# VCFA_v3.net
KiCad netlist of a schematic drawn in EAGLE
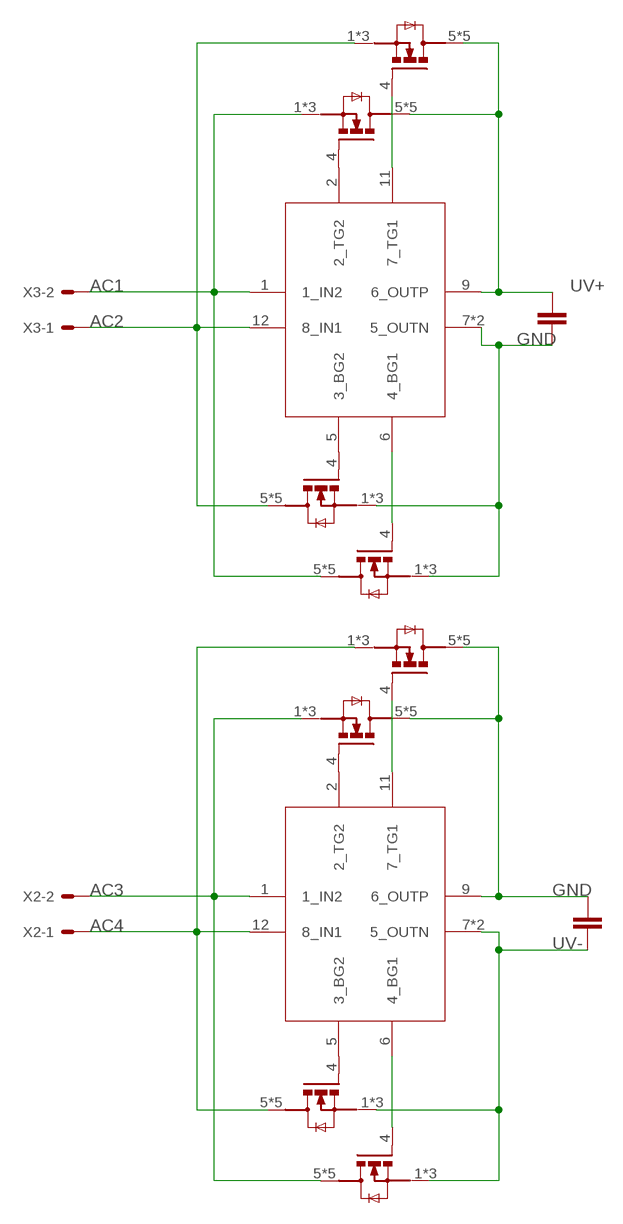
[diagram p0: schematic, sheet 1]
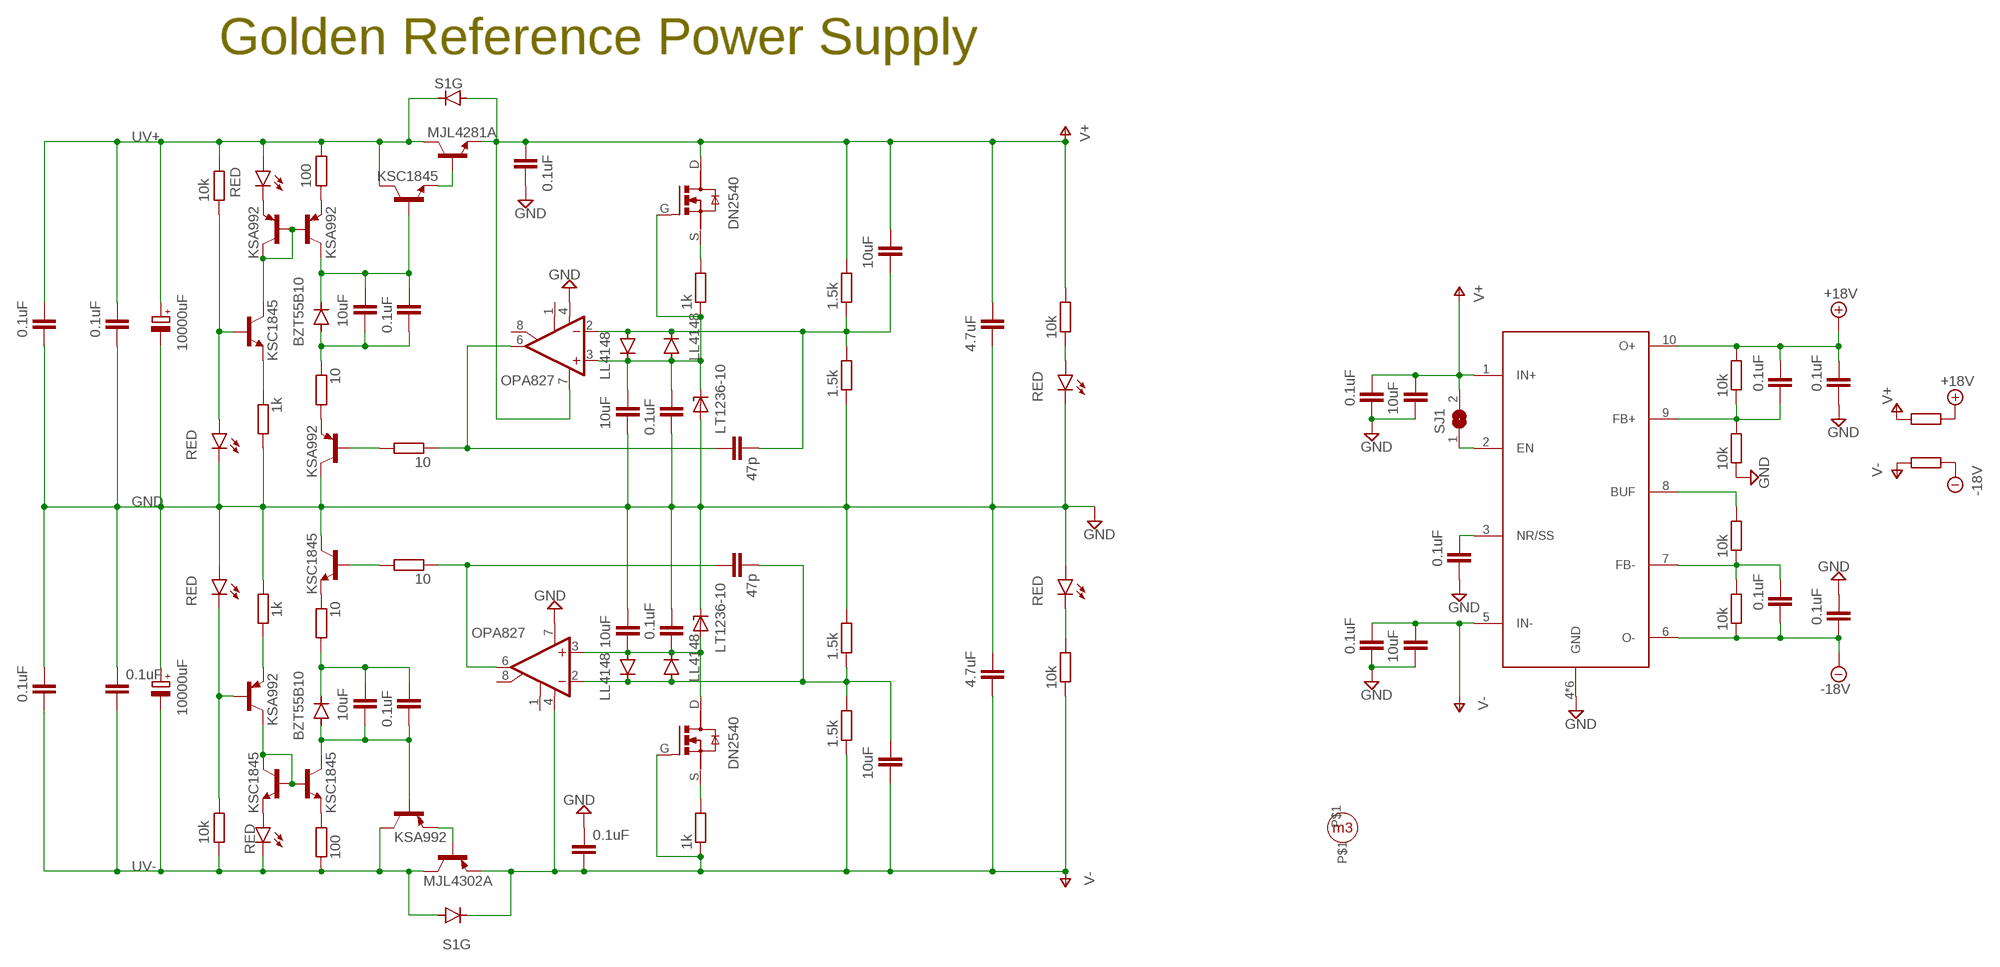
[diagram p1: schematic, sheet 2]
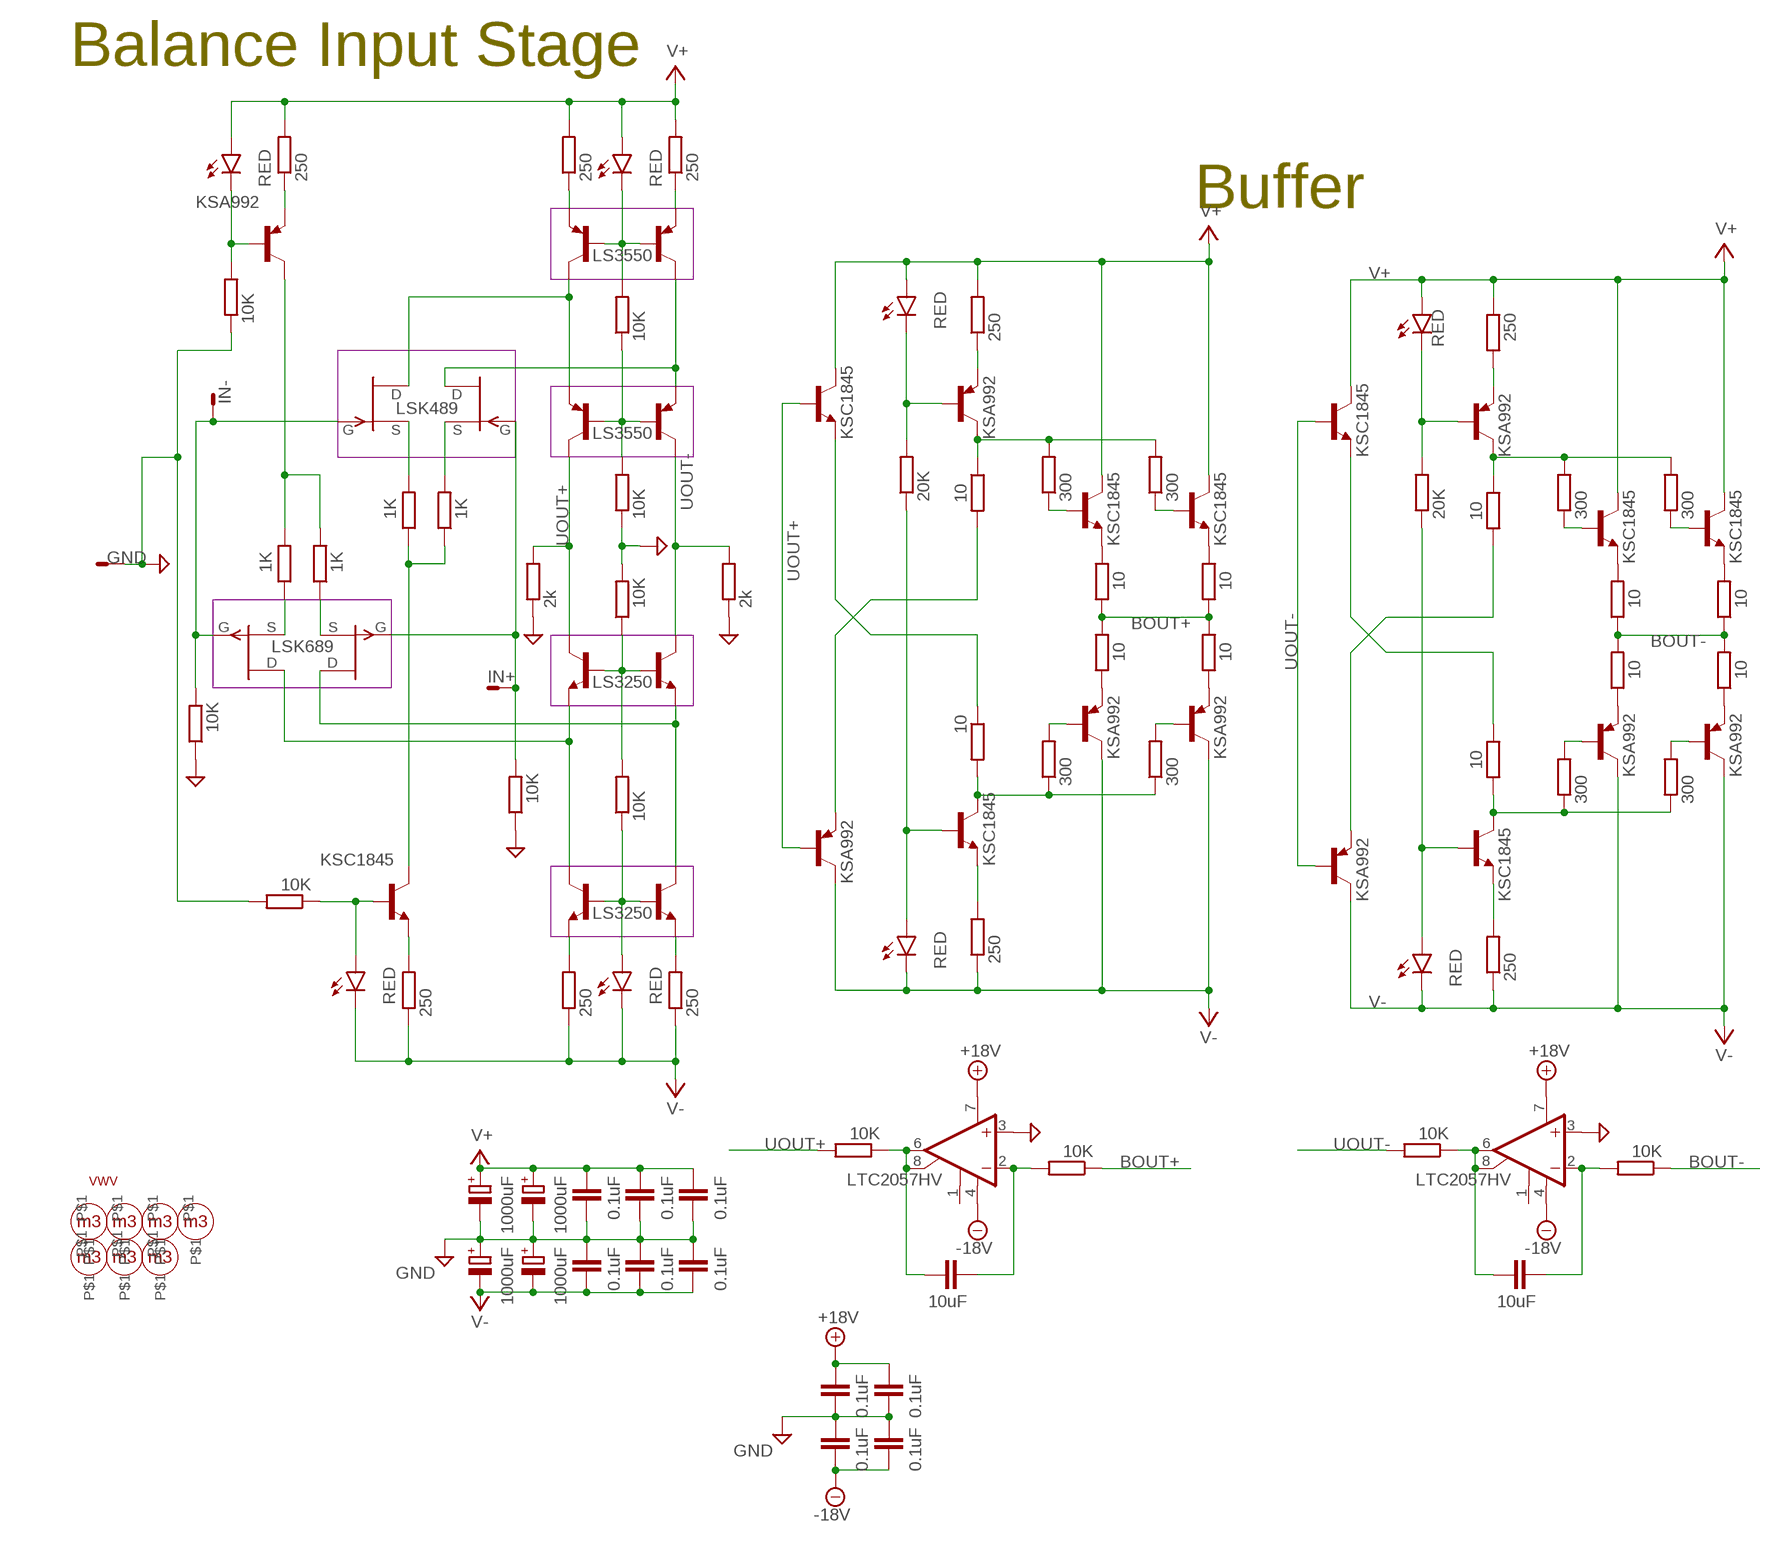
[diagram p2: schematic, sheet 3]
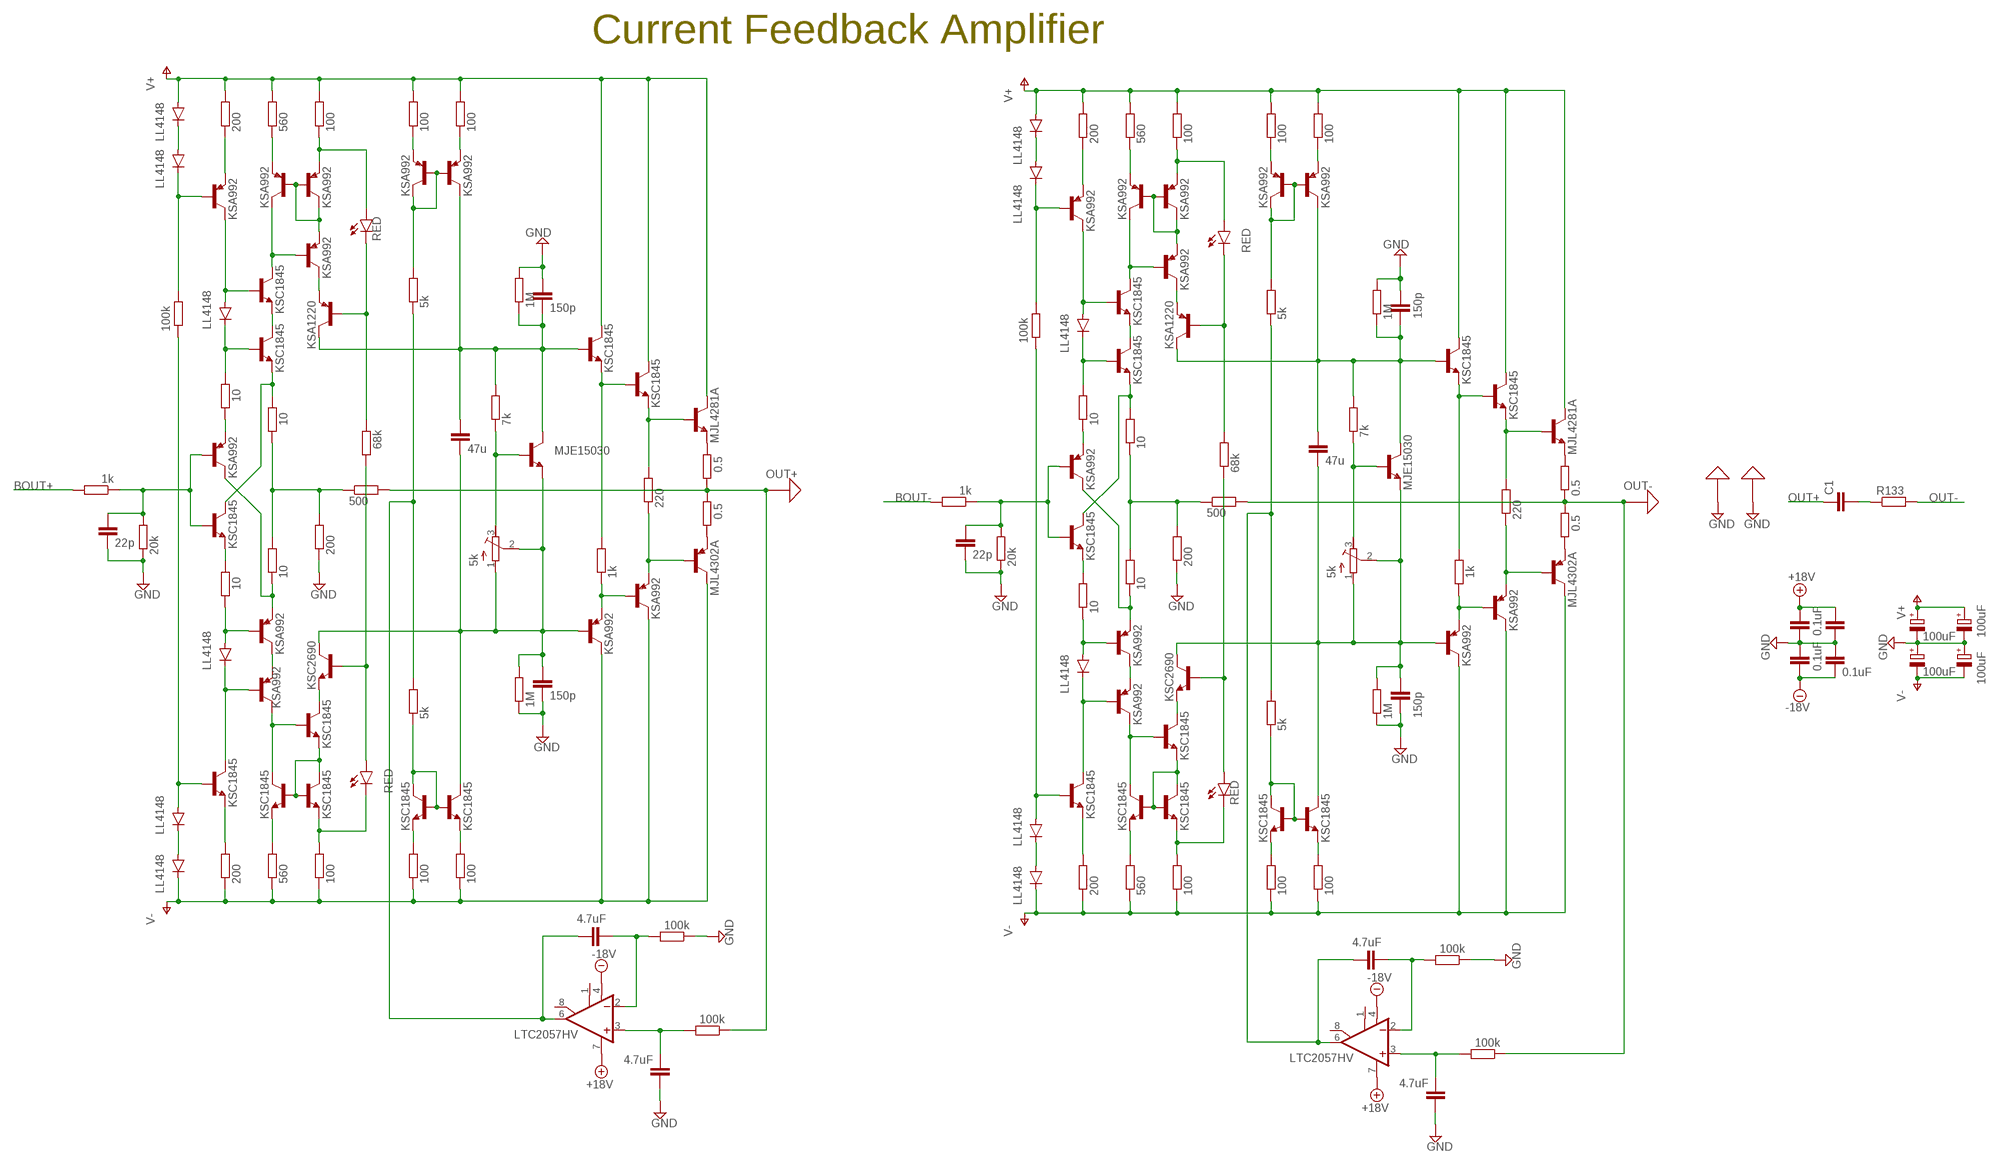
[diagram p3: schematic, sheet 4]

(export (version "E")
  (design (tool "Eeschema 10.0.6"))
  (components
    (comp (ref "C57")
      (value "47uF")
      (footprint "eagle-import:C1206")
      (libsource (lib "eagle-import") (part "C-EUC1206"))
    )
    (comp (ref "C59")
      (value "47uF")
      (footprint "eagle-import:C1206")
      (libsource (lib "eagle-import") (part "C-EUC1206"))
    )
    (comp (ref "Q97")
      (value "MOS_SMDTDSON-8")
      (footprint "eagle-import:PG-TDSON-8")
      (libsource (lib "eagle-import") (part "MOS_SMDTDSON-8"))
    )
    (comp (ref "Q98")
      (value "MOS_SMDTDSON-8")
      (footprint "eagle-import:PG-TDSON-8")
      (libsource (lib "eagle-import") (part "MOS_SMDTDSON-8"))
    )
    (comp (ref "Q99")
      (value "MOS_SMDTDSON-8")
      (footprint "eagle-import:PG-TDSON-8")
      (libsource (lib "eagle-import") (part "MOS_SMDTDSON-8"))
    )
    (comp (ref "Q100")
      (value "MOS_SMDTDSON-8")
      (footprint "eagle-import:PG-TDSON-8")
      (libsource (lib "eagle-import") (part "MOS_SMDTDSON-8"))
    )
    (comp (ref "Q105")
      (value "MOS_SMDTDSON-8")
      (footprint "eagle-import:PG-TDSON-8")
      (libsource (lib "eagle-import") (part "MOS_SMDTDSON-8"))
    )
    (comp (ref "Q106")
      (value "MOS_SMDTDSON-8")
      (footprint "eagle-import:PG-TDSON-8")
      (libsource (lib "eagle-import") (part "MOS_SMDTDSON-8"))
    )
    (comp (ref "Q107")
      (value "MOS_SMDTDSON-8")
      (footprint "eagle-import:PG-TDSON-8")
      (libsource (lib "eagle-import") (part "MOS_SMDTDSON-8"))
    )
    (comp (ref "Q108")
      (value "MOS_SMDTDSON-8")
      (footprint "eagle-import:PG-TDSON-8")
      (libsource (lib "eagle-import") (part "MOS_SMDTDSON-8"))
    )
    (comp (ref "U$2")
      (value "LT4320MSOP")
      (footprint "eagle-import:LT4320_MSOP")
      (libsource (lib "eagle-import") (part "LT4320MSOP"))
    )
    (comp (ref "U$4")
      (value "LT4320MSOP")
      (footprint "eagle-import:LT4320_MSOP")
      (libsource (lib "eagle-import") (part "LT4320MSOP"))
    )
    (comp (ref "X2")
      (value "KK-156-2")
      (footprint "eagle-import:KK-156-2")
      (fields (field (name "MF") "MOLEX"))
      (libsource (lib "eagle-import") (part "KK-156-2"))
    )
    (comp (ref "X3")
      (value "KK-156-2")
      (footprint "eagle-import:KK-156-2")
      (fields (field (name "MF") "MOLEX"))
      (libsource (lib "eagle-import") (part "KK-156-2"))
    )
    (comp (ref "C3")
      (value "0.1uF")
      (footprint "eagle-import:C0805")
      (libsource (lib "eagle-import") (part "C-EUC0805"))
    )
    (comp (ref "C4")
      (value "0.1uF")
      (footprint "eagle-import:C0805")
      (libsource (lib "eagle-import") (part "C-EUC0805"))
    )
    (comp (ref "C5")
      (value "1000uF")
      (footprint "eagle-import:E7,5-18")
      (libsource (lib "eagle-import") (part "CPOL-EUE7.5-18"))
    )
    (comp (ref "C6")
      (value "1000uF")
      (footprint "eagle-import:E7,5-18")
      (libsource (lib "eagle-import") (part "CPOL-EUE7.5-18"))
    )
    (comp (ref "C7")
      (value "1000uF")
      (footprint "eagle-import:E7,5-18")
      (libsource (lib "eagle-import") (part "CPOL-EUE7.5-18"))
    )
    (comp (ref "C8")
      (value "1000uF")
      (footprint "eagle-import:E7,5-18")
      (libsource (lib "eagle-import") (part "CPOL-EUE7.5-18"))
    )
    (comp (ref "C9")
      (value "0.1uF")
      (footprint "eagle-import:C050-045X075")
      (libsource (lib "eagle-import") (part "C-EU050-045X075"))
    )
    (comp (ref "C10")
      (value "0.1uF")
      (footprint "eagle-import:C050-045X075")
      (libsource (lib "eagle-import") (part "C-EU050-045X075"))
    )
    (comp (ref "C11")
      (value "0.1uF")
      (footprint "eagle-import:C050-045X075")
      (libsource (lib "eagle-import") (part "C-EU050-045X075"))
    )
    (comp (ref "C12")
      (value "0.1uF")
      (footprint "eagle-import:C050-045X075")
      (libsource (lib "eagle-import") (part "C-EU050-045X075"))
    )
    (comp (ref "C13")
      (value "10uF")
      (footprint "eagle-import:C1206")
      (libsource (lib "eagle-import") (part "C-EUC1206"))
    )
    (comp (ref "C14")
      (value "0.1uF")
      (footprint "eagle-import:C0805")
      (libsource (lib "eagle-import") (part "C-EUC0805"))
    )
    (comp (ref "C15")
      (value "0.1uF")
      (footprint "eagle-import:C0805")
      (libsource (lib "eagle-import") (part "C-EUC0805"))
    )
    (comp (ref "C16")
      (value "10uF")
      (footprint "eagle-import:C1206")
      (libsource (lib "eagle-import") (part "C-EUC1206"))
    )
    (comp (ref "C74")
      (value "0.1uF")
      (footprint "eagle-import:C050-045X075")
      (libsource (lib "eagle-import") (part "C-EU050-045X075"))
    )
    (comp (ref "C75")
      (value "0.1uF")
      (footprint "eagle-import:C050-045X075")
      (libsource (lib "eagle-import") (part "C-EU050-045X075"))
    )
    (comp (ref "H1")
      (value "HOLE")
      (footprint "eagle-import:M3_HOLE")
      (libsource (lib "eagle-import") (part "HOLE"))
    )
    (comp (ref "H2")
      (value "HOLE")
      (footprint "eagle-import:M3_HOLE")
      (libsource (lib "eagle-import") (part "HOLE"))
    )
    (comp (ref "H3")
      (value "HOLE")
      (footprint "eagle-import:M3_HOLE")
      (libsource (lib "eagle-import") (part "HOLE"))
    )
    (comp (ref "H4")
      (value "HOLE")
      (footprint "eagle-import:M3_HOLE")
      (libsource (lib "eagle-import") (part "HOLE"))
    )
    (comp (ref "H5")
      (value "HOLE")
      (footprint "eagle-import:M3_HOLE")
      (libsource (lib "eagle-import") (part "HOLE"))
    )
    (comp (ref "H6")
      (value "HOLE")
      (footprint "eagle-import:M3_HOLE")
      (libsource (lib "eagle-import") (part "HOLE"))
    )
    (comp (ref "H7")
      (value "HOLE")
      (footprint "eagle-import:M3_HOLE")
      (libsource (lib "eagle-import") (part "HOLE"))
    )
    (comp (ref "IC1")
      (value "LTC2057HV")
      (footprint "eagle-import:SOIC8")
      (libsource (lib "eagle-import") (part "LT10S807C"))
    )
    (comp (ref "IC2")
      (value "LTC2057HV")
      (footprint "eagle-import:SOIC8")
      (libsource (lib "eagle-import") (part "LT10S807C"))
    )
    (comp (ref "LED1")
      (value "RED")
      (footprint "eagle-import:LED_SML1206")
      (libsource (lib "eagle-import") (part "LEDVWV1206"))
    )
    (comp (ref "LED2")
      (value "RED")
      (footprint "eagle-import:LED_SML1206")
      (fields (field (name "SPICEPREFIX") "D"))
      (libsource (lib "eagle-import") (part "LEDVWV1206"))
    )
    (comp (ref "LED3")
      (value "RED")
      (footprint "eagle-import:LED_SML1206")
      (libsource (lib "eagle-import") (part "LEDVWV1206"))
    )
    (comp (ref "LED4")
      (value "RED")
      (footprint "eagle-import:LED_SML1206")
      (libsource (lib "eagle-import") (part "LEDVWV1206"))
    )
    (comp (ref "LED5")
      (value "RED")
      (footprint "eagle-import:LED_SML1206")
      (libsource (lib "eagle-import") (part "LEDVWV1206"))
    )
    (comp (ref "LED6")
      (value "RED")
      (footprint "eagle-import:LED_SML1206")
      (libsource (lib "eagle-import") (part "LEDVWV1206"))
    )
    (comp (ref "LED7")
      (value "RED")
      (footprint "eagle-import:LED_SML1206")
      (libsource (lib "eagle-import") (part "LEDVWV1206"))
    )
    (comp (ref "LED8")
      (value "RED")
      (footprint "eagle-import:LED_SML1206")
      (libsource (lib "eagle-import") (part "LEDVWV1206"))
    )
    (comp (ref "Q1")
      (value "LSK689")
      (footprint "eagle-import:SOT-23-6")
      (libsource (lib "eagle-import") (part "LSK689"))
    )
    (comp (ref "Q2")
      (value "KSA992")
      (footprint "eagle-import:TRANSISTOR_TO92-ECB_P")
      (libsource (lib "eagle-import") (part "BJT_PNPKSA992"))
    )
    (comp (ref "Q3")
      (value "KSC1845")
      (footprint "eagle-import:TRANSISTOR_TO92-ECB_N")
      (libsource (lib "eagle-import") (part "BJT_NPNKSC1845"))
    )
    (comp (ref "Q4")
      (value "LSK489")
      (footprint "eagle-import:SOT-23-6")
      (libsource (lib "eagle-import") (part "LSK489SOP-6"))
    )
    (comp (ref "Q5")
      (value "LS3550")
      (footprint "eagle-import:SOT-23-6")
      (libsource (lib "eagle-import") (part "LS3550"))
    )
    (comp (ref "Q6")
      (value "LS3250")
      (footprint "eagle-import:SOT-23-6")
      (libsource (lib "eagle-import") (part "LS3250"))
    )
    (comp (ref "Q7")
      (value "LS3250")
      (footprint "eagle-import:SOT-23-6")
      (libsource (lib "eagle-import") (part "LS3250"))
    )
    (comp (ref "Q8")
      (value "LS3550")
      (footprint "eagle-import:SOT-23-6")
      (libsource (lib "eagle-import") (part "LS3550"))
    )
    (comp (ref "Q9")
      (value "KSC1845")
      (footprint "eagle-import:TRANSISTOR_TO92-ECB_N")
      (libsource (lib "eagle-import") (part "BJT_NPNKSC1845"))
    )
    (comp (ref "Q10")
      (value "KSA992")
      (footprint "eagle-import:TRANSISTOR_TO92-ECB_P")
      (libsource (lib "eagle-import") (part "BJT_PNPKSA992"))
    )
    (comp (ref "Q11")
      (value "KSA992")
      (footprint "eagle-import:TRANSISTOR_TO92-ECB_P")
      (libsource (lib "eagle-import") (part "BJT_PNPKSA992"))
    )
    (comp (ref "Q12")
      (value "KSC1845")
      (footprint "eagle-import:TRANSISTOR_TO92-ECB_N")
      (libsource (lib "eagle-import") (part "BJT_NPNKSC1845"))
    )
    (comp (ref "Q13")
      (value "KSC1845")
      (footprint "eagle-import:TRANSISTOR_TO92-ECB_N")
      (libsource (lib "eagle-import") (part "BJT_NPNKSC1845"))
    )
    (comp (ref "Q14")
      (value "KSA992")
      (footprint "eagle-import:TRANSISTOR_TO92-ECB_P")
      (libsource (lib "eagle-import") (part "BJT_PNPKSA992"))
    )
    (comp (ref "Q15")
      (value "KSC1845")
      (footprint "eagle-import:TRANSISTOR_TO92-ECB_N")
      (libsource (lib "eagle-import") (part "BJT_NPNKSC1845"))
    )
    (comp (ref "Q16")
      (value "KSA992")
      (footprint "eagle-import:TRANSISTOR_TO92-ECB_P")
      (libsource (lib "eagle-import") (part "BJT_PNPKSA992"))
    )
    (comp (ref "Q17")
      (value "KSC1845")
      (footprint "eagle-import:TRANSISTOR_TO92-ECB_N")
      (libsource (lib "eagle-import") (part "BJT_NPNKSC1845"))
    )
    (comp (ref "Q18")
      (value "KSA992")
      (footprint "eagle-import:TRANSISTOR_TO92-ECB_P")
      (libsource (lib "eagle-import") (part "BJT_PNPKSA992"))
    )
    (comp (ref "Q19")
      (value "KSA992")
      (footprint "eagle-import:TRANSISTOR_TO92-ECB_P")
      (libsource (lib "eagle-import") (part "BJT_PNPKSA992"))
    )
    (comp (ref "Q20")
      (value "KSC1845")
      (footprint "eagle-import:TRANSISTOR_TO92-ECB_N")
      (libsource (lib "eagle-import") (part "BJT_NPNKSC1845"))
    )
    (comp (ref "Q21")
      (value "KSC1845")
      (footprint "eagle-import:TRANSISTOR_TO92-ECB_N")
      (libsource (lib "eagle-import") (part "BJT_NPNKSC1845"))
    )
    (comp (ref "Q22")
      (value "KSA992")
      (footprint "eagle-import:TRANSISTOR_TO92-ECB_P")
      (libsource (lib "eagle-import") (part "BJT_PNPKSA992"))
    )
    (comp (ref "Q23")
      (value "KSC1845")
      (footprint "eagle-import:TRANSISTOR_TO92-ECB_N")
      (libsource (lib "eagle-import") (part "BJT_NPNKSC1845"))
    )
    (comp (ref "Q24")
      (value "KSA992")
      (footprint "eagle-import:TRANSISTOR_TO92-ECB_P")
      (libsource (lib "eagle-import") (part "BJT_PNPKSA992"))
    )
    (comp (ref "R3")
      (value "10K")
      (footprint "eagle-import:MINI_MELF-0204W")
      (libsource (lib "eagle-import") (part "R-EU_MELF0204W"))
    )
    (comp (ref "R4")
      (value "10K")
      (footprint "eagle-import:MINI_MELF-0204W")
      (libsource (lib "eagle-import") (part "R-EU_MELF0204W"))
    )
    (comp (ref "R5")
      (value "250")
      (footprint "eagle-import:MINI_MELF-0204W")
      (libsource (lib "eagle-import") (part "R-EU_MELF0204W"))
    )
    (comp (ref "R6")
      (value "1K")
      (footprint "eagle-import:MINI_MELF-0204W")
      (libsource (lib "eagle-import") (part "R-EU_MELF0204W"))
    )
    (comp (ref "R7")
      (value "250")
      (footprint "eagle-import:MINI_MELF-0204W")
      (fields (field (name "SPICEPREFIX") "R"))
      (libsource (lib "eagle-import") (part "R-EU_MELF0204W"))
    )
    (comp (ref "R8")
      (value "1K")
      (footprint "eagle-import:MINI_MELF-0204W")
      (libsource (lib "eagle-import") (part "R-EU_MELF0204W"))
    )
    (comp (ref "R9")
      (value "1K")
      (footprint "eagle-import:MINI_MELF-0204W")
      (libsource (lib "eagle-import") (part "R-EU_MELF0204W"))
    )
    (comp (ref "R10")
      (value "1K")
      (footprint "eagle-import:MINI_MELF-0204W")
      (libsource (lib "eagle-import") (part "R-EU_MELF0204W"))
    )
    (comp (ref "R11")
      (value "2k")
      (footprint "eagle-import:MINI_MELF-0204W")
      (libsource (lib "eagle-import") (part "R-EU_MELF0204W"))
    )
    (comp (ref "R12")
      (value "250")
      (footprint "eagle-import:MINI_MELF-0204W")
      (libsource (lib "eagle-import") (part "R-EU_MELF0204W"))
    )
    (comp (ref "R13")
      (value "250")
      (footprint "eagle-import:MINI_MELF-0204W")
      (libsource (lib "eagle-import") (part "R-EU_MELF0204W"))
    )
    (comp (ref "R14")
      (value "10K")
      (footprint "eagle-import:MINI_MELF-0204W")
      (libsource (lib "eagle-import") (part "R-EU_MELF0204W"))
    )
    (comp (ref "R15")
      (value "10K")
      (footprint "eagle-import:MINI_MELF-0204W")
      (libsource (lib "eagle-import") (part "R-EU_MELF0204W"))
    )
    (comp (ref "R16")
      (value "10K")
      (footprint "eagle-import:MINI_MELF-0204W")
      (libsource (lib "eagle-import") (part "R-EU_MELF0204W"))
    )
    (comp (ref "R17")
      (value "10K")
      (footprint "eagle-import:MINI_MELF-0204W")
      (libsource (lib "eagle-import") (part "R-EU_MELF0204W"))
    )
    (comp (ref "R18")
      (value "250")
      (footprint "eagle-import:MINI_MELF-0204W")
      (libsource (lib "eagle-import") (part "R-EU_MELF0204W"))
    )
    (comp (ref "R19")
      (value "250")
      (footprint "eagle-import:MINI_MELF-0204W")
      (libsource (lib "eagle-import") (part "R-EU_MELF0204W"))
    )
    (comp (ref "R20")
      (value "2k")
      (footprint "eagle-import:MINI_MELF-0204W")
      (libsource (lib "eagle-import") (part "R-EU_MELF0204W"))
    )
    (comp (ref "R21")
      (value "10K")
      (footprint "eagle-import:MINI_MELF-0204W")
      (libsource (lib "eagle-import") (part "R-EU_MELF0204W"))
    )
    (comp (ref "R22")
      (value "20K")
      (footprint "eagle-import:MINI_MELF-0204W")
      (libsource (lib "eagle-import") (part "R-EU_MELF0204W"))
    )
    (comp (ref "R23")
      (value "250")
      (footprint "eagle-import:MINI_MELF-0204W")
      (libsource (lib "eagle-import") (part "R-EU_MELF0204W"))
    )
    (comp (ref "R24")
      (value "10")
      (footprint "eagle-import:MINI_MELF-0204W")
      (libsource (lib "eagle-import") (part "R-EU_MELF0204W"))
    )
    (comp (ref "R25")
      (value "10")
      (footprint "eagle-import:MINI_MELF-0204W")
      (libsource (lib "eagle-import") (part "R-EU_MELF0204W"))
    )
    (comp (ref "R26")
      (value "250")
      (footprint "eagle-import:MINI_MELF-0204W")
      (libsource (lib "eagle-import") (part "R-EU_MELF0204W"))
    )
    (comp (ref "R27")
      (value "300")
      (footprint "eagle-import:MINI_MELF-0204W")
      (libsource (lib "eagle-import") (part "R-EU_MELF0204W"))
    )
    (comp (ref "R28")
      (value "300")
      (footprint "eagle-import:MINI_MELF-0204W")
      (libsource (lib "eagle-import") (part "R-EU_MELF0204W"))
    )
    (comp (ref "R29")
      (value "10K")
      (footprint "eagle-import:MINI_MELF-0204W")
      (libsource (lib "eagle-import") (part "R-EU_MELF0204W"))
    )
    (comp (ref "R30")
      (value "10")
      (footprint "eagle-import:MINI_MELF-0204W")
      (libsource (lib "eagle-import") (part "R-EU_MELF0204W"))
    )
    (comp (ref "R31")
      (value "10")
      (footprint "eagle-import:MINI_MELF-0204W")
      (libsource (lib "eagle-import") (part "R-EU_MELF0204W"))
    )
    (comp (ref "R32")
      (value "300")
      (footprint "eagle-import:MINI_MELF-0204W")
      (libsource (lib "eagle-import") (part "R-EU_MELF0204W"))
    )
    (comp (ref "R33")
      (value "300")
      (footprint "eagle-import:MINI_MELF-0204W")
      (libsource (lib "eagle-import") (part "R-EU_MELF0204W"))
    )
    (comp (ref "R34")
      (value "10")
      (footprint "eagle-import:MINI_MELF-0204W")
      (libsource (lib "eagle-import") (part "R-EU_MELF0204W"))
    )
    (comp (ref "R35")
      (value "10")
      (footprint "eagle-import:MINI_MELF-0204W")
      (libsource (lib "eagle-import") (part "R-EU_MELF0204W"))
    )
    (comp (ref "R36")
      (value "10K")
      (footprint "eagle-import:MINI_MELF-0204W")
      (libsource (lib "eagle-import") (part "R-EU_MELF0204W"))
    )
    (comp (ref "R37")
      (value "20K")
      (footprint "eagle-import:MINI_MELF-0204W")
      (libsource (lib "eagle-import") (part "R-EU_MELF0204W"))
    )
    (comp (ref "R38")
      (value "250")
      (footprint "eagle-import:MINI_MELF-0204W")
      (libsource (lib "eagle-import") (part "R-EU_MELF0204W"))
    )
    (comp (ref "R39")
      (value "10")
      (footprint "eagle-import:MINI_MELF-0204W")
      (libsource (lib "eagle-import") (part "R-EU_MELF0204W"))
    )
    (comp (ref "R40")
      (value "10")
      (footprint "eagle-import:MINI_MELF-0204W")
      (libsource (lib "eagle-import") (part "R-EU_MELF0204W"))
    )
    (comp (ref "R41")
      (value "250")
      (footprint "eagle-import:MINI_MELF-0204W")
      (libsource (lib "eagle-import") (part "R-EU_MELF0204W"))
    )
    (comp (ref "R42")
      (value "300")
      (footprint "eagle-import:MINI_MELF-0204W")
      (libsource (lib "eagle-import") (part "R-EU_MELF0204W"))
    )
    (comp (ref "R43")
      (value "300")
      (footprint "eagle-import:MINI_MELF-0204W")
      (libsource (lib "eagle-import") (part "R-EU_MELF0204W"))
    )
    (comp (ref "R44")
      (value "10K")
      (footprint "eagle-import:MINI_MELF-0204W")
      (libsource (lib "eagle-import") (part "R-EU_MELF0204W"))
    )
    (comp (ref "R45")
      (value "10")
      (footprint "eagle-import:MINI_MELF-0204W")
      (libsource (lib "eagle-import") (part "R-EU_MELF0204W"))
    )
    (comp (ref "R46")
      (value "10")
      (footprint "eagle-import:MINI_MELF-0204W")
      (libsource (lib "eagle-import") (part "R-EU_MELF0204W"))
    )
    (comp (ref "R47")
      (value "300")
      (footprint "eagle-import:MINI_MELF-0204W")
      (libsource (lib "eagle-import") (part "R-EU_MELF0204W"))
    )
    (comp (ref "R48")
      (value "300")
      (footprint "eagle-import:MINI_MELF-0204W")
      (libsource (lib "eagle-import") (part "R-EU_MELF0204W"))
    )
    (comp (ref "R49")
      (value "10")
      (footprint "eagle-import:MINI_MELF-0204W")
      (libsource (lib "eagle-import") (part "R-EU_MELF0204W"))
    )
    (comp (ref "R50")
      (value "10")
      (footprint "eagle-import:MINI_MELF-0204W")
      (libsource (lib "eagle-import") (part "R-EU_MELF0204W"))
    )
    (comp (ref "R134")
      (value "10K")
      (footprint "eagle-import:MINI_MELF-0204W")
      (libsource (lib "eagle-import") (part "R-EU_MELF0204W"))
    )
    (comp (ref "R135")
      (value "10K")
      (footprint "eagle-import:MINI_MELF-0204W")
      (libsource (lib "eagle-import") (part "R-EU_MELF0204W"))
    )
    (comp (ref "S1")
      (value "VWV")
      (footprint "eagle-import:VWV")
      (libsource (lib "eagle-import") (part "VWV"))
    )
    (comp (ref "X1")
      (value "KK-156-3")
      (footprint "eagle-import:KK-156-3")
      (fields (field (name "MF") "MOLEX"))
      (libsource (lib "eagle-import") (part "KK-156-3"))
    )
    (comp (ref "C1")
      (value "C-EUECWU-V")
      (footprint "eagle-import:ECHU-Y")
      (libsource (lib "eagle-import") (part "C-EUECWU-V"))
    )
    (comp (ref "C17")
      (value "22p")
      (footprint "eagle-import:C0805")
      (fields (field (name "SPICEPREFIX") "C"))
      (libsource (lib "eagle-import") (part "C-EUC0805"))
    )
    (comp (ref "C18")
      (value "47u")
      (footprint "eagle-import:C1210")
      (fields (field (name "SPICEPREFIX") "C"))
      (libsource (lib "eagle-import") (part "C-EUC1210"))
    )
    (comp (ref "C19")
      (value "150p")
      (footprint "eagle-import:C0805")
      (fields (field (name "SPICEPREFIX") "C"))
      (libsource (lib "eagle-import") (part "C-EUC0805"))
    )
    (comp (ref "C20")
      (value "150p")
      (footprint "eagle-import:C0805")
      (fields (field (name "SPICEPREFIX") "C"))
      (libsource (lib "eagle-import") (part "C-EUC0805"))
    )
    (comp (ref "C21")
      (value "4.7uF")
      (footprint "eagle-import:C1210")
      (fields (field (name "SPICEPREFIX") "C"))
      (libsource (lib "eagle-import") (part "C-EUC1210"))
    )
    (comp (ref "C22")
      (value "4.7uF")
      (footprint "eagle-import:C1210")
      (fields (field (name "SPICEPREFIX") "C"))
      (libsource (lib "eagle-import") (part "C-EUC1210"))
    )
    (comp (ref "C23")
      (value "0.1uF")
      (footprint "eagle-import:C0603K")
      (libsource (lib "eagle-import") (part "C-EUC0603K"))
    )
    (comp (ref "C24")
      (value "0.1uF")
      (footprint "eagle-import:C0603K")
      (libsource (lib "eagle-import") (part "C-EUC0603K"))
    )
    (comp (ref "C25")
      (value "100uF")
      (footprint "eagle-import:E5-8,5")
      (libsource (lib "eagle-import") (part "CPOL-EUE5-8.5"))
    )
    (comp (ref "C26")
      (value "100uF")
      (footprint "eagle-import:E5-8,5")
      (libsource (lib "eagle-import") (part "CPOL-EUE5-8.5"))
    )
    (comp (ref "C27")
      (value "22p")
      (footprint "eagle-import:C0805")
      (fields (field (name "SPICEPREFIX") "C"))
      (libsource (lib "eagle-import") (part "C-EUC0805"))
    )
    (comp (ref "C28")
      (value "47u")
      (footprint "eagle-import:C1210")
      (fields (field (name "SPICEPREFIX") "C"))
      (libsource (lib "eagle-import") (part "C-EUC1210"))
    )
    (comp (ref "C29")
      (value "150p")
      (footprint "eagle-import:C0805")
      (fields (field (name "SPICEPREFIX") "C"))
      (libsource (lib "eagle-import") (part "C-EUC0805"))
    )
    (comp (ref "C30")
      (value "150p")
      (footprint "eagle-import:C0805")
      (fields (field (name "SPICEPREFIX") "C"))
      (libsource (lib "eagle-import") (part "C-EUC0805"))
    )
    (comp (ref "C31")
      (value "4.7uF")
      (footprint "eagle-import:C1210")
      (fields (field (name "SPICEPREFIX") "C"))
      (libsource (lib "eagle-import") (part "C-EUC1210"))
    )
    (comp (ref "C32")
      (value "4.7uF")
      (footprint "eagle-import:C1210")
      (fields (field (name "SPICEPREFIX") "C"))
      (libsource (lib "eagle-import") (part "C-EUC1210"))
    )
    (comp (ref "C33")
      (value "0.1uF")
      (footprint "eagle-import:C0603K")
      (libsource (lib "eagle-import") (part "C-EUC0603K"))
    )
    (comp (ref "C34")
      (value "0.1uF")
      (footprint "eagle-import:C0603K")
      (libsource (lib "eagle-import") (part "C-EUC0603K"))
    )
    (comp (ref "C35")
      (value "100uF")
      (footprint "eagle-import:E5-8,5")
      (libsource (lib "eagle-import") (part "CPOL-EUE5-8.5"))
    )
    (comp (ref "C36")
      (value "100uF")
      (footprint "eagle-import:E5-8,5")
      (libsource (lib "eagle-import") (part "CPOL-EUE5-8.5"))
    )
    (comp (ref "D1")
      (value "LL4148")
      (footprint "eagle-import:SOD80C")
      (fields (field (name "SPICEPREFIX") "D"))
      (libsource (lib "eagle-import") (part "DIODE-SOD80C"))
    )
    (comp (ref "D2")
      (value "LL4148")
      (footprint "eagle-import:SOD80C")
      (fields (field (name "SPICEPREFIX") "D"))
      (libsource (lib "eagle-import") (part "DIODE-SOD80C"))
    )
    (comp (ref "D3")
      (value "LL4148")
      (footprint "eagle-import:SOD80C")
      (fields (field (name "SPICEPREFIX") "D"))
      (libsource (lib "eagle-import") (part "DIODE-SOD80C"))
    )
    (comp (ref "D4")
      (value "LL4148")
      (footprint "eagle-import:SOD80C")
      (fields (field (name "SPICEPREFIX") "D"))
      (libsource (lib "eagle-import") (part "DIODE-SOD80C"))
    )
    (comp (ref "D5")
      (value "LL4148")
      (footprint "eagle-import:SOD80C")
      (fields (field (name "SPICEPREFIX") "D"))
      (libsource (lib "eagle-import") (part "DIODE-SOD80C"))
    )
    (comp (ref "D6")
      (value "LL4148")
      (footprint "eagle-import:SOD80C")
      (fields (field (name "SPICEPREFIX") "D"))
      (libsource (lib "eagle-import") (part "DIODE-SOD80C"))
    )
    (comp (ref "D7")
      (value "LL4148")
      (footprint "eagle-import:SOD80C")
      (fields (field (name "SPICEPREFIX") "D"))
      (libsource (lib "eagle-import") (part "DIODE-SOD80C"))
    )
    (comp (ref "D8")
      (value "LL4148")
      (footprint "eagle-import:SOD80C")
      (fields (field (name "SPICEPREFIX") "D"))
      (libsource (lib "eagle-import") (part "DIODE-SOD80C"))
    )
    (comp (ref "D9")
      (value "LL4148")
      (footprint "eagle-import:SOD80C")
      (fields (field (name "SPICEPREFIX") "D"))
      (libsource (lib "eagle-import") (part "DIODE-SOD80C"))
    )
    (comp (ref "D10")
      (value "LL4148")
      (footprint "eagle-import:SOD80C")
      (fields (field (name "SPICEPREFIX") "D"))
      (libsource (lib "eagle-import") (part "DIODE-SOD80C"))
    )
    (comp (ref "D11")
      (value "LL4148")
      (footprint "eagle-import:SOD80C")
      (fields (field (name "SPICEPREFIX") "D"))
      (libsource (lib "eagle-import") (part "DIODE-SOD80C"))
    )
    (comp (ref "D12")
      (value "LL4148")
      (footprint "eagle-import:SOD80C")
      (fields (field (name "SPICEPREFIX") "D"))
      (libsource (lib "eagle-import") (part "DIODE-SOD80C"))
    )
    (comp (ref "IC3")
      (value "LTC2057HV")
      (footprint "eagle-import:SOIC8")
      (libsource (lib "eagle-import") (part "LT10S837I"))
    )
    (comp (ref "IC4")
      (value "LTC2057HV")
      (footprint "eagle-import:SOIC8")
      (libsource (lib "eagle-import") (part "LT10S837I"))
    )
    (comp (ref "LED9")
      (value "RED")
      (footprint "eagle-import:LED_SML1206")
      (fields (field (name "SPICEPREFIX") "D"))
      (libsource (lib "eagle-import") (part "LEDVWV1206"))
    )
    (comp (ref "LED10")
      (value "RED")
      (footprint "eagle-import:LED_SML1206")
      (fields (field (name "SPICEPREFIX") "D"))
      (libsource (lib "eagle-import") (part "LEDVWV1206"))
    )
    (comp (ref "LED11")
      (value "RED")
      (footprint "eagle-import:LED_SML1206")
      (fields (field (name "SPICEPREFIX") "D"))
      (libsource (lib "eagle-import") (part "LEDVWV1206"))
    )
    (comp (ref "LED12")
      (value "RED")
      (footprint "eagle-import:LED_SML1206")
      (fields (field (name "SPICEPREFIX") "D"))
      (libsource (lib "eagle-import") (part "LEDVWV1206"))
    )
    (comp (ref "PAD1")
      (value "PAD")
      (footprint "eagle-import:PAD-16")
      (libsource (lib "eagle-import") (part "PAD"))
    )
    (comp (ref "PAD2")
      (value "PAD")
      (footprint "eagle-import:PAD-16")
      (libsource (lib "eagle-import") (part "PAD"))
    )
    (comp (ref "PAD3")
      (value "PAD")
      (footprint "eagle-import:PAD-16")
      (libsource (lib "eagle-import") (part "PAD"))
    )
    (comp (ref "PAD4")
      (value "PAD")
      (footprint "eagle-import:PAD-16")
      (libsource (lib "eagle-import") (part "PAD"))
    )
    (comp (ref "Q25")
      (value "KSA992")
      (footprint "eagle-import:TRANSISTOR_TO92-ECB_P")
      (fields (field (name "SPICEPREFIX") "Q"))
      (libsource (lib "eagle-import") (part "BJT_PNPKSA992"))
    )
    (comp (ref "Q26")
      (value "KSA992")
      (footprint "eagle-import:TRANSISTOR_TO92-ECB_P")
      (fields (field (name "SPICEPREFIX") "Q"))
      (libsource (lib "eagle-import") (part "BJT_PNPKSA992"))
    )
    (comp (ref "Q27")
      (value "KSC1845")
      (footprint "eagle-import:TRANSISTOR_TO92-ECB_N")
      (fields (field (name "SPICEPREFIX") "Q"))
      (libsource (lib "eagle-import") (part "BJT_NPNKSC1845"))
    )
    (comp (ref "Q28")
      (value "KSC1845")
      (footprint "eagle-import:TRANSISTOR_TO92-ECB_N")
      (fields (field (name "SPICEPREFIX") "Q"))
      (libsource (lib "eagle-import") (part "BJT_NPNKSC1845"))
    )
    (comp (ref "Q29")
      (value "KSC1845")
      (footprint "eagle-import:TRANSISTOR_TO92-ECB_N")
      (fields (field (name "SPICEPREFIX") "Q"))
      (libsource (lib "eagle-import") (part "BJT_NPNKSC1845"))
    )
    (comp (ref "Q30")
      (value "KSC1845")
      (footprint "eagle-import:TRANSISTOR_TO92-ECB_N")
      (fields (field (name "SPICEPREFIX") "Q"))
      (libsource (lib "eagle-import") (part "BJT_NPNKSC1845"))
    )
    (comp (ref "Q31")
      (value "KSA992")
      (footprint "eagle-import:TRANSISTOR_TO92-ECB_P")
      (fields (field (name "SPICEPREFIX") "Q"))
      (libsource (lib "eagle-import") (part "BJT_PNPKSA992"))
    )
    (comp (ref "Q32")
      (value "KSA992")
      (footprint "eagle-import:TRANSISTOR_TO92-ECB_P")
      (fields (field (name "SPICEPREFIX") "Q"))
      (libsource (lib "eagle-import") (part "BJT_PNPKSA992"))
    )
    (comp (ref "Q33")
      (value "KSA992")
      (footprint "eagle-import:TRANSISTOR_TO92-ECB_P")
      (fields (field (name "SPICEPREFIX") "Q"))
      (libsource (lib "eagle-import") (part "BJT_PNPKSA992"))
    )
    (comp (ref "Q34")
      (value "KSC1845")
      (footprint "eagle-import:TRANSISTOR_TO92-ECB_N")
      (fields (field (name "SPICEPREFIX") "Q"))
      (libsource (lib "eagle-import") (part "BJT_NPNKSC1845"))
    )
    (comp (ref "Q35")
      (value "KSA992")
      (footprint "eagle-import:TRANSISTOR_TO92-ECB_P")
      (fields (field (name "SPICEPREFIX") "Q"))
      (libsource (lib "eagle-import") (part "BJT_PNPKSA992"))
    )
    (comp (ref "Q36")
      (value "KSA992")
      (footprint "eagle-import:TRANSISTOR_TO92-ECB_P")
      (fields (field (name "SPICEPREFIX") "Q"))
      (libsource (lib "eagle-import") (part "BJT_PNPKSA992"))
    )
    (comp (ref "Q37")
      (value "KSC1845")
      (footprint "eagle-import:TRANSISTOR_TO92-ECB_N")
      (fields (field (name "SPICEPREFIX") "Q"))
      (libsource (lib "eagle-import") (part "BJT_NPNKSC1845"))
    )
    (comp (ref "Q38")
      (value "KSC1845")
      (footprint "eagle-import:TRANSISTOR_TO92-ECB_N")
      (fields (field (name "SPICEPREFIX") "Q"))
      (libsource (lib "eagle-import") (part "BJT_NPNKSC1845"))
    )
    (comp (ref "Q39")
      (value "KSA1220")
      (footprint "eagle-import:TRANSISTOR_TO126_P")
      (fields (field (name "SPICEPREFIX") "Q"))
      (libsource (lib "eagle-import") (part "BJT_PNPKSA1220"))
    )
    (comp (ref "Q40")
      (value "KSC2690")
      (footprint "eagle-import:TRANSISTOR_TO126_N")
      (fields (field (name "SPICEPREFIX") "Q"))
      (libsource (lib "eagle-import") (part "BJT_NPNKSC2690"))
    )
    (comp (ref "Q41")
      (value "KSA992")
      (footprint "eagle-import:TRANSISTOR_TO92-ECB_P")
      (fields (field (name "SPICEPREFIX") "Q"))
      (libsource (lib "eagle-import") (part "BJT_PNPKSA992"))
    )
    (comp (ref "Q42")
      (value "KSC1845")
      (footprint "eagle-import:TRANSISTOR_TO92-ECB_N")
      (fields (field (name "SPICEPREFIX") "Q"))
      (libsource (lib "eagle-import") (part "BJT_NPNKSC1845"))
    )
    (comp (ref "Q43")
      (value "KSA992")
      (footprint "eagle-import:TRANSISTOR_TO92-ECB_P")
      (fields (field (name "SPICEPREFIX") "Q"))
      (libsource (lib "eagle-import") (part "BJT_PNPKSA992"))
    )
    (comp (ref "Q44")
      (value "KSC1845")
      (footprint "eagle-import:TRANSISTOR_TO92-ECB_N")
      (fields (field (name "SPICEPREFIX") "Q"))
      (libsource (lib "eagle-import") (part "BJT_NPNKSC1845"))
    )
    (comp (ref "Q45")
      (value "MJE15030")
      (footprint "eagle-import:TRANSISTOR_TO220_BCE_N")
      (fields (field (name "SPICEPREFIX") "Q"))
      (libsource (lib "eagle-import") (part "BJT_NPNMJE15030"))
    )
    (comp (ref "Q46")
      (value "KSC1845")
      (footprint "eagle-import:TRANSISTOR_TO92-ECB_N")
      (fields (field (name "SPICEPREFIX") "Q"))
      (libsource (lib "eagle-import") (part "BJT_NPNKSC1845"))
    )
    (comp (ref "Q47")
      (value "KSA992")
      (footprint "eagle-import:TRANSISTOR_TO92-ECB_P")
      (fields (field (name "SPICEPREFIX") "Q"))
      (libsource (lib "eagle-import") (part "BJT_PNPKSA992"))
    )
    (comp (ref "Q48")
      (value "KSC1845")
      (footprint "eagle-import:TRANSISTOR_TO92-ECB_N")
      (fields (field (name "SPICEPREFIX") "Q"))
      (libsource (lib "eagle-import") (part "BJT_NPNKSC1845"))
    )
    (comp (ref "Q49")
      (value "KSA992")
      (footprint "eagle-import:TRANSISTOR_TO92-ECB_P")
      (fields (field (name "SPICEPREFIX") "Q"))
      (libsource (lib "eagle-import") (part "BJT_PNPKSA992"))
    )
    (comp (ref "Q50")
      (value "MJL4281A")
      (footprint "eagle-import:TRANSISTOR_TO247_BCE_N")
      (fields (field (name "SPICEPREFIX") "Q"))
      (libsource (lib "eagle-import") (part "BJT_NPNMJL4281"))
    )
    (comp (ref "Q51")
      (value "MJL4302A")
      (footprint "eagle-import:TRANSISTOR_TO247_BCE_P")
      (fields (field (name "SPICEPREFIX") "Q"))
      (libsource (lib "eagle-import") (part "BJT_PNPMJL4302"))
    )
    (comp (ref "Q52")
      (value "KSA992")
      (footprint "eagle-import:TRANSISTOR_TO92-ECB_P")
      (fields (field (name "SPICEPREFIX") "Q"))
      (libsource (lib "eagle-import") (part "BJT_PNPKSA992"))
    )
    (comp (ref "Q53")
      (value "KSA992")
      (footprint "eagle-import:TRANSISTOR_TO92-ECB_P")
      (fields (field (name "SPICEPREFIX") "Q"))
      (libsource (lib "eagle-import") (part "BJT_PNPKSA992"))
    )
    (comp (ref "Q54")
      (value "KSC1845")
      (footprint "eagle-import:TRANSISTOR_TO92-ECB_N")
      (fields (field (name "SPICEPREFIX") "Q"))
      (libsource (lib "eagle-import") (part "BJT_NPNKSC1845"))
    )
    (comp (ref "Q55")
      (value "KSC1845")
      (footprint "eagle-import:TRANSISTOR_TO92-ECB_N")
      (fields (field (name "SPICEPREFIX") "Q"))
      (libsource (lib "eagle-import") (part "BJT_NPNKSC1845"))
    )
    (comp (ref "Q56")
      (value "KSC1845")
      (footprint "eagle-import:TRANSISTOR_TO92-ECB_N")
      (fields (field (name "SPICEPREFIX") "Q"))
      (libsource (lib "eagle-import") (part "BJT_NPNKSC1845"))
    )
    (comp (ref "Q57")
      (value "KSC1845")
      (footprint "eagle-import:TRANSISTOR_TO92-ECB_N")
      (fields (field (name "SPICEPREFIX") "Q"))
      (libsource (lib "eagle-import") (part "BJT_NPNKSC1845"))
    )
    (comp (ref "Q58")
      (value "KSA992")
      (footprint "eagle-import:TRANSISTOR_TO92-ECB_P")
      (fields (field (name "SPICEPREFIX") "Q"))
      (libsource (lib "eagle-import") (part "BJT_PNPKSA992"))
    )
    (comp (ref "Q59")
      (value "KSA992")
      (footprint "eagle-import:TRANSISTOR_TO92-ECB_P")
      (fields (field (name "SPICEPREFIX") "Q"))
      (libsource (lib "eagle-import") (part "BJT_PNPKSA992"))
    )
    (comp (ref "Q60")
      (value "KSA992")
      (footprint "eagle-import:TRANSISTOR_TO92-ECB_P")
      (fields (field (name "SPICEPREFIX") "Q"))
      (libsource (lib "eagle-import") (part "BJT_PNPKSA992"))
    )
    (comp (ref "Q61")
      (value "KSC1845")
      (footprint "eagle-import:TRANSISTOR_TO92-ECB_N")
      (fields (field (name "SPICEPREFIX") "Q"))
      (libsource (lib "eagle-import") (part "BJT_NPNKSC1845"))
    )
    (comp (ref "Q62")
      (value "KSA992")
      (footprint "eagle-import:TRANSISTOR_TO92-ECB_P")
      (fields (field (name "SPICEPREFIX") "Q"))
      (libsource (lib "eagle-import") (part "BJT_PNPKSA992"))
    )
    (comp (ref "Q63")
      (value "KSA992")
      (footprint "eagle-import:TRANSISTOR_TO92-ECB_P")
      (fields (field (name "SPICEPREFIX") "Q"))
      (libsource (lib "eagle-import") (part "BJT_PNPKSA992"))
    )
    (comp (ref "Q64")
      (value "KSC1845")
      (footprint "eagle-import:TRANSISTOR_TO92-ECB_N")
      (fields (field (name "SPICEPREFIX") "Q"))
      (libsource (lib "eagle-import") (part "BJT_NPNKSC1845"))
    )
    (comp (ref "Q65")
      (value "KSC1845")
      (footprint "eagle-import:TRANSISTOR_TO92-ECB_N")
      (fields (field (name "SPICEPREFIX") "Q"))
      (libsource (lib "eagle-import") (part "BJT_NPNKSC1845"))
    )
    (comp (ref "Q66")
      (value "KSA1220")
      (footprint "eagle-import:TRANSISTOR_TO126_P")
      (fields (field (name "SPICEPREFIX") "Q"))
      (libsource (lib "eagle-import") (part "BJT_PNPKSA1220"))
    )
    (comp (ref "Q67")
      (value "KSC2690")
      (footprint "eagle-import:TRANSISTOR_TO126_N")
      (fields (field (name "SPICEPREFIX") "Q"))
      (libsource (lib "eagle-import") (part "BJT_NPNKSC2690"))
    )
    (comp (ref "Q68")
      (value "KSA992")
      (footprint "eagle-import:TRANSISTOR_TO92-ECB_P")
      (fields (field (name "SPICEPREFIX") "Q"))
      (libsource (lib "eagle-import") (part "BJT_PNPKSA992"))
    )
    (comp (ref "Q69")
      (value "KSC1845")
      (footprint "eagle-import:TRANSISTOR_TO92-ECB_N")
      (fields (field (name "SPICEPREFIX") "Q"))
      (libsource (lib "eagle-import") (part "BJT_NPNKSC1845"))
    )
    (comp (ref "Q70")
      (value "KSA992")
      (footprint "eagle-import:TRANSISTOR_TO92-ECB_P")
      (fields (field (name "SPICEPREFIX") "Q"))
      (libsource (lib "eagle-import") (part "BJT_PNPKSA992"))
    )
    (comp (ref "Q71")
      (value "KSC1845")
      (footprint "eagle-import:TRANSISTOR_TO92-ECB_N")
      (fields (field (name "SPICEPREFIX") "Q"))
      (libsource (lib "eagle-import") (part "BJT_NPNKSC1845"))
    )
    (comp (ref "Q72")
      (value "MJE15030")
      (footprint "eagle-import:TRANSISTOR_TO220_BCE_N")
      (fields (field (name "SPICEPREFIX") "Q"))
      (libsource (lib "eagle-import") (part "BJT_NPNMJE15030"))
    )
    (comp (ref "Q73")
      (value "KSC1845")
      (footprint "eagle-import:TRANSISTOR_TO92-ECB_N")
      (fields (field (name "SPICEPREFIX") "Q"))
      (libsource (lib "eagle-import") (part "BJT_NPNKSC1845"))
    )
    (comp (ref "Q74")
      (value "KSA992")
      (footprint "eagle-import:TRANSISTOR_TO92-ECB_P")
      (fields (field (name "SPICEPREFIX") "Q"))
      (libsource (lib "eagle-import") (part "BJT_PNPKSA992"))
    )
    (comp (ref "Q75")
      (value "KSC1845")
      (footprint "eagle-import:TRANSISTOR_TO92-ECB_N")
      (fields (field (name "SPICEPREFIX") "Q"))
      (libsource (lib "eagle-import") (part "BJT_NPNKSC1845"))
    )
    (comp (ref "Q76")
      (value "KSA992")
      (footprint "eagle-import:TRANSISTOR_TO92-ECB_P")
      (fields (field (name "SPICEPREFIX") "Q"))
      (libsource (lib "eagle-import") (part "BJT_PNPKSA992"))
    )
    (comp (ref "Q77")
      (value "MJL4281A")
      (footprint "eagle-import:TRANSISTOR_TO247_BCE_N")
      (fields (field (name "SPICEPREFIX") "Q"))
      (libsource (lib "eagle-import") (part "BJT_NPNMJL4281"))
    )
    (comp (ref "Q78")
      (value "MJL4302A")
      (footprint "eagle-import:TRANSISTOR_TO247_BCE_P")
      (fields (field (name "SPICEPREFIX") "Q"))
      (libsource (lib "eagle-import") (part "BJT_PNPMJL4302"))
    )
    (comp (ref "R51")
      (value "1k")
      (footprint "eagle-import:MINI_MELF-0204W")
      (fields (field (name "SPICEPREFIX") "R"))
      (libsource (lib "eagle-import") (part "R-EU_MELF0204W"))
    )
    (comp (ref "R52")
      (value "20k")
      (footprint "eagle-import:MINI_MELF-0204W")
      (fields (field (name "SPICEPREFIX") "R"))
      (libsource (lib "eagle-import") (part "R-EU_MELF0204W"))
    )
    (comp (ref "R53")
      (value "100k")
      (footprint "eagle-import:MINI_MELF-0204W")
      (fields (field (name "SPICEPREFIX") "R"))
      (libsource (lib "eagle-import") (part "R-EU_MELF0204W"))
    )
    (comp (ref "R54")
      (value "200")
      (footprint "eagle-import:MINI_MELF-0204W")
      (fields (field (name "SPICEPREFIX") "R"))
      (libsource (lib "eagle-import") (part "R-EU_MELF0204W"))
    )
    (comp (ref "R55")
      (value "10")
      (footprint "eagle-import:MINI_MELF-0204W")
      (fields (field (name "SPICEPREFIX") "R"))
      (libsource (lib "eagle-import") (part "R-EU_MELF0204W"))
    )
    (comp (ref "R56")
      (value "10")
      (footprint "eagle-import:MINI_MELF-0204W")
      (fields (field (name "SPICEPREFIX") "R"))
      (libsource (lib "eagle-import") (part "R-EU_MELF0204W"))
    )
    (comp (ref "R57")
      (value "200")
      (footprint "eagle-import:MINI_MELF-0204W")
      (fields (field (name "SPICEPREFIX") "R"))
      (libsource (lib "eagle-import") (part "R-EU_MELF0204W"))
    )
    (comp (ref "R58")
      (value "560")
      (footprint "eagle-import:MINI_MELF-0204W")
      (fields (field (name "SPICEPREFIX") "R"))
      (libsource (lib "eagle-import") (part "R-EU_MELF0204W"))
    )
    (comp (ref "R59")
      (value "10")
      (footprint "eagle-import:MINI_MELF-0204W")
      (fields (field (name "SPICEPREFIX") "R"))
      (libsource (lib "eagle-import") (part "R-EU_MELF0204W"))
    )
    (comp (ref "R60")
      (value "10")
      (footprint "eagle-import:MINI_MELF-0204W")
      (fields (field (name "SPICEPREFIX") "R"))
      (libsource (lib "eagle-import") (part "R-EU_MELF0204W"))
    )
    (comp (ref "R61")
      (value "560")
      (footprint "eagle-import:MINI_MELF-0204W")
      (fields (field (name "SPICEPREFIX") "R"))
      (libsource (lib "eagle-import") (part "R-EU_MELF0204W"))
    )
    (comp (ref "R62")
      (value "100")
      (footprint "eagle-import:MINI_MELF-0204W")
      (fields (field (name "SPICEPREFIX") "R"))
      (libsource (lib "eagle-import") (part "R-EU_MELF0204W"))
    )
    (comp (ref "R63")
      (value "200")
      (footprint "eagle-import:MINI_MELF-0204W")
      (fields (field (name "SPICEPREFIX") "R"))
      (libsource (lib "eagle-import") (part "R-EU_MELF0204W"))
    )
    (comp (ref "R64")
      (value "100")
      (footprint "eagle-import:MINI_MELF-0204W")
      (fields (field (name "SPICEPREFIX") "R"))
      (libsource (lib "eagle-import") (part "R-EU_MELF0204W"))
    )
    (comp (ref "R65")
      (value "68k")
      (footprint "eagle-import:MINI_MELF-0204W")
      (fields (field (name "SPICEPREFIX") "R"))
      (libsource (lib "eagle-import") (part "R-EU_MELF0204W"))
    )
    (comp (ref "R66")
      (value "500")
      (footprint "eagle-import:MINI_MELF-0204W")
      (fields (field (name "SPICEPREFIX") "R"))
      (libsource (lib "eagle-import") (part "R-EU_MELF0204W"))
    )
    (comp (ref "R67")
      (value "100")
      (footprint "eagle-import:MINI_MELF-0204W")
      (fields (field (name "SPICEPREFIX") "R"))
      (libsource (lib "eagle-import") (part "R-EU_MELF0204W"))
    )
    (comp (ref "R68")
      (value "5k")
      (footprint "eagle-import:MINI_MELF-0204W")
      (fields (field (name "SPICEPREFIX") "R"))
      (libsource (lib "eagle-import") (part "R-EU_MELF0204W"))
    )
    (comp (ref "R69")
      (value "5k")
      (footprint "eagle-import:MINI_MELF-0204W")
      (fields (field (name "SPICEPREFIX") "R"))
      (libsource (lib "eagle-import") (part "R-EU_MELF0204W"))
    )
    (comp (ref "R70")
      (value "100")
      (footprint "eagle-import:MINI_MELF-0204W")
      (fields (field (name "SPICEPREFIX") "R"))
      (libsource (lib "eagle-import") (part "R-EU_MELF0204W"))
    )
    (comp (ref "R71")
      (value "100")
      (footprint "eagle-import:MINI_MELF-0204W")
      (fields (field (name "SPICEPREFIX") "R"))
      (libsource (lib "eagle-import") (part "R-EU_MELF0204W"))
    )
    (comp (ref "R72")
      (value "100")
      (footprint "eagle-import:MINI_MELF-0204W")
      (fields (field (name "SPICEPREFIX") "R"))
      (libsource (lib "eagle-import") (part "R-EU_MELF0204W"))
    )
    (comp (ref "R73")
      (value "7k")
      (footprint "eagle-import:MINI_MELF-0204W")
      (fields (field (name "SPICEPREFIX") "R"))
      (libsource (lib "eagle-import") (part "R-EU_MELF0204W"))
    )
    (comp (ref "R74")
      (value "5k")
      (footprint "eagle-import:RTRIM3296W")
      (fields (field (name "SPICEPREFIX") "Z"))
      (libsource (lib "eagle-import") (part "R-TRIMM3296W"))
    )
    (comp (ref "R75")
      (value "1M")
      (footprint "eagle-import:MINI_MELF-0204W")
      (fields (field (name "SPICEPREFIX") "R"))
      (libsource (lib "eagle-import") (part "R-EU_MELF0204W"))
    )
    (comp (ref "R76")
      (value "1M")
      (footprint "eagle-import:MINI_MELF-0204W")
      (fields (field (name "SPICEPREFIX") "R"))
      (libsource (lib "eagle-import") (part "R-EU_MELF0204W"))
    )
    (comp (ref "R77")
      (value "1k")
      (footprint "eagle-import:MINI_MELF-0204W")
      (fields (field (name "SPICEPREFIX") "R"))
      (libsource (lib "eagle-import") (part "R-EU_MELF0204W"))
    )
    (comp (ref "R78")
      (value "220")
      (footprint "eagle-import:MINI_MELF-0204W")
      (fields (field (name "SPICEPREFIX") "R"))
      (libsource (lib "eagle-import") (part "R-EU_MELF0204W"))
    )
    (comp (ref "R79")
      (value "100k")
      (footprint "eagle-import:MINI_MELF-0204W")
      (fields (field (name "SPICEPREFIX") "R"))
      (libsource (lib "eagle-import") (part "R-EU_MELF0204W"))
    )
    (comp (ref "R80")
      (value "0.5")
      (footprint "eagle-import:R2512")
      (fields (field (name "SPICEPREFIX") "R"))
      (libsource (lib "eagle-import") (part "R-EU_R2512"))
    )
    (comp (ref "R81")
      (value "0.5")
      (footprint "eagle-import:R2512")
      (fields (field (name "SPICEPREFIX") "R"))
      (libsource (lib "eagle-import") (part "R-EU_R2512"))
    )
    (comp (ref "R82")
      (value "100k")
      (footprint "eagle-import:MINI_MELF-0204W")
      (fields (field (name "SPICEPREFIX") "R"))
      (libsource (lib "eagle-import") (part "R-EU_MELF0204W"))
    )
    (comp (ref "R83")
      (value "1k")
      (footprint "eagle-import:MINI_MELF-0204W")
      (fields (field (name "SPICEPREFIX") "R"))
      (libsource (lib "eagle-import") (part "R-EU_MELF0204W"))
    )
    (comp (ref "R84")
      (value "20k")
      (footprint "eagle-import:MINI_MELF-0204W")
      (fields (field (name "SPICEPREFIX") "R"))
      (libsource (lib "eagle-import") (part "R-EU_MELF0204W"))
    )
    (comp (ref "R85")
      (value "100k")
      (footprint "eagle-import:MINI_MELF-0204W")
      (fields (field (name "SPICEPREFIX") "R"))
      (libsource (lib "eagle-import") (part "R-EU_MELF0204W"))
    )
    (comp (ref "R86")
      (value "200")
      (footprint "eagle-import:MINI_MELF-0204W")
      (fields (field (name "SPICEPREFIX") "R"))
      (libsource (lib "eagle-import") (part "R-EU_MELF0204W"))
    )
    (comp (ref "R87")
      (value "10")
      (footprint "eagle-import:MINI_MELF-0204W")
      (fields (field (name "SPICEPREFIX") "R"))
      (libsource (lib "eagle-import") (part "R-EU_MELF0204W"))
    )
    (comp (ref "R88")
      (value "10")
      (footprint "eagle-import:MINI_MELF-0204W")
      (fields (field (name "SPICEPREFIX") "R"))
      (libsource (lib "eagle-import") (part "R-EU_MELF0204W"))
    )
    (comp (ref "R89")
      (value "200")
      (footprint "eagle-import:MINI_MELF-0204W")
      (fields (field (name "SPICEPREFIX") "R"))
      (libsource (lib "eagle-import") (part "R-EU_MELF0204W"))
    )
    (comp (ref "R90")
      (value "560")
      (footprint "eagle-import:MINI_MELF-0204W")
      (fields (field (name "SPICEPREFIX") "R"))
      (libsource (lib "eagle-import") (part "R-EU_MELF0204W"))
    )
    (comp (ref "R91")
      (value "10")
      (footprint "eagle-import:MINI_MELF-0204W")
      (fields (field (name "SPICEPREFIX") "R"))
      (libsource (lib "eagle-import") (part "R-EU_MELF0204W"))
    )
    (comp (ref "R92")
      (value "10")
      (footprint "eagle-import:MINI_MELF-0204W")
      (fields (field (name "SPICEPREFIX") "R"))
      (libsource (lib "eagle-import") (part "R-EU_MELF0204W"))
    )
    (comp (ref "R93")
      (value "560")
      (footprint "eagle-import:MINI_MELF-0204W")
      (fields (field (name "SPICEPREFIX") "R"))
      (libsource (lib "eagle-import") (part "R-EU_MELF0204W"))
    )
    (comp (ref "R94")
      (value "100")
      (footprint "eagle-import:MINI_MELF-0204W")
      (fields (field (name "SPICEPREFIX") "R"))
      (libsource (lib "eagle-import") (part "R-EU_MELF0204W"))
    )
    (comp (ref "R95")
      (value "200")
      (footprint "eagle-import:MINI_MELF-0204W")
      (fields (field (name "SPICEPREFIX") "R"))
      (libsource (lib "eagle-import") (part "R-EU_MELF0204W"))
    )
    (comp (ref "R96")
      (value "100")
      (footprint "eagle-import:MINI_MELF-0204W")
      (fields (field (name "SPICEPREFIX") "R"))
      (libsource (lib "eagle-import") (part "R-EU_MELF0204W"))
    )
    (comp (ref "R97")
      (value "68k")
      (footprint "eagle-import:MINI_MELF-0204W")
      (fields (field (name "SPICEPREFIX") "R"))
      (libsource (lib "eagle-import") (part "R-EU_MELF0204W"))
    )
    (comp (ref "R98")
      (value "500")
      (footprint "eagle-import:MINI_MELF-0204W")
      (fields (field (name "SPICEPREFIX") "R"))
      (libsource (lib "eagle-import") (part "R-EU_MELF0204W"))
    )
    (comp (ref "R99")
      (value "100")
      (footprint "eagle-import:MINI_MELF-0204W")
      (fields (field (name "SPICEPREFIX") "R"))
      (libsource (lib "eagle-import") (part "R-EU_MELF0204W"))
    )
    (comp (ref "R100")
      (value "5k")
      (footprint "eagle-import:MINI_MELF-0204W")
      (fields (field (name "SPICEPREFIX") "R"))
      (libsource (lib "eagle-import") (part "R-EU_MELF0204W"))
    )
    (comp (ref "R101")
      (value "5k")
      (footprint "eagle-import:MINI_MELF-0204W")
      (fields (field (name "SPICEPREFIX") "R"))
      (libsource (lib "eagle-import") (part "R-EU_MELF0204W"))
    )
    (comp (ref "R102")
      (value "100")
      (footprint "eagle-import:MINI_MELF-0204W")
      (fields (field (name "SPICEPREFIX") "R"))
      (libsource (lib "eagle-import") (part "R-EU_MELF0204W"))
    )
    (comp (ref "R103")
      (value "100")
      (footprint "eagle-import:MINI_MELF-0204W")
      (fields (field (name "SPICEPREFIX") "R"))
      (libsource (lib "eagle-import") (part "R-EU_MELF0204W"))
    )
    (comp (ref "R104")
      (value "100")
      (footprint "eagle-import:MINI_MELF-0204W")
      (fields (field (name "SPICEPREFIX") "R"))
      (libsource (lib "eagle-import") (part "R-EU_MELF0204W"))
    )
    (comp (ref "R105")
      (value "7k")
      (footprint "eagle-import:MINI_MELF-0204W")
      (fields (field (name "SPICEPREFIX") "R"))
      (libsource (lib "eagle-import") (part "R-EU_MELF0204W"))
    )
    (comp (ref "R106")
      (value "5k")
      (footprint "eagle-import:RTRIM3296W")
      (fields (field (name "SPICEPREFIX") "Z"))
      (libsource (lib "eagle-import") (part "R-TRIMM3296W"))
    )
    (comp (ref "R107")
      (value "1M")
      (footprint "eagle-import:MINI_MELF-0204W")
      (fields (field (name "SPICEPREFIX") "R"))
      (libsource (lib "eagle-import") (part "R-EU_MELF0204W"))
    )
    (comp (ref "R108")
      (value "1M")
      (footprint "eagle-import:MINI_MELF-0204W")
      (fields (field (name "SPICEPREFIX") "R"))
      (libsource (lib "eagle-import") (part "R-EU_MELF0204W"))
    )
    (comp (ref "R109")
      (value "1k")
      (footprint "eagle-import:MINI_MELF-0204W")
      (fields (field (name "SPICEPREFIX") "R"))
      (libsource (lib "eagle-import") (part "R-EU_MELF0204W"))
    )
    (comp (ref "R110")
      (value "220")
      (footprint "eagle-import:MINI_MELF-0204W")
      (fields (field (name "SPICEPREFIX") "R"))
      (libsource (lib "eagle-import") (part "R-EU_MELF0204W"))
    )
    (comp (ref "R111")
      (value "100k")
      (footprint "eagle-import:MINI_MELF-0204W")
      (fields (field (name "SPICEPREFIX") "R"))
      (libsource (lib "eagle-import") (part "R-EU_MELF0204W"))
    )
    (comp (ref "R112")
      (value "0.5")
      (footprint "eagle-import:R2512")
      (fields (field (name "SPICEPREFIX") "R"))
      (libsource (lib "eagle-import") (part "R-EU_R2512"))
    )
    (comp (ref "R113")
      (value "0.5")
      (footprint "eagle-import:R2512")
      (fields (field (name "SPICEPREFIX") "R"))
      (libsource (lib "eagle-import") (part "R-EU_R2512"))
    )
    (comp (ref "R114")
      (value "100k")
      (footprint "eagle-import:MINI_MELF-0204W")
      (fields (field (name "SPICEPREFIX") "R"))
      (libsource (lib "eagle-import") (part "R-EU_MELF0204W"))
    )
    (comp (ref "R133")
      (value "R-EU_R2512")
      (footprint "eagle-import:R2512")
      (libsource (lib "eagle-import") (part "R-EU_R2512"))
    )
    (comp (ref "C2")
      (value "0.1uF")
      (footprint "eagle-import:C0805")
      (libsource (lib "eagle-import") (part "C-EUC0805"))
    )
    (comp (ref "C37")
      (value "10000uF")
      (footprint "eagle-import:EB35D-8.5")
      (libsource (lib "eagle-import") (part "CPOL-EU"))
    )
    (comp (ref "C38")
      (value "10000uF")
      (footprint "eagle-import:EB35D-8.5")
      (libsource (lib "eagle-import") (part "CPOL-EU"))
    )
    (comp (ref "C39")
      (value "0.1uF")
      (footprint "eagle-import:C050-045X075")
      (libsource (lib "eagle-import") (part "C-EU050-045X075"))
    )
    (comp (ref "C40")
      (value "10uF")
      (footprint "eagle-import:C1206")
      (libsource (lib "eagle-import") (part "C-EUC1206"))
    )
    (comp (ref "C41")
      (value "10uF")
      (footprint "eagle-import:C1206")
      (libsource (lib "eagle-import") (part "C-EUC1206"))
    )
    (comp (ref "C42")
      (value "0.1uF")
      (footprint "eagle-import:C050-045X075")
      (libsource (lib "eagle-import") (part "C-EU050-045X075"))
    )
    (comp (ref "C43")
      (value "0.1uF")
      (footprint "eagle-import:C0805")
      (libsource (lib "eagle-import") (part "C-EUC0805"))
    )
    (comp (ref "C44")
      (value "0.1uF")
      (footprint "eagle-import:C0805")
      (libsource (lib "eagle-import") (part "C-EUC0805"))
    )
    (comp (ref "C45")
      (value "0.1uF")
      (footprint "eagle-import:C0805")
      (libsource (lib "eagle-import") (part "C-EUC0805"))
    )
    (comp (ref "C46")
      (value "0.1uF")
      (footprint "eagle-import:C0805")
      (libsource (lib "eagle-import") (part "C-EUC0805"))
    )
    (comp (ref "C47")
      (value "10uF")
      (footprint "eagle-import:C1206")
      (libsource (lib "eagle-import") (part "C-EUC1206"))
    )
    (comp (ref "C48")
      (value "10uF")
      (footprint "eagle-import:C1206")
      (libsource (lib "eagle-import") (part "C-EUC1206"))
    )
    (comp (ref "C49")
      (value "0.1uF")
      (footprint "eagle-import:C0805")
      (libsource (lib "eagle-import") (part "C-EUC0805"))
    )
    (comp (ref "C50")
      (value "0.1uF")
      (footprint "eagle-import:C0805")
      (libsource (lib "eagle-import") (part "C-EUC0805"))
    )
    (comp (ref "C51")
      (value "47p")
      (footprint "eagle-import:C0805")
      (libsource (lib "eagle-import") (part "C-EUC0805"))
    )
    (comp (ref "C52")
      (value "47p")
      (footprint "eagle-import:C0805")
      (libsource (lib "eagle-import") (part "C-EUC0805"))
    )
    (comp (ref "C53")
      (value "10uF")
      (footprint "eagle-import:C1206")
      (libsource (lib "eagle-import") (part "C-EUC1206"))
    )
    (comp (ref "C54")
      (value "10uF")
      (footprint "eagle-import:C1206")
      (libsource (lib "eagle-import") (part "C-EUC1206"))
    )
    (comp (ref "C55")
      (value "4.7uF")
      (footprint "eagle-import:C050-075X075")
      (libsource (lib "eagle-import") (part "C-EU050-075X075"))
    )
    (comp (ref "C56")
      (value "4.7uF")
      (footprint "eagle-import:C050-075X075")
      (libsource (lib "eagle-import") (part "C-EU050-075X075"))
    )
    (comp (ref "C58")
      (value "0.1uF")
      (footprint "eagle-import:C050-045X075")
      (libsource (lib "eagle-import") (part "C-EU050-045X075"))
    )
    (comp (ref "C60")
      (value "0.1uF")
      (footprint "eagle-import:C050-045X075")
      (libsource (lib "eagle-import") (part "C-EU050-045X075"))
    )
    (comp (ref "C65")
      (value "10uF")
      (footprint "eagle-import:C1206")
      (libsource (lib "eagle-import") (part "C-EUC1206"))
    )
    (comp (ref "C66")
      (value "10uF")
      (footprint "eagle-import:C1206")
      (libsource (lib "eagle-import") (part "C-EUC1206"))
    )
    (comp (ref "C67")
      (value "0.1uF")
      (footprint "eagle-import:C0805")
      (libsource (lib "eagle-import") (part "C-EUC0805"))
    )
    (comp (ref "C68")
      (value "0.1uF")
      (footprint "eagle-import:C0805")
      (libsource (lib "eagle-import") (part "C-EUC0805"))
    )
    (comp (ref "C69")
      (value "0.1uF")
      (footprint "eagle-import:C0805")
      (libsource (lib "eagle-import") (part "C-EUC0805"))
    )
    (comp (ref "C70")
      (value "0.1uF")
      (footprint "eagle-import:C0805")
      (libsource (lib "eagle-import") (part "C-EUC0805"))
    )
    (comp (ref "C71")
      (value "0.1uF")
      (footprint "eagle-import:C0805")
      (libsource (lib "eagle-import") (part "C-EUC0805"))
    )
    (comp (ref "C72")
      (value "0.1uF")
      (footprint "eagle-import:C0805")
      (libsource (lib "eagle-import") (part "C-EUC0805"))
    )
    (comp (ref "D13")
      (value "BZT55B10")
      (footprint "eagle-import:SOD80C")
      (libsource (lib "eagle-import") (part "DIODE-SOD80C"))
    )
    (comp (ref "D14")
      (value "BZT55B10")
      (footprint "eagle-import:SOD80C")
      (libsource (lib "eagle-import") (part "DIODE-SOD80C"))
    )
    (comp (ref "D15")
      (value "S1G")
      (footprint "eagle-import:DO214AA")
      (libsource (lib "eagle-import") (part "DIODE-DO214AA"))
    )
    (comp (ref "D16")
      (value "S1G")
      (footprint "eagle-import:DO214AA")
      (libsource (lib "eagle-import") (part "DIODE-DO214AA"))
    )
    (comp (ref "D17")
      (value "LT1236-10")
      (footprint "eagle-import:SO8")
      (libsource (lib "eagle-import") (part "LINEAR-TECHNOLOGY_LT1021-VSO-8"))
    )
    (comp (ref "D18")
      (value "LT1236-10")
      (footprint "eagle-import:SO8")
      (libsource (lib "eagle-import") (part "LINEAR-TECHNOLOGY_LT1021-VSO-8"))
    )
    (comp (ref "D19")
      (value "LL4148")
      (footprint "eagle-import:SOD80C")
      (fields (field (name "SPICEPREFIX") "D"))
      (libsource (lib "eagle-import") (part "DIODE-SOD80C"))
    )
    (comp (ref "D20")
      (value "LL4148")
      (footprint "eagle-import:SOD80C")
      (fields (field (name "SPICEPREFIX") "D"))
      (libsource (lib "eagle-import") (part "DIODE-SOD80C"))
    )
    (comp (ref "D21")
      (value "LL4148")
      (footprint "eagle-import:SOD80C")
      (fields (field (name "SPICEPREFIX") "D"))
      (libsource (lib "eagle-import") (part "DIODE-SOD80C"))
    )
    (comp (ref "D22")
      (value "LL4148")
      (footprint "eagle-import:SOD80C")
      (fields (field (name "SPICEPREFIX") "D"))
      (libsource (lib "eagle-import") (part "DIODE-SOD80C"))
    )
    (comp (ref "H8")
      (value "HOLE")
      (footprint "eagle-import:M3_HOLE")
      (libsource (lib "eagle-import") (part "HOLE"))
    )
    (comp (ref "IC5")
      (value "OPA827")
      (footprint "eagle-import:SOIC8")
      (libsource (lib "eagle-import") (part "LT10S837C"))
    )
    (comp (ref "IC6")
      (value "OPA827")
      (footprint "eagle-import:SOIC8")
      (libsource (lib "eagle-import") (part "LT10S837C"))
    )
    (comp (ref "LED13")
      (value "RED")
      (footprint "eagle-import:LED_SML1206")
      (libsource (lib "eagle-import") (part "LEDVWV1206"))
    )
    (comp (ref "LED14")
      (value "RED")
      (footprint "eagle-import:LED_SML1206")
      (libsource (lib "eagle-import") (part "LEDVWV1206"))
    )
    (comp (ref "LED15")
      (value "RED")
      (footprint "eagle-import:LED_SML1206")
      (libsource (lib "eagle-import") (part "LEDVWV1206"))
    )
    (comp (ref "LED16")
      (value "RED")
      (footprint "eagle-import:LED_SML1206")
      (libsource (lib "eagle-import") (part "LEDVWV1206"))
    )
    (comp (ref "LED17")
      (value "RED")
      (footprint "eagle-import:LED_SML1206")
      (libsource (lib "eagle-import") (part "LEDVWV1206"))
    )
    (comp (ref "LED18")
      (value "RED")
      (footprint "eagle-import:LED_SML1206")
      (libsource (lib "eagle-import") (part "LEDVWV1206"))
    )
    (comp (ref "Q79")
      (value "KSC1845")
      (footprint "eagle-import:TRANSISTOR_TO92-ECB_N")
      (libsource (lib "eagle-import") (part "BJT_NPNKSC1845"))
    )
    (comp (ref "Q80")
      (value "KSA992")
      (footprint "eagle-import:TRANSISTOR_TO92-ECB_P")
      (libsource (lib "eagle-import") (part "BJT_PNPKSA992"))
    )
    (comp (ref "Q81")
      (value "KSA992")
      (footprint "eagle-import:TRANSISTOR_TO92-ECB_P")
      (libsource (lib "eagle-import") (part "BJT_PNPKSA992"))
    )
    (comp (ref "Q82")
      (value "KSC1845")
      (footprint "eagle-import:TRANSISTOR_TO92-ECB_N")
      (libsource (lib "eagle-import") (part "BJT_NPNKSC1845"))
    )
    (comp (ref "Q83")
      (value "KSA992")
      (footprint "eagle-import:TRANSISTOR_TO92-ECB_P")
      (libsource (lib "eagle-import") (part "BJT_PNPKSA992"))
    )
    (comp (ref "Q84")
      (value "KSC1845")
      (footprint "eagle-import:TRANSISTOR_TO92-ECB_N")
      (libsource (lib "eagle-import") (part "BJT_NPNKSC1845"))
    )
    (comp (ref "Q85")
      (value "KSA992")
      (footprint "eagle-import:TRANSISTOR_TO92-ECB_P")
      (libsource (lib "eagle-import") (part "BJT_PNPKSA992"))
    )
    (comp (ref "Q86")
      (value "KSC1845")
      (footprint "eagle-import:TRANSISTOR_TO92-ECB_N")
      (libsource (lib "eagle-import") (part "BJT_NPNKSC1845"))
    )
    (comp (ref "Q87")
      (value "KSC1845")
      (footprint "eagle-import:TRANSISTOR_TO92-ECB_N")
      (libsource (lib "eagle-import") (part "BJT_NPNKSC1845"))
    )
    (comp (ref "Q88")
      (value "KSA992")
      (footprint "eagle-import:TRANSISTOR_TO92-ECB_P")
      (libsource (lib "eagle-import") (part "BJT_PNPKSA992"))
    )
    (comp (ref "Q89")
      (value "MJL4281A")
      (footprint "eagle-import:TRANSISTOR_TO247_BCE_N")
      (libsource (lib "eagle-import") (part "BJT_NPNMJL4281"))
    )
    (comp (ref "Q90")
      (value "MJL4302A")
      (footprint "eagle-import:TRANSISTOR_TO247_BCE_P")
      (libsource (lib "eagle-import") (part "BJT_PNPMJL4302"))
    )
    (comp (ref "Q91")
      (value "DN2540")
      (footprint "eagle-import:TRANSISTOR_TO92-SGD_N")
      (libsource (lib "eagle-import") (part "DN2540"))
    )
    (comp (ref "Q92")
      (value "DN2540")
      (footprint "eagle-import:TRANSISTOR_TO92-SGD_N")
      (libsource (lib "eagle-import") (part "DN2540"))
    )
    (comp (ref "R115")
      (value "10k")
      (footprint "eagle-import:MINI_MELF-0204W")
      (libsource (lib "eagle-import") (part "R-EU_MELF0204W"))
    )
    (comp (ref "R116")
      (value "10k")
      (footprint "eagle-import:MINI_MELF-0204W")
      (libsource (lib "eagle-import") (part "R-EU_MELF0204W"))
    )
    (comp (ref "R117")
      (value "1k")
      (footprint "eagle-import:MINI_MELF-0204W")
      (libsource (lib "eagle-import") (part "R-EU_MELF0204W"))
    )
    (comp (ref "R118")
      (value "1k")
      (footprint "eagle-import:MINI_MELF-0204W")
      (libsource (lib "eagle-import") (part "R-EU_MELF0204W"))
    )
    (comp (ref "R119")
      (value "100")
      (footprint "eagle-import:MINI_MELF-0204W")
      (libsource (lib "eagle-import") (part "R-EU_MELF0204W"))
    )
    (comp (ref "R120")
      (value "10")
      (footprint "eagle-import:MINI_MELF-0204W")
      (libsource (lib "eagle-import") (part "R-EU_MELF0204W"))
    )
    (comp (ref "R121")
      (value "10")
      (footprint "eagle-import:MINI_MELF-0204W")
      (libsource (lib "eagle-import") (part "R-EU_MELF0204W"))
    )
    (comp (ref "R122")
      (value "100")
      (footprint "eagle-import:MINI_MELF-0204W")
      (libsource (lib "eagle-import") (part "R-EU_MELF0204W"))
    )
    (comp (ref "R123")
      (value "10")
      (footprint "eagle-import:MINI_MELF-0204W")
      (libsource (lib "eagle-import") (part "R-EU_MELF0204W"))
    )
    (comp (ref "R124")
      (value "10")
      (footprint "eagle-import:MINI_MELF-0204W")
      (libsource (lib "eagle-import") (part "R-EU_MELF0204W"))
    )
    (comp (ref "R125")
      (value "1k")
      (footprint "eagle-import:MINI_MELF-0204W")
      (libsource (lib "eagle-import") (part "R-EU_MELF0204W"))
    )
    (comp (ref "R126")
      (value "1k")
      (footprint "eagle-import:MINI_MELF-0204W")
      (libsource (lib "eagle-import") (part "R-EU_MELF0204W"))
    )
    (comp (ref "R127")
      (value "1.5k")
      (footprint "eagle-import:MINI_MELF-0204W")
      (libsource (lib "eagle-import") (part "R-EU_MELF0204W"))
    )
    (comp (ref "R128")
      (value "1.5k")
      (footprint "eagle-import:MINI_MELF-0204W")
      (libsource (lib "eagle-import") (part "R-EU_MELF0204W"))
    )
    (comp (ref "R129")
      (value "1.5k")
      (footprint "eagle-import:MINI_MELF-0204W")
      (libsource (lib "eagle-import") (part "R-EU_MELF0204W"))
    )
    (comp (ref "R130")
      (value "1.5k")
      (footprint "eagle-import:MINI_MELF-0204W")
      (libsource (lib "eagle-import") (part "R-EU_MELF0204W"))
    )
    (comp (ref "R131")
      (value "10k")
      (footprint "eagle-import:MINI_MELF-0204W")
      (libsource (lib "eagle-import") (part "R-EU_MELF0204W"))
    )
    (comp (ref "R132")
      (value "10k")
      (footprint "eagle-import:MINI_MELF-0204W")
      (libsource (lib "eagle-import") (part "R-EU_MELF0204W"))
    )
    (comp (ref "R136")
      (value "10k")
      (footprint "eagle-import:MINI_MELF-0204W")
      (libsource (lib "eagle-import") (part "R-EU_MELF0204W"))
    )
    (comp (ref "R137")
      (value "10k")
      (footprint "eagle-import:MINI_MELF-0204W")
      (libsource (lib "eagle-import") (part "R-EU_MELF0204W"))
    )
    (comp (ref "R138")
      (value "10k")
      (footprint "eagle-import:MINI_MELF-0204W")
      (libsource (lib "eagle-import") (part "R-EU_MELF0204W"))
    )
    (comp (ref "R139")
      (value "10k")
      (footprint "eagle-import:MINI_MELF-0204W")
      (libsource (lib "eagle-import") (part "R-EU_MELF0204W"))
    )
    (comp (ref "R140")
      (value "10k")
      (footprint "eagle-import:MINI_MELF-0204W")
      (libsource (lib "eagle-import") (part "R-EU_MELF0204W"))
    )
    (comp (ref "R141")
      (value "10k")
      (footprint "eagle-import:MINI_MELF-0204W")
      (libsource (lib "eagle-import") (part "R-EU_MELF0204W"))
    )
    (comp (ref "SJ1") (value "SJ") (footprint "eagle-import:SJ") (libsource (lib "eagle-import") (part "SJ")))
    (comp (ref "U$5")
      (value "TPS7A39WSON10-7A39")
      (footprint "eagle-import:SON50P300X300X80-11T165X240N")
      (libsource (lib "eagle-import") (part "TPS7A39WSON10-7A39"))
    )
  )
  (nets
    (net (code "1") (name "+18V") (class "Default")
      (node (ref "C14") (pin "2") (pinfunction "2_2") (pintype "passive"))
      (node (ref "C23") (pin "1") (pinfunction "1_1") (pintype "passive"))
      (node (ref "C3") (pin "2") (pinfunction "2_2") (pintype "passive"))
      (node (ref "C33") (pin "1") (pinfunction "1_1") (pintype "passive"))
      (node (ref "C69") (pin "1") (pinfunction "1_1") (pintype "passive"))
      (node (ref "C71") (pin "1") (pinfunction "1_1") (pintype "passive"))
      (node (ref "IC1") (pin "7") (pinfunction "V+_7") (pintype "power_in"))
      (node (ref "IC2") (pin "7") (pinfunction "V+_7") (pintype "power_in"))
      (node (ref "IC3") (pin "7") (pinfunction "V+_7") (pintype "power_in"))
      (node (ref "IC4") (pin "7") (pinfunction "V+_7") (pintype "power_in"))
      (node (ref "R136") (pin "2") (pinfunction "2_2") (pintype "passive"))
      (node (ref "R141") (pin "1") (pinfunction "1_1") (pintype "passive"))
      (node (ref "U$5") (pin "10") (pinfunction "O+_10") (pintype "bidirectional"))
    )
    (net (code "2") (name "-18V") (class "Default")
      (node (ref "C15") (pin "1") (pinfunction "1_1") (pintype "passive"))
      (node (ref "C24") (pin "2") (pinfunction "2_2") (pintype "passive"))
      (node (ref "C34") (pin "2") (pinfunction "2_2") (pintype "passive"))
      (node (ref "C4") (pin "1") (pinfunction "1_1") (pintype "passive"))
      (node (ref "C70") (pin "2") (pinfunction "2_2") (pintype "passive"))
      (node (ref "C72") (pin "2") (pinfunction "2_2") (pintype "passive"))
      (node (ref "IC1") (pin "4") (pinfunction "V-_4") (pintype "power_in"))
      (node (ref "IC2") (pin "4") (pinfunction "V-_4") (pintype "power_in"))
      (node (ref "IC3") (pin "4") (pinfunction "V-_4") (pintype "power_in"))
      (node (ref "IC4") (pin "4") (pinfunction "V-_4") (pintype "power_in"))
      (node (ref "R139") (pin "1") (pinfunction "1_1") (pintype "passive"))
      (node (ref "R140") (pin "1") (pinfunction "1_1") (pintype "passive"))
      (node (ref "U$5") (pin "6") (pinfunction "O-_6") (pintype "bidirectional"))
    )
    (net (code "3") (name "AC1") (class "Default")
      (node (ref "Q100") (pin "5") (pinfunction "D_5") (pintype "passive"))
      (node (ref "Q100") (pin "6") (pinfunction "D_6") (pintype "passive"))
      (node (ref "Q100") (pin "7") (pinfunction "D_7") (pintype "passive"))
      (node (ref "Q100") (pin "8") (pinfunction "D_8") (pintype "passive"))
      (node (ref "Q100") (pin "TH") (pinfunction "D_TH") (pintype "passive"))
      (node (ref "Q97") (pin "1") (pinfunction "S_1") (pintype "passive"))
      (node (ref "Q97") (pin "2") (pinfunction "S_2") (pintype "passive"))
      (node (ref "Q97") (pin "3") (pinfunction "S_3") (pintype "passive"))
      (node (ref "U$2") (pin "1") (pinfunction "1_IN2_1") (pintype "bidirectional"))
      (node (ref "X3") (pin "2") (pinfunction "S_2") (pintype "passive"))
    )
    (net (code "4") (name "AC2") (class "Default")
      (node (ref "Q98") (pin "1") (pinfunction "S_1") (pintype "passive"))
      (node (ref "Q98") (pin "2") (pinfunction "S_2") (pintype "passive"))
      (node (ref "Q98") (pin "3") (pinfunction "S_3") (pintype "passive"))
      (node (ref "Q99") (pin "5") (pinfunction "D_5") (pintype "passive"))
      (node (ref "Q99") (pin "6") (pinfunction "D_6") (pintype "passive"))
      (node (ref "Q99") (pin "7") (pinfunction "D_7") (pintype "passive"))
      (node (ref "Q99") (pin "8") (pinfunction "D_8") (pintype "passive"))
      (node (ref "Q99") (pin "TH") (pinfunction "D_TH") (pintype "passive"))
      (node (ref "U$2") (pin "12") (pinfunction "8_IN1_12") (pintype "bidirectional"))
      (node (ref "X3") (pin "1") (pinfunction "S_1") (pintype "passive"))
    )
    (net (code "5") (name "AC3") (class "Default")
      (node (ref "Q105") (pin "1") (pinfunction "S_1") (pintype "passive"))
      (node (ref "Q105") (pin "2") (pinfunction "S_2") (pintype "passive"))
      (node (ref "Q105") (pin "3") (pinfunction "S_3") (pintype "passive"))
      (node (ref "Q108") (pin "5") (pinfunction "D_5") (pintype "passive"))
      (node (ref "Q108") (pin "6") (pinfunction "D_6") (pintype "passive"))
      (node (ref "Q108") (pin "7") (pinfunction "D_7") (pintype "passive"))
      (node (ref "Q108") (pin "8") (pinfunction "D_8") (pintype "passive"))
      (node (ref "Q108") (pin "TH") (pinfunction "D_TH") (pintype "passive"))
      (node (ref "U$4") (pin "1") (pinfunction "1_IN2_1") (pintype "bidirectional"))
      (node (ref "X2") (pin "2") (pinfunction "S_2") (pintype "passive"))
    )
    (net (code "6") (name "AC4") (class "Default")
      (node (ref "Q106") (pin "1") (pinfunction "S_1") (pintype "passive"))
      (node (ref "Q106") (pin "2") (pinfunction "S_2") (pintype "passive"))
      (node (ref "Q106") (pin "3") (pinfunction "S_3") (pintype "passive"))
      (node (ref "Q107") (pin "5") (pinfunction "D_5") (pintype "passive"))
      (node (ref "Q107") (pin "6") (pinfunction "D_6") (pintype "passive"))
      (node (ref "Q107") (pin "7") (pinfunction "D_7") (pintype "passive"))
      (node (ref "Q107") (pin "8") (pinfunction "D_8") (pintype "passive"))
      (node (ref "Q107") (pin "TH") (pinfunction "D_TH") (pintype "passive"))
      (node (ref "U$4") (pin "12") (pinfunction "8_IN1_12") (pintype "bidirectional"))
      (node (ref "X2") (pin "1") (pinfunction "S_1") (pintype "passive"))
    )
    (net (code "7") (name "BOUT+") (class "Default")
      (node (ref "R29") (pin "1") (pinfunction "1_1") (pintype "passive"))
      (node (ref "R30") (pin "1") (pinfunction "1_1") (pintype "passive"))
      (node (ref "R31") (pin "2") (pinfunction "2_2") (pintype "passive"))
      (node (ref "R34") (pin "1") (pinfunction "1_1") (pintype "passive"))
      (node (ref "R35") (pin "2") (pinfunction "2_2") (pintype "passive"))
      (node (ref "R51") (pin "2") (pinfunction "2_2") (pintype "passive"))
    )
    (net (code "8") (name "BOUT-") (class "Default")
      (node (ref "R44") (pin "1") (pinfunction "1_1") (pintype "passive"))
      (node (ref "R45") (pin "1") (pinfunction "1_1") (pintype "passive"))
      (node (ref "R46") (pin "2") (pinfunction "2_2") (pintype "passive"))
      (node (ref "R49") (pin "1") (pinfunction "1_1") (pintype "passive"))
      (node (ref "R50") (pin "2") (pinfunction "2_2") (pintype "passive"))
      (node (ref "R83") (pin "2") (pinfunction "2_2") (pintype "passive"))
    )
    (net (code "9") (name "GND") (class "Default")
      (node (ref "C10") (pin "1") (pinfunction "1_1") (pintype "passive"))
      (node (ref "C11") (pin "2") (pinfunction "2_2") (pintype "passive"))
      (node (ref "C12") (pin "1") (pinfunction "1_1") (pintype "passive"))
      (node (ref "C14") (pin "1") (pinfunction "1_1") (pintype "passive"))
      (node (ref "C15") (pin "2") (pinfunction "2_2") (pintype "passive"))
      (node (ref "C17") (pin "2") (pinfunction "2_2") (pintype "passive"))
      (node (ref "C19") (pin "1") (pinfunction "1_1") (pintype "passive"))
      (node (ref "C2") (pin "2") (pinfunction "2_2") (pintype "passive"))
      (node (ref "C20") (pin "2") (pinfunction "2_2") (pintype "passive"))
      (node (ref "C22") (pin "1") (pinfunction "1_1") (pintype "passive"))
      (node (ref "C23") (pin "2") (pinfunction "2_2") (pintype "passive"))
      (node (ref "C24") (pin "1") (pinfunction "1_1") (pintype "passive"))
      (node (ref "C25") (pin "-") (pinfunction "-_-") (pintype "passive"))
      (node (ref "C26") (pin "+") (pinfunction "+_+") (pintype "passive"))
      (node (ref "C27") (pin "2") (pinfunction "2_2") (pintype "passive"))
      (node (ref "C29") (pin "1") (pinfunction "1_1") (pintype "passive"))
      (node (ref "C3") (pin "1") (pinfunction "1_1") (pintype "passive"))
      (node (ref "C30") (pin "2") (pinfunction "2_2") (pintype "passive"))
      (node (ref "C32") (pin "1") (pinfunction "1_1") (pintype "passive"))
      (node (ref "C33") (pin "2") (pinfunction "2_2") (pintype "passive"))
      (node (ref "C34") (pin "1") (pinfunction "1_1") (pintype "passive"))
      (node (ref "C35") (pin "-") (pinfunction "-_-") (pintype "passive"))
      (node (ref "C36") (pin "+") (pinfunction "+_+") (pintype "passive"))
      (node (ref "C37") (pin "-") (pinfunction "-_-") (pintype "passive"))
      (node (ref "C38") (pin "+") (pinfunction "+_+") (pintype "passive"))
      (node (ref "C39") (pin "2") (pinfunction "2_2") (pintype "passive"))
      (node (ref "C4") (pin "2") (pinfunction "2_2") (pintype "passive"))
      (node (ref "C42") (pin "1") (pinfunction "1_1") (pintype "passive"))
      (node (ref "C45") (pin "1") (pinfunction "1_1") (pintype "passive"))
      (node (ref "C46") (pin "2") (pinfunction "2_2") (pintype "passive"))
      (node (ref "C47") (pin "2") (pinfunction "2_2") (pintype "passive"))
      (node (ref "C48") (pin "1") (pinfunction "1_1") (pintype "passive"))
      (node (ref "C49") (pin "2") (pinfunction "2_2") (pintype "passive"))
      (node (ref "C5") (pin "-") (pinfunction "-_-") (pintype "passive"))
      (node (ref "C50") (pin "1") (pinfunction "1_1") (pintype "passive"))
      (node (ref "C55") (pin "1") (pinfunction "1_1") (pintype "passive"))
      (node (ref "C56") (pin "2") (pinfunction "2_2") (pintype "passive"))
      (node (ref "C57") (pin "2") (pinfunction "2_2") (pintype "passive"))
      (node (ref "C58") (pin "1") (pinfunction "1_1") (pintype "passive"))
      (node (ref "C59") (pin "1") (pinfunction "1_1") (pintype "passive"))
      (node (ref "C6") (pin "+") (pinfunction "+_+") (pintype "passive"))
      (node (ref "C60") (pin "2") (pinfunction "2_2") (pintype "passive"))
      (node (ref "C65") (pin "2") (pinfunction "2_2") (pintype "passive"))
      (node (ref "C66") (pin "2") (pinfunction "2_2") (pintype "passive"))
      (node (ref "C67") (pin "2") (pinfunction "2_2") (pintype "passive"))
      (node (ref "C68") (pin "2") (pinfunction "2_2") (pintype "passive"))
      (node (ref "C69") (pin "2") (pinfunction "2_2") (pintype "passive"))
      (node (ref "C7") (pin "-") (pinfunction "-_-") (pintype "passive"))
      (node (ref "C70") (pin "1") (pinfunction "1_1") (pintype "passive"))
      (node (ref "C74") (pin "2") (pinfunction "2_2") (pintype "passive"))
      (node (ref "C75") (pin "1") (pinfunction "1_1") (pintype "passive"))
      (node (ref "C8") (pin "+") (pinfunction "+_+") (pintype "passive"))
      (node (ref "C9") (pin "2") (pinfunction "2_2") (pintype "passive"))
      (node (ref "D17") (pin "4") (pinfunction "GND_4") (pintype "passive"))
      (node (ref "D18") (pin "6") (pinfunction "OUT_6") (pintype "passive"))
      (node (ref "IC1") (pin "3") (pinfunction "+IN_3") (pintype "input"))
      (node (ref "IC2") (pin "3") (pinfunction "+IN_3") (pintype "input"))
      (node (ref "IC5") (pin "7") (pinfunction "V+_7") (pintype "power_in"))
      (node (ref "IC6") (pin "4") (pinfunction "V-_4") (pintype "power_in"))
      (node (ref "LED13") (pin "C") (pinfunction "C_C") (pintype "passive"))
      (node (ref "LED14") (pin "A") (pinfunction "A_A") (pintype "passive"))
      (node (ref "LED17") (pin "C") (pinfunction "C_C") (pintype "passive"))
      (node (ref "LED18") (pin "A") (pinfunction "A_A") (pintype "passive"))
      (node (ref "PAD3") (pin "P$1") (pinfunction "P$1_P$1") (pintype "bidirectional"))
      (node (ref "PAD4") (pin "P$1") (pinfunction "P$1_P$1") (pintype "bidirectional"))
      (node (ref "Q100") (pin "1") (pinfunction "S_1") (pintype "passive"))
      (node (ref "Q100") (pin "2") (pinfunction "S_2") (pintype "passive"))
      (node (ref "Q100") (pin "3") (pinfunction "S_3") (pintype "passive"))
      (node (ref "Q105") (pin "5") (pinfunction "D_5") (pintype "passive"))
      (node (ref "Q105") (pin "6") (pinfunction "D_6") (pintype "passive"))
      (node (ref "Q105") (pin "7") (pinfunction "D_7") (pintype "passive"))
      (node (ref "Q105") (pin "8") (pinfunction "D_8") (pintype "passive"))
      (node (ref "Q105") (pin "TH") (pinfunction "D_TH") (pintype "passive"))
      (node (ref "Q106") (pin "5") (pinfunction "D_5") (pintype "passive"))
      (node (ref "Q106") (pin "6") (pinfunction "D_6") (pintype "passive"))
      (node (ref "Q106") (pin "7") (pinfunction "D_7") (pintype "passive"))
      (node (ref "Q106") (pin "8") (pinfunction "D_8") (pintype "passive"))
      (node (ref "Q106") (pin "TH") (pinfunction "D_TH") (pintype "passive"))
      (node (ref "Q85") (pin "C") (pinfunction "C_C") (pintype "passive"))
      (node (ref "Q86") (pin "C") (pinfunction "C_C") (pintype "passive"))
      (node (ref "Q99") (pin "1") (pinfunction "S_1") (pintype "passive"))
      (node (ref "Q99") (pin "2") (pinfunction "S_2") (pintype "passive"))
      (node (ref "Q99") (pin "3") (pinfunction "S_3") (pintype "passive"))
      (node (ref "R107") (pin "2") (pinfunction "2_2") (pintype "passive"))
      (node (ref "R108") (pin "1") (pinfunction "1_1") (pintype "passive"))
      (node (ref "R11") (pin "1") (pinfunction "1_1") (pintype "passive"))
      (node (ref "R111") (pin "1") (pinfunction "1_1") (pintype "passive"))
      (node (ref "R117") (pin "2") (pinfunction "2_2") (pintype "passive"))
      (node (ref "R118") (pin "1") (pinfunction "1_1") (pintype "passive"))
      (node (ref "R128") (pin "1") (pinfunction "1_1") (pintype "passive"))
      (node (ref "R129") (pin "2") (pinfunction "2_2") (pintype "passive"))
      (node (ref "R134") (pin "1") (pinfunction "1_1") (pintype "passive"))
      (node (ref "R135") (pin "1") (pinfunction "1_1") (pintype "passive"))
      (node (ref "R137") (pin "1") (pinfunction "1_1") (pintype "passive"))
      (node (ref "R15") (pin "1") (pinfunction "1_1") (pintype "passive"))
      (node (ref "R16") (pin "2") (pinfunction "2_2") (pintype "passive"))
      (node (ref "R20") (pin "1") (pinfunction "1_1") (pintype "passive"))
      (node (ref "R3") (pin "1") (pinfunction "1_1") (pintype "passive"))
      (node (ref "R4") (pin "2") (pinfunction "2_2") (pintype "passive"))
      (node (ref "R52") (pin "1") (pinfunction "1_1") (pintype "passive"))
      (node (ref "R63") (pin "1") (pinfunction "1_1") (pintype "passive"))
      (node (ref "R75") (pin "2") (pinfunction "2_2") (pintype "passive"))
      (node (ref "R76") (pin "1") (pinfunction "1_1") (pintype "passive"))
      (node (ref "R79") (pin "1") (pinfunction "1_1") (pintype "passive"))
      (node (ref "R84") (pin "1") (pinfunction "1_1") (pintype "passive"))
      (node (ref "R95") (pin "1") (pinfunction "1_1") (pintype "passive"))
      (node (ref "U$2") (pin "7") (pinfunction "5_OUTN_7") (pintype "bidirectional"))
      (node (ref "U$2") (pin "EXP") (pinfunction "5_OUTN_EXP") (pintype "bidirectional"))
      (node (ref "U$4") (pin "9") (pinfunction "6_OUTP_9") (pintype "bidirectional"))
      (node (ref "U$5") (pin "11") (pinfunction "GND_11") (pintype "bidirectional"))
      (node (ref "U$5") (pin "12") (pinfunction "GND_12") (pintype "bidirectional"))
      (node (ref "U$5") (pin "13") (pinfunction "GND_13") (pintype "bidirectional"))
      (node (ref "U$5") (pin "14") (pinfunction "GND_14") (pintype "bidirectional"))
      (node (ref "U$5") (pin "15") (pinfunction "GND_15") (pintype "bidirectional"))
      (node (ref "U$5") (pin "4") (pinfunction "GND_4") (pintype "bidirectional"))
      (node (ref "X1") (pin "2") (pinfunction "S_2") (pintype "passive"))
    )
    (net (code "10") (name "IN+") (class "Default")
      (node (ref "Q1") (pin "4") (pinfunction "G_4") (pintype "passive"))
      (node (ref "Q4") (pin "4") (pinfunction "G_4") (pintype "passive"))
      (node (ref "R134") (pin "2") (pinfunction "2_2") (pintype "passive"))
      (node (ref "X1") (pin "3") (pinfunction "S_3") (pintype "passive"))
    )
    (net (code "11") (name "IN-") (class "Default")
      (node (ref "Q1") (pin "1") (pinfunction "G_1") (pintype "passive"))
      (node (ref "Q4") (pin "1") (pinfunction "G_1") (pintype "passive"))
      (node (ref "R135") (pin "2") (pinfunction "2_2") (pintype "passive"))
      (node (ref "X1") (pin "1") (pinfunction "S_1") (pintype "passive"))
    )
    (net (code "12") (name "Net-(C1-Pad2)") (class "Default")
      (node (ref "C1") (pin "2") (pinfunction "2_2") (pintype "passive"))
      (node (ref "R133") (pin "1") (pinfunction "1_1") (pintype "passive"))
    )
    (net (code "13") (name "Net-(C17-Pad1)") (class "Default")
      (node (ref "C17") (pin "1") (pinfunction "1_1") (pintype "passive"))
      (node (ref "Q26") (pin "B") (pinfunction "B_B") (pintype "passive"))
      (node (ref "Q27") (pin "B") (pinfunction "B_B") (pintype "passive"))
      (node (ref "R51") (pin "1") (pinfunction "1_1") (pintype "passive"))
      (node (ref "R52") (pin "2") (pinfunction "2_2") (pintype "passive"))
    )
    (net (code "14") (name "Net-(C18-Pad1)") (class "Default")
      (node (ref "C18") (pin "1") (pinfunction "1_1") (pintype "passive"))
      (node (ref "C19") (pin "2") (pinfunction "2_2") (pintype "passive"))
      (node (ref "Q39") (pin "C") (pinfunction "C_C") (pintype "passive"))
      (node (ref "Q43") (pin "C") (pinfunction "C_C") (pintype "passive"))
      (node (ref "Q45") (pin "C") (pinfunction "C_C") (pintype "passive"))
      (node (ref "Q46") (pin "B") (pinfunction "B_B") (pintype "passive"))
      (node (ref "R73") (pin "2") (pinfunction "2_2") (pintype "passive"))
      (node (ref "R75") (pin "1") (pinfunction "1_1") (pintype "passive"))
    )
    (net (code "15") (name "Net-(C27-Pad1)") (class "Default")
      (node (ref "C27") (pin "1") (pinfunction "1_1") (pintype "passive"))
      (node (ref "Q53") (pin "B") (pinfunction "B_B") (pintype "passive"))
      (node (ref "Q54") (pin "B") (pinfunction "B_B") (pintype "passive"))
      (node (ref "R83") (pin "1") (pinfunction "1_1") (pintype "passive"))
      (node (ref "R84") (pin "2") (pinfunction "2_2") (pintype "passive"))
    )
    (net (code "16") (name "Net-(C28-Pad1)") (class "Default")
      (node (ref "C28") (pin "1") (pinfunction "1_1") (pintype "passive"))
      (node (ref "C29") (pin "2") (pinfunction "2_2") (pintype "passive"))
      (node (ref "Q66") (pin "C") (pinfunction "C_C") (pintype "passive"))
      (node (ref "Q70") (pin "C") (pinfunction "C_C") (pintype "passive"))
      (node (ref "Q72") (pin "C") (pinfunction "C_C") (pintype "passive"))
      (node (ref "Q73") (pin "B") (pinfunction "B_B") (pintype "passive"))
      (node (ref "R105") (pin "2") (pinfunction "2_2") (pintype "passive"))
      (node (ref "R107") (pin "1") (pinfunction "1_1") (pintype "passive"))
    )
    (net (code "17") (name "Net-(C40-Pad1)") (class "Default")
      (node (ref "C40") (pin "1") (pinfunction "1_1") (pintype "passive"))
      (node (ref "C43") (pin "1") (pinfunction "1_1") (pintype "passive"))
      (node (ref "D13") (pin "C") (pinfunction "C_C") (pintype "passive"))
      (node (ref "Q83") (pin "C") (pinfunction "C_C") (pintype "passive"))
      (node (ref "Q87") (pin "B") (pinfunction "B_B") (pintype "passive"))
    )
    (net (code "18") (name "Net-(C40-Pad2)") (class "Default")
      (node (ref "C40") (pin "2") (pinfunction "2_2") (pintype "passive"))
      (node (ref "C43") (pin "2") (pinfunction "2_2") (pintype "passive"))
      (node (ref "D13") (pin "A") (pinfunction "A_A") (pintype "passive"))
      (node (ref "R120") (pin "1") (pinfunction "1_1") (pintype "passive"))
    )
    (net (code "19") (name "Net-(C41-Pad1)") (class "Default")
      (node (ref "C41") (pin "1") (pinfunction "1_1") (pintype "passive"))
      (node (ref "C44") (pin "1") (pinfunction "1_1") (pintype "passive"))
      (node (ref "D14") (pin "C") (pinfunction "C_C") (pintype "passive"))
      (node (ref "R121") (pin "2") (pinfunction "2_2") (pintype "passive"))
    )
    (net (code "20") (name "Net-(C41-Pad2)") (class "Default")
      (node (ref "C41") (pin "2") (pinfunction "2_2") (pintype "passive"))
      (node (ref "C44") (pin "2") (pinfunction "2_2") (pintype "passive"))
      (node (ref "D14") (pin "A") (pinfunction "A_A") (pintype "passive"))
      (node (ref "Q84") (pin "C") (pinfunction "C_C") (pintype "passive"))
      (node (ref "Q88") (pin "B") (pinfunction "B_B") (pintype "passive"))
    )
    (net (code "21") (name "Net-(D1-PadC)") (class "Default")
      (node (ref "D1") (pin "C") (pinfunction "C_C") (pintype "passive"))
      (node (ref "D2") (pin "A") (pinfunction "A_A") (pintype "passive"))
    )
    (net (code "22") (name "Net-(D2-PadC)") (class "Default")
      (node (ref "D2") (pin "C") (pinfunction "C_C") (pintype "passive"))
      (node (ref "Q25") (pin "B") (pinfunction "B_B") (pintype "passive"))
      (node (ref "R53") (pin "2") (pinfunction "2_2") (pintype "passive"))
    )
    (net (code "23") (name "Net-(D3-PadA)") (class "Default")
      (node (ref "D3") (pin "A") (pinfunction "A_A") (pintype "passive"))
      (node (ref "Q28") (pin "B") (pinfunction "B_B") (pintype "passive"))
      (node (ref "R53") (pin "1") (pinfunction "1_1") (pintype "passive"))
    )
    (net (code "24") (name "Net-(D3-PadC)") (class "Default")
      (node (ref "D3") (pin "C") (pinfunction "C_C") (pintype "passive"))
      (node (ref "D4") (pin "A") (pinfunction "A_A") (pintype "passive"))
    )
    (net (code "25") (name "Net-(D5-PadA)") (class "Default")
      (node (ref "D5") (pin "A") (pinfunction "A_A") (pintype "passive"))
      (node (ref "Q25") (pin "C") (pinfunction "C_C") (pintype "passive"))
      (node (ref "Q29") (pin "B") (pinfunction "B_B") (pintype "passive"))
    )
    (net (code "26") (name "Net-(D5-PadC)") (class "Default")
      (node (ref "D5") (pin "C") (pinfunction "C_C") (pintype "passive"))
      (node (ref "Q30") (pin "B") (pinfunction "B_B") (pintype "passive"))
      (node (ref "R55") (pin "2") (pinfunction "2_2") (pintype "passive"))
    )
    (net (code "27") (name "Net-(D6-PadA)") (class "Default")
      (node (ref "D6") (pin "A") (pinfunction "A_A") (pintype "passive"))
      (node (ref "Q31") (pin "B") (pinfunction "B_B") (pintype "passive"))
      (node (ref "R56") (pin "1") (pinfunction "1_1") (pintype "passive"))
    )
    (net (code "28") (name "Net-(D6-PadC)") (class "Default")
      (node (ref "D6") (pin "C") (pinfunction "C_C") (pintype "passive"))
      (node (ref "Q28") (pin "C") (pinfunction "C_C") (pintype "passive"))
      (node (ref "Q32") (pin "B") (pinfunction "B_B") (pintype "passive"))
    )
    (net (code "29") (name "Net-(D7-PadC)") (class "Default")
      (node (ref "D7") (pin "C") (pinfunction "C_C") (pintype "passive"))
      (node (ref "D8") (pin "A") (pinfunction "A_A") (pintype "passive"))
    )
    (net (code "30") (name "Net-(D8-PadC)") (class "Default")
      (node (ref "D8") (pin "C") (pinfunction "C_C") (pintype "passive"))
      (node (ref "Q52") (pin "B") (pinfunction "B_B") (pintype "passive"))
      (node (ref "R85") (pin "2") (pinfunction "2_2") (pintype "passive"))
    )
    (net (code "31") (name "Net-(D9-PadA)") (class "Default")
      (node (ref "D9") (pin "A") (pinfunction "A_A") (pintype "passive"))
      (node (ref "Q55") (pin "B") (pinfunction "B_B") (pintype "passive"))
      (node (ref "R85") (pin "1") (pinfunction "1_1") (pintype "passive"))
    )
    (net (code "32") (name "Net-(D10-PadA)") (class "Default")
      (node (ref "D10") (pin "A") (pinfunction "A_A") (pintype "passive"))
      (node (ref "D9") (pin "C") (pinfunction "C_C") (pintype "passive"))
    )
    (net (code "33") (name "Net-(D11-PadA)") (class "Default")
      (node (ref "D11") (pin "A") (pinfunction "A_A") (pintype "passive"))
      (node (ref "Q52") (pin "C") (pinfunction "C_C") (pintype "passive"))
      (node (ref "Q56") (pin "B") (pinfunction "B_B") (pintype "passive"))
    )
    (net (code "34") (name "Net-(D11-PadC)") (class "Default")
      (node (ref "D11") (pin "C") (pinfunction "C_C") (pintype "passive"))
      (node (ref "Q57") (pin "B") (pinfunction "B_B") (pintype "passive"))
      (node (ref "R87") (pin "2") (pinfunction "2_2") (pintype "passive"))
    )
    (net (code "35") (name "Net-(D12-PadA)") (class "Default")
      (node (ref "D12") (pin "A") (pinfunction "A_A") (pintype "passive"))
      (node (ref "Q58") (pin "B") (pinfunction "B_B") (pintype "passive"))
      (node (ref "R88") (pin "1") (pinfunction "1_1") (pintype "passive"))
    )
    (net (code "36") (name "Net-(D12-PadC)") (class "Default")
      (node (ref "D12") (pin "C") (pinfunction "C_C") (pintype "passive"))
      (node (ref "Q55") (pin "C") (pinfunction "C_C") (pintype "passive"))
      (node (ref "Q59") (pin "B") (pinfunction "B_B") (pintype "passive"))
    )
    (net (code "37") (name "Net-(D17-OUT)") (class "Default")
      (node (ref "C47") (pin "1") (pinfunction "1_1") (pintype "passive"))
      (node (ref "C49") (pin "1") (pinfunction "1_1") (pintype "passive"))
      (node (ref "D17") (pin "6") (pinfunction "OUT_6") (pintype "passive"))
      (node (ref "D19") (pin "C") (pinfunction "C_C") (pintype "passive"))
      (node (ref "D20") (pin "A") (pinfunction "A_A") (pintype "passive"))
      (node (ref "IC6") (pin "3") (pinfunction "+IN_3") (pintype "input"))
      (node (ref "Q91") (pin "G") (pinfunction "G_G") (pintype "passive"))
      (node (ref "R125") (pin "1") (pinfunction "1_1") (pintype "passive"))
    )
    (net (code "38") (name "Net-(D18-GND)") (class "Default")
      (node (ref "C48") (pin "2") (pinfunction "2_2") (pintype "passive"))
      (node (ref "C50") (pin "2") (pinfunction "2_2") (pintype "passive"))
      (node (ref "D18") (pin "4") (pinfunction "GND_4") (pintype "passive"))
      (node (ref "D21") (pin "A") (pinfunction "A_A") (pintype "passive"))
      (node (ref "D22") (pin "C") (pinfunction "C_C") (pintype "passive"))
      (node (ref "IC5") (pin "3") (pinfunction "+IN_3") (pintype "input"))
      (node (ref "Q92") (pin "D") (pinfunction "D_D") (pintype "passive"))
    )
    (net (code "39") (name "Net-(IC1--IN)") (class "Default")
      (node (ref "C13") (pin "2") (pinfunction "2_2") (pintype "passive"))
      (node (ref "IC1") (pin "2") (pinfunction "-IN_2") (pintype "input"))
      (node (ref "R29") (pin "2") (pinfunction "2_2") (pintype "passive"))
    )
    (net (code "40") (name "Net-(IC1-CMP2)") (class "Default")
      (node (ref "C13") (pin "1") (pinfunction "1_1") (pintype "passive"))
      (node (ref "IC1") (pin "6") (pinfunction "OUT_6") (pintype "output"))
      (node (ref "IC1") (pin "8") (pinfunction "CMP2_8") (pintype "passive"))
      (node (ref "R21") (pin "1") (pinfunction "1_1") (pintype "passive"))
    )
    (net (code "41") (name "Net-(IC2--IN)") (class "Default")
      (node (ref "C16") (pin "2") (pinfunction "2_2") (pintype "passive"))
      (node (ref "IC2") (pin "2") (pinfunction "-IN_2") (pintype "input"))
      (node (ref "R44") (pin "2") (pinfunction "2_2") (pintype "passive"))
    )
    (net (code "42") (name "Net-(IC2-CMP2)") (class "Default")
      (node (ref "C16") (pin "1") (pinfunction "1_1") (pintype "passive"))
      (node (ref "IC2") (pin "6") (pinfunction "OUT_6") (pintype "output"))
      (node (ref "IC2") (pin "8") (pinfunction "CMP2_8") (pintype "passive"))
      (node (ref "R36") (pin "1") (pinfunction "1_1") (pintype "passive"))
    )
    (net (code "43") (name "Net-(IC3-+IN)") (class "Default")
      (node (ref "C22") (pin "2") (pinfunction "2_2") (pintype "passive"))
      (node (ref "IC3") (pin "3") (pinfunction "+IN_3") (pintype "input"))
      (node (ref "R82") (pin "2") (pinfunction "2_2") (pintype "passive"))
    )
    (net (code "44") (name "Net-(IC3--IN)") (class "Default")
      (node (ref "C21") (pin "2") (pinfunction "2_2") (pintype "passive"))
      (node (ref "IC3") (pin "2") (pinfunction "-IN_2") (pintype "input"))
      (node (ref "R79") (pin "2") (pinfunction "2_2") (pintype "passive"))
    )
    (net (code "45") (name "Net-(IC3-OUT)") (class "Default")
      (node (ref "C21") (pin "1") (pinfunction "1_1") (pintype "passive"))
      (node (ref "IC3") (pin "6") (pinfunction "OUT_6") (pintype "output"))
      (node (ref "R68") (pin "1") (pinfunction "1_1") (pintype "passive"))
      (node (ref "R69") (pin "2") (pinfunction "2_2") (pintype "passive"))
    )
    (net (code "46") (name "Net-(IC4-+IN)") (class "Default")
      (node (ref "C32") (pin "2") (pinfunction "2_2") (pintype "passive"))
      (node (ref "IC4") (pin "3") (pinfunction "+IN_3") (pintype "input"))
      (node (ref "R114") (pin "2") (pinfunction "2_2") (pintype "passive"))
    )
    (net (code "47") (name "Net-(IC4--IN)") (class "Default")
      (node (ref "C31") (pin "2") (pinfunction "2_2") (pintype "passive"))
      (node (ref "IC4") (pin "2") (pinfunction "-IN_2") (pintype "input"))
      (node (ref "R111") (pin "2") (pinfunction "2_2") (pintype "passive"))
    )
    (net (code "48") (name "Net-(IC4-OUT)") (class "Default")
      (node (ref "C31") (pin "1") (pinfunction "1_1") (pintype "passive"))
      (node (ref "IC4") (pin "6") (pinfunction "OUT_6") (pintype "output"))
      (node (ref "R100") (pin "1") (pinfunction "1_1") (pintype "passive"))
      (node (ref "R101") (pin "2") (pinfunction "2_2") (pintype "passive"))
    )
    (net (code "49") (name "Net-(IC5--IN)") (class "Default")
      (node (ref "C52") (pin "2") (pinfunction "2_2") (pintype "passive"))
      (node (ref "C54") (pin "1") (pinfunction "1_1") (pintype "passive"))
      (node (ref "D21") (pin "C") (pinfunction "C_C") (pintype "passive"))
      (node (ref "D22") (pin "A") (pinfunction "A_A") (pintype "passive"))
      (node (ref "IC5") (pin "2") (pinfunction "-IN_2") (pintype "input"))
      (node (ref "R129") (pin "1") (pinfunction "1_1") (pintype "passive"))
      (node (ref "R130") (pin "2") (pinfunction "2_2") (pintype "passive"))
    )
    (net (code "50") (name "Net-(IC5-OUT)") (class "Default")
      (node (ref "C52") (pin "1") (pinfunction "1_1") (pintype "passive"))
      (node (ref "IC5") (pin "6") (pinfunction "OUT_6") (pintype "output"))
      (node (ref "R124") (pin "1") (pinfunction "1_1") (pintype "passive"))
    )
    (net (code "51") (name "Net-(IC6--IN)") (class "Default")
      (node (ref "C51") (pin "2") (pinfunction "2_2") (pintype "passive"))
      (node (ref "C53") (pin "2") (pinfunction "2_2") (pintype "passive"))
      (node (ref "D19") (pin "A") (pinfunction "A_A") (pintype "passive"))
      (node (ref "D20") (pin "C") (pinfunction "C_C") (pintype "passive"))
      (node (ref "IC6") (pin "2") (pinfunction "-IN_2") (pintype "input"))
      (node (ref "R127") (pin "1") (pinfunction "1_1") (pintype "passive"))
      (node (ref "R128") (pin "2") (pinfunction "2_2") (pintype "passive"))
    )
    (net (code "52") (name "Net-(IC6-OUT)") (class "Default")
      (node (ref "C51") (pin "1") (pinfunction "1_1") (pintype "passive"))
      (node (ref "IC6") (pin "6") (pinfunction "OUT_6") (pintype "output"))
      (node (ref "R123") (pin "1") (pinfunction "1_1") (pintype "passive"))
    )
    (net (code "53") (name "Net-(LED1-PadC)") (class "Default")
      (node (ref "LED1") (pin "C") (pinfunction "C_C") (pintype "passive"))
      (node (ref "Q2") (pin "B") (pinfunction "B_B") (pintype "passive"))
      (node (ref "R3") (pin "2") (pinfunction "2_2") (pintype "passive"))
    )
    (net (code "54") (name "Net-(LED2-PadA)") (class "Default")
      (node (ref "LED2") (pin "A") (pinfunction "A_A") (pintype "passive"))
      (node (ref "Q3") (pin "B") (pinfunction "B_B") (pintype "passive"))
      (node (ref "R4") (pin "1") (pinfunction "1_1") (pintype "passive"))
    )
    (net (code "55") (name "Net-(LED5-PadC)") (class "Default")
      (node (ref "LED5") (pin "C") (pinfunction "C_C") (pintype "passive"))
      (node (ref "Q11") (pin "B") (pinfunction "B_B") (pintype "passive"))
      (node (ref "R22") (pin "2") (pinfunction "2_2") (pintype "passive"))
    )
    (net (code "56") (name "Net-(LED6-PadA)") (class "Default")
      (node (ref "LED6") (pin "A") (pinfunction "A_A") (pintype "passive"))
      (node (ref "Q12") (pin "B") (pinfunction "B_B") (pintype "passive"))
      (node (ref "R22") (pin "1") (pinfunction "1_1") (pintype "passive"))
    )
    (net (code "57") (name "Net-(LED7-PadC)") (class "Default")
      (node (ref "LED7") (pin "C") (pinfunction "C_C") (pintype "passive"))
      (node (ref "Q19") (pin "B") (pinfunction "B_B") (pintype "passive"))
      (node (ref "R37") (pin "2") (pinfunction "2_2") (pintype "passive"))
    )
    (net (code "58") (name "Net-(LED8-PadA)") (class "Default")
      (node (ref "LED8") (pin "A") (pinfunction "A_A") (pintype "passive"))
      (node (ref "Q20") (pin "B") (pinfunction "B_B") (pintype "passive"))
      (node (ref "R37") (pin "1") (pinfunction "1_1") (pintype "passive"))
    )
    (net (code "59") (name "Net-(LED9-PadA)") (class "Default")
      (node (ref "LED9") (pin "A") (pinfunction "A_A") (pintype "passive"))
      (node (ref "Q35") (pin "E") (pinfunction "E_E") (pintype "passive"))
      (node (ref "R62") (pin "1") (pinfunction "1_1") (pintype "passive"))
    )
    (net (code "60") (name "Net-(LED9-PadC)") (class "Default")
      (node (ref "LED9") (pin "C") (pinfunction "C_C") (pintype "passive"))
      (node (ref "Q39") (pin "B") (pinfunction "B_B") (pintype "passive"))
      (node (ref "R65") (pin "2") (pinfunction "2_2") (pintype "passive"))
    )
    (net (code "61") (name "Net-(LED10-PadA)") (class "Default")
      (node (ref "LED10") (pin "A") (pinfunction "A_A") (pintype "passive"))
      (node (ref "Q40") (pin "B") (pinfunction "B_B") (pintype "passive"))
      (node (ref "R65") (pin "1") (pinfunction "1_1") (pintype "passive"))
    )
    (net (code "62") (name "Net-(LED10-PadC)") (class "Default")
      (node (ref "LED10") (pin "C") (pinfunction "C_C") (pintype "passive"))
      (node (ref "Q38") (pin "E") (pinfunction "E_E") (pintype "passive"))
      (node (ref "R64") (pin "2") (pinfunction "2_2") (pintype "passive"))
    )
    (net (code "63") (name "Net-(LED11-PadA)") (class "Default")
      (node (ref "LED11") (pin "A") (pinfunction "A_A") (pintype "passive"))
      (node (ref "Q62") (pin "E") (pinfunction "E_E") (pintype "passive"))
      (node (ref "R94") (pin "1") (pinfunction "1_1") (pintype "passive"))
    )
    (net (code "64") (name "Net-(LED11-PadC)") (class "Default")
      (node (ref "LED11") (pin "C") (pinfunction "C_C") (pintype "passive"))
      (node (ref "Q66") (pin "B") (pinfunction "B_B") (pintype "passive"))
      (node (ref "R97") (pin "2") (pinfunction "2_2") (pintype "passive"))
    )
    (net (code "65") (name "Net-(LED12-PadA)") (class "Default")
      (node (ref "LED12") (pin "A") (pinfunction "A_A") (pintype "passive"))
      (node (ref "Q67") (pin "B") (pinfunction "B_B") (pintype "passive"))
      (node (ref "R97") (pin "1") (pinfunction "1_1") (pintype "passive"))
    )
    (net (code "66") (name "Net-(LED12-PadC)") (class "Default")
      (node (ref "LED12") (pin "C") (pinfunction "C_C") (pintype "passive"))
      (node (ref "Q65") (pin "E") (pinfunction "E_E") (pintype "passive"))
      (node (ref "R96") (pin "2") (pinfunction "2_2") (pintype "passive"))
    )
    (net (code "67") (name "Net-(LED13-PadA)") (class "Default")
      (node (ref "LED13") (pin "A") (pinfunction "A_A") (pintype "passive"))
      (node (ref "Q79") (pin "B") (pinfunction "B_B") (pintype "passive"))
      (node (ref "R115") (pin "2") (pinfunction "2_2") (pintype "passive"))
    )
    (net (code "68") (name "Net-(LED14-PadC)") (class "Default")
      (node (ref "LED14") (pin "C") (pinfunction "C_C") (pintype "passive"))
      (node (ref "Q80") (pin "B") (pinfunction "B_B") (pintype "passive"))
      (node (ref "R116") (pin "1") (pinfunction "1_1") (pintype "passive"))
    )
    (net (code "69") (name "Net-(LED15-PadC)") (class "Default")
      (node (ref "LED15") (pin "C") (pinfunction "C_C") (pintype "passive"))
      (node (ref "Q81") (pin "E") (pinfunction "E_E") (pintype "passive"))
    )
    (net (code "70") (name "Net-(LED16-PadA)") (class "Default")
      (node (ref "LED16") (pin "A") (pinfunction "A_A") (pintype "passive"))
      (node (ref "Q82") (pin "E") (pinfunction "E_E") (pintype "passive"))
    )
    (net (code "71") (name "Net-(LED17-PadA)") (class "Default")
      (node (ref "LED17") (pin "A") (pinfunction "A_A") (pintype "passive"))
      (node (ref "R131") (pin "1") (pinfunction "1_1") (pintype "passive"))
    )
    (net (code "72") (name "Net-(LED18-PadC)") (class "Default")
      (node (ref "LED18") (pin "C") (pinfunction "C_C") (pintype "passive"))
      (node (ref "R132") (pin "2") (pinfunction "2_2") (pintype "passive"))
    )
    (net (code "73") (name "Net-(Q1A-D)") (class "Default")
      (node (ref "Q1") (pin "2") (pinfunction "D_2") (pintype "passive"))
      (node (ref "Q6") (pin "5") (pinfunction "E_5") (pintype "passive"))
      (node (ref "Q7") (pin "6") (pinfunction "C_6") (pintype "passive"))
    )
    (net (code "74") (name "Net-(Q1A-S)") (class "Default")
      (node (ref "Q1") (pin "3") (pinfunction "S_3") (pintype "passive"))
      (node (ref "R6") (pin "1") (pinfunction "1_1") (pintype "passive"))
    )
    (net (code "75") (name "Net-(Q1B-D)") (class "Default")
      (node (ref "Q1") (pin "5") (pinfunction "D_5") (pintype "passive"))
      (node (ref "Q6") (pin "2") (pinfunction "E_2") (pintype "passive"))
      (node (ref "Q7") (pin "4") (pinfunction "C_4") (pintype "passive"))
    )
    (net (code "76") (name "Net-(Q1B-S)") (class "Default")
      (node (ref "Q1") (pin "6") (pinfunction "S_6") (pintype "passive"))
      (node (ref "R8") (pin "1") (pinfunction "1_1") (pintype "passive"))
    )
    (net (code "77") (name "Net-(Q2-PadC)") (class "Default")
      (node (ref "Q2") (pin "C") (pinfunction "C_C") (pintype "passive"))
      (node (ref "R6") (pin "2") (pinfunction "2_2") (pintype "passive"))
      (node (ref "R8") (pin "2") (pinfunction "2_2") (pintype "passive"))
    )
    (net (code "78") (name "Net-(Q2-PadE)") (class "Default")
      (node (ref "Q2") (pin "E") (pinfunction "E_E") (pintype "passive"))
      (node (ref "R5") (pin "1") (pinfunction "1_1") (pintype "passive"))
    )
    (net (code "79") (name "Net-(Q3-PadC)") (class "Default")
      (node (ref "Q3") (pin "C") (pinfunction "C_C") (pintype "passive"))
      (node (ref "R10") (pin "1") (pinfunction "1_1") (pintype "passive"))
      (node (ref "R9") (pin "1") (pinfunction "1_1") (pintype "passive"))
    )
    (net (code "80") (name "Net-(Q3-PadE)") (class "Default")
      (node (ref "Q3") (pin "E") (pinfunction "E_E") (pintype "passive"))
      (node (ref "R7") (pin "2") (pinfunction "2_2") (pintype "passive"))
    )
    (net (code "81") (name "Net-(Q4A-D)") (class "Default")
      (node (ref "Q4") (pin "2") (pinfunction "D_2") (pintype "passive"))
      (node (ref "Q5") (pin "5") (pinfunction "E_5") (pintype "passive"))
      (node (ref "Q8") (pin "4") (pinfunction "C_4") (pintype "passive"))
    )
    (net (code "82") (name "Net-(Q4A-S)") (class "Default")
      (node (ref "Q4") (pin "3") (pinfunction "S_3") (pintype "passive"))
      (node (ref "R9") (pin "2") (pinfunction "2_2") (pintype "passive"))
    )
    (net (code "83") (name "Net-(Q4B-D)") (class "Default")
      (node (ref "Q4") (pin "5") (pinfunction "D_5") (pintype "passive"))
      (node (ref "Q5") (pin "2") (pinfunction "E_2") (pintype "passive"))
      (node (ref "Q8") (pin "6") (pinfunction "C_6") (pintype "passive"))
    )
    (net (code "84") (name "Net-(Q4B-S)") (class "Default")
      (node (ref "Q4") (pin "6") (pinfunction "S_6") (pintype "passive"))
      (node (ref "R10") (pin "2") (pinfunction "2_2") (pintype "passive"))
    )
    (net (code "85") (name "Net-(Q5A-B)") (class "Default")
      (node (ref "Q5") (pin "1") (pinfunction "B_1") (pintype "passive"))
      (node (ref "Q5") (pin "3") (pinfunction "B_3") (pintype "passive"))
      (node (ref "R14") (pin "1") (pinfunction "1_1") (pintype "passive"))
      (node (ref "R15") (pin "2") (pinfunction "2_2") (pintype "passive"))
    )
    (net (code "86") (name "Net-(Q6A-B)") (class "Default")
      (node (ref "Q6") (pin "1") (pinfunction "B_1") (pintype "passive"))
      (node (ref "Q6") (pin "3") (pinfunction "B_3") (pintype "passive"))
      (node (ref "R16") (pin "1") (pinfunction "1_1") (pintype "passive"))
      (node (ref "R17") (pin "2") (pinfunction "2_2") (pintype "passive"))
    )
    (net (code "87") (name "Net-(Q7A-B)") (class "Default")
      (node (ref "LED4") (pin "A") (pinfunction "A_A") (pintype "passive"))
      (node (ref "Q7") (pin "1") (pinfunction "B_1") (pintype "passive"))
      (node (ref "Q7") (pin "3") (pinfunction "B_3") (pintype "passive"))
      (node (ref "R17") (pin "1") (pinfunction "1_1") (pintype "passive"))
    )
    (net (code "88") (name "Net-(Q7A-E)") (class "Default")
      (node (ref "Q7") (pin "5") (pinfunction "E_5") (pintype "passive"))
      (node (ref "R13") (pin "2") (pinfunction "2_2") (pintype "passive"))
    )
    (net (code "89") (name "Net-(Q7B-E)") (class "Default")
      (node (ref "Q7") (pin "2") (pinfunction "E_2") (pintype "passive"))
      (node (ref "R19") (pin "2") (pinfunction "2_2") (pintype "passive"))
    )
    (net (code "90") (name "Net-(Q8A-B)") (class "Default")
      (node (ref "LED3") (pin "C") (pinfunction "C_C") (pintype "passive"))
      (node (ref "Q8") (pin "1") (pinfunction "B_1") (pintype "passive"))
      (node (ref "Q8") (pin "3") (pinfunction "B_3") (pintype "passive"))
      (node (ref "R14") (pin "2") (pinfunction "2_2") (pintype "passive"))
    )
    (net (code "91") (name "Net-(Q8A-E)") (class "Default")
      (node (ref "Q8") (pin "5") (pinfunction "E_5") (pintype "passive"))
      (node (ref "R18") (pin "1") (pinfunction "1_1") (pintype "passive"))
    )
    (net (code "92") (name "Net-(Q8B-E)") (class "Default")
      (node (ref "Q8") (pin "2") (pinfunction "E_2") (pintype "passive"))
      (node (ref "R12") (pin "1") (pinfunction "1_1") (pintype "passive"))
    )
    (net (code "93") (name "Net-(Q9-PadE)") (class "Default")
      (node (ref "Q9") (pin "E") (pinfunction "E_E") (pintype "passive"))
      (node (ref "R25") (pin "1") (pinfunction "1_1") (pintype "passive"))
    )
    (net (code "94") (name "Net-(Q10-PadE)") (class "Default")
      (node (ref "Q10") (pin "E") (pinfunction "E_E") (pintype "passive"))
      (node (ref "R24") (pin "2") (pinfunction "2_2") (pintype "passive"))
    )
    (net (code "95") (name "Net-(Q11-PadC)") (class "Default")
      (node (ref "Q11") (pin "C") (pinfunction "C_C") (pintype "passive"))
      (node (ref "R24") (pin "1") (pinfunction "1_1") (pintype "passive"))
      (node (ref "R27") (pin "2") (pinfunction "2_2") (pintype "passive"))
      (node (ref "R32") (pin "2") (pinfunction "2_2") (pintype "passive"))
    )
    (net (code "96") (name "Net-(Q11-PadE)") (class "Default")
      (node (ref "Q11") (pin "E") (pinfunction "E_E") (pintype "passive"))
      (node (ref "R23") (pin "1") (pinfunction "1_1") (pintype "passive"))
    )
    (net (code "97") (name "Net-(Q12-PadC)") (class "Default")
      (node (ref "Q12") (pin "C") (pinfunction "C_C") (pintype "passive"))
      (node (ref "R25") (pin "2") (pinfunction "2_2") (pintype "passive"))
      (node (ref "R28") (pin "1") (pinfunction "1_1") (pintype "passive"))
      (node (ref "R33") (pin "1") (pinfunction "1_1") (pintype "passive"))
    )
    (net (code "98") (name "Net-(Q12-PadE)") (class "Default")
      (node (ref "Q12") (pin "E") (pinfunction "E_E") (pintype "passive"))
      (node (ref "R26") (pin "2") (pinfunction "2_2") (pintype "passive"))
    )
    (net (code "99") (name "Net-(Q13-PadB)") (class "Default")
      (node (ref "Q13") (pin "B") (pinfunction "B_B") (pintype "passive"))
      (node (ref "R27") (pin "1") (pinfunction "1_1") (pintype "passive"))
    )
    (net (code "100") (name "Net-(Q13-PadE)") (class "Default")
      (node (ref "Q13") (pin "E") (pinfunction "E_E") (pintype "passive"))
      (node (ref "R30") (pin "2") (pinfunction "2_2") (pintype "passive"))
    )
    (net (code "101") (name "Net-(Q14-PadB)") (class "Default")
      (node (ref "Q14") (pin "B") (pinfunction "B_B") (pintype "passive"))
      (node (ref "R28") (pin "2") (pinfunction "2_2") (pintype "passive"))
    )
    (net (code "102") (name "Net-(Q14-PadE)") (class "Default")
      (node (ref "Q14") (pin "E") (pinfunction "E_E") (pintype "passive"))
      (node (ref "R31") (pin "1") (pinfunction "1_1") (pintype "passive"))
    )
    (net (code "103") (name "Net-(Q15-PadB)") (class "Default")
      (node (ref "Q15") (pin "B") (pinfunction "B_B") (pintype "passive"))
      (node (ref "R32") (pin "1") (pinfunction "1_1") (pintype "passive"))
    )
    (net (code "104") (name "Net-(Q15-PadE)") (class "Default")
      (node (ref "Q15") (pin "E") (pinfunction "E_E") (pintype "passive"))
      (node (ref "R34") (pin "2") (pinfunction "2_2") (pintype "passive"))
    )
    (net (code "105") (name "Net-(Q16-PadB)") (class "Default")
      (node (ref "Q16") (pin "B") (pinfunction "B_B") (pintype "passive"))
      (node (ref "R33") (pin "2") (pinfunction "2_2") (pintype "passive"))
    )
    (net (code "106") (name "Net-(Q16-PadE)") (class "Default")
      (node (ref "Q16") (pin "E") (pinfunction "E_E") (pintype "passive"))
      (node (ref "R35") (pin "1") (pinfunction "1_1") (pintype "passive"))
    )
    (net (code "107") (name "Net-(Q17-PadE)") (class "Default")
      (node (ref "Q17") (pin "E") (pinfunction "E_E") (pintype "passive"))
      (node (ref "R40") (pin "1") (pinfunction "1_1") (pintype "passive"))
    )
    (net (code "108") (name "Net-(Q18-PadE)") (class "Default")
      (node (ref "Q18") (pin "E") (pinfunction "E_E") (pintype "passive"))
      (node (ref "R39") (pin "2") (pinfunction "2_2") (pintype "passive"))
    )
    (net (code "109") (name "Net-(Q19-PadC)") (class "Default")
      (node (ref "Q19") (pin "C") (pinfunction "C_C") (pintype "passive"))
      (node (ref "R39") (pin "1") (pinfunction "1_1") (pintype "passive"))
      (node (ref "R42") (pin "2") (pinfunction "2_2") (pintype "passive"))
      (node (ref "R47") (pin "2") (pinfunction "2_2") (pintype "passive"))
    )
    (net (code "110") (name "Net-(Q19-PadE)") (class "Default")
      (node (ref "Q19") (pin "E") (pinfunction "E_E") (pintype "passive"))
      (node (ref "R38") (pin "1") (pinfunction "1_1") (pintype "passive"))
    )
    (net (code "111") (name "Net-(Q20-PadC)") (class "Default")
      (node (ref "Q20") (pin "C") (pinfunction "C_C") (pintype "passive"))
      (node (ref "R40") (pin "2") (pinfunction "2_2") (pintype "passive"))
      (node (ref "R43") (pin "1") (pinfunction "1_1") (pintype "passive"))
      (node (ref "R48") (pin "1") (pinfunction "1_1") (pintype "passive"))
    )
    (net (code "112") (name "Net-(Q20-PadE)") (class "Default")
      (node (ref "Q20") (pin "E") (pinfunction "E_E") (pintype "passive"))
      (node (ref "R41") (pin "2") (pinfunction "2_2") (pintype "passive"))
    )
    (net (code "113") (name "Net-(Q21-PadB)") (class "Default")
      (node (ref "Q21") (pin "B") (pinfunction "B_B") (pintype "passive"))
      (node (ref "R42") (pin "1") (pinfunction "1_1") (pintype "passive"))
    )
    (net (code "114") (name "Net-(Q21-PadE)") (class "Default")
      (node (ref "Q21") (pin "E") (pinfunction "E_E") (pintype "passive"))
      (node (ref "R45") (pin "2") (pinfunction "2_2") (pintype "passive"))
    )
    (net (code "115") (name "Net-(Q22-PadB)") (class "Default")
      (node (ref "Q22") (pin "B") (pinfunction "B_B") (pintype "passive"))
      (node (ref "R43") (pin "2") (pinfunction "2_2") (pintype "passive"))
    )
    (net (code "116") (name "Net-(Q22-PadE)") (class "Default")
      (node (ref "Q22") (pin "E") (pinfunction "E_E") (pintype "passive"))
      (node (ref "R46") (pin "1") (pinfunction "1_1") (pintype "passive"))
    )
    (net (code "117") (name "Net-(Q23-PadB)") (class "Default")
      (node (ref "Q23") (pin "B") (pinfunction "B_B") (pintype "passive"))
      (node (ref "R47") (pin "1") (pinfunction "1_1") (pintype "passive"))
    )
    (net (code "118") (name "Net-(Q23-PadE)") (class "Default")
      (node (ref "Q23") (pin "E") (pinfunction "E_E") (pintype "passive"))
      (node (ref "R49") (pin "2") (pinfunction "2_2") (pintype "passive"))
    )
    (net (code "119") (name "Net-(Q24-PadB)") (class "Default")
      (node (ref "Q24") (pin "B") (pinfunction "B_B") (pintype "passive"))
      (node (ref "R48") (pin "2") (pinfunction "2_2") (pintype "passive"))
    )
    (net (code "120") (name "Net-(Q24-PadE)") (class "Default")
      (node (ref "Q24") (pin "E") (pinfunction "E_E") (pintype "passive"))
      (node (ref "R50") (pin "1") (pinfunction "1_1") (pintype "passive"))
    )
    (net (code "121") (name "Net-(Q25-PadE)") (class "Default")
      (node (ref "Q25") (pin "E") (pinfunction "E_E") (pintype "passive"))
      (node (ref "R54") (pin "1") (pinfunction "1_1") (pintype "passive"))
    )
    (net (code "122") (name "Net-(Q26-PadC)") (class "Default")
      (node (ref "Q26") (pin "C") (pinfunction "C_C") (pintype "passive"))
      (node (ref "Q31") (pin "E") (pinfunction "E_E") (pintype "passive"))
      (node (ref "R60") (pin "1") (pinfunction "1_1") (pintype "passive"))
    )
    (net (code "123") (name "Net-(Q26-PadE)") (class "Default")
      (node (ref "Q26") (pin "E") (pinfunction "E_E") (pintype "passive"))
      (node (ref "R55") (pin "1") (pinfunction "1_1") (pintype "passive"))
    )
    (net (code "124") (name "Net-(Q27-PadC)") (class "Default")
      (node (ref "Q27") (pin "C") (pinfunction "C_C") (pintype "passive"))
      (node (ref "Q30") (pin "E") (pinfunction "E_E") (pintype "passive"))
      (node (ref "R59") (pin "2") (pinfunction "2_2") (pintype "passive"))
    )
    (net (code "125") (name "Net-(Q27-PadE)") (class "Default")
      (node (ref "Q27") (pin "E") (pinfunction "E_E") (pintype "passive"))
      (node (ref "R56") (pin "2") (pinfunction "2_2") (pintype "passive"))
    )
    (net (code "126") (name "Net-(Q28-PadE)") (class "Default")
      (node (ref "Q28") (pin "E") (pinfunction "E_E") (pintype "passive"))
      (node (ref "R57") (pin "2") (pinfunction "2_2") (pintype "passive"))
    )
    (net (code "127") (name "Net-(Q29-PadC)") (class "Default")
      (node (ref "Q29") (pin "C") (pinfunction "C_C") (pintype "passive"))
      (node (ref "Q33") (pin "C") (pinfunction "C_C") (pintype "passive"))
      (node (ref "Q36") (pin "B") (pinfunction "B_B") (pintype "passive"))
    )
    (net (code "128") (name "Net-(Q29-PadE)") (class "Default")
      (node (ref "Q29") (pin "E") (pinfunction "E_E") (pintype "passive"))
      (node (ref "Q30") (pin "C") (pinfunction "C_C") (pintype "passive"))
    )
    (net (code "129") (name "Net-(Q31-PadC)") (class "Default")
      (node (ref "Q31") (pin "C") (pinfunction "C_C") (pintype "passive"))
      (node (ref "Q32") (pin "E") (pinfunction "E_E") (pintype "passive"))
    )
    (net (code "130") (name "Net-(Q32-PadC)") (class "Default")
      (node (ref "Q32") (pin "C") (pinfunction "C_C") (pintype "passive"))
      (node (ref "Q34") (pin "C") (pinfunction "C_C") (pintype "passive"))
      (node (ref "Q37") (pin "B") (pinfunction "B_B") (pintype "passive"))
    )
    (net (code "131") (name "Net-(Q33-PadB)") (class "Default")
      (node (ref "Q33") (pin "B") (pinfunction "B_B") (pintype "passive"))
      (node (ref "Q35") (pin "B") (pinfunction "B_B") (pintype "passive"))
      (node (ref "Q35") (pin "C") (pinfunction "C_C") (pintype "passive"))
      (node (ref "Q36") (pin "E") (pinfunction "E_E") (pintype "passive"))
    )
    (net (code "132") (name "Net-(Q33-PadE)") (class "Default")
      (node (ref "Q33") (pin "E") (pinfunction "E_E") (pintype "passive"))
      (node (ref "R58") (pin "1") (pinfunction "1_1") (pintype "passive"))
    )
    (net (code "133") (name "Net-(Q34-PadB)") (class "Default")
      (node (ref "Q34") (pin "B") (pinfunction "B_B") (pintype "passive"))
      (node (ref "Q37") (pin "E") (pinfunction "E_E") (pintype "passive"))
      (node (ref "Q38") (pin "B") (pinfunction "B_B") (pintype "passive"))
      (node (ref "Q38") (pin "C") (pinfunction "C_C") (pintype "passive"))
    )
    (net (code "134") (name "Net-(Q34-PadE)") (class "Default")
      (node (ref "Q34") (pin "E") (pinfunction "E_E") (pintype "passive"))
      (node (ref "R61") (pin "2") (pinfunction "2_2") (pintype "passive"))
    )
    (net (code "135") (name "Net-(Q36-PadC)") (class "Default")
      (node (ref "Q36") (pin "C") (pinfunction "C_C") (pintype "passive"))
      (node (ref "Q39") (pin "E") (pinfunction "E_E") (pintype "passive"))
    )
    (net (code "136") (name "Net-(Q37-PadC)") (class "Default")
      (node (ref "Q37") (pin "C") (pinfunction "C_C") (pintype "passive"))
      (node (ref "Q40") (pin "E") (pinfunction "E_E") (pintype "passive"))
    )
    (net (code "137") (name "Net-(Q41-PadB)") (class "Default")
      (node (ref "Q41") (pin "B") (pinfunction "B_B") (pintype "passive"))
      (node (ref "Q41") (pin "C") (pinfunction "C_C") (pintype "passive"))
      (node (ref "Q43") (pin "B") (pinfunction "B_B") (pintype "passive"))
      (node (ref "R68") (pin "2") (pinfunction "2_2") (pintype "passive"))
    )
    (net (code "138") (name "Net-(Q41-PadE)") (class "Default")
      (node (ref "Q41") (pin "E") (pinfunction "E_E") (pintype "passive"))
      (node (ref "R67") (pin "1") (pinfunction "1_1") (pintype "passive"))
    )
    (net (code "139") (name "Net-(Q42-PadB)") (class "Default")
      (node (ref "Q42") (pin "B") (pinfunction "B_B") (pintype "passive"))
      (node (ref "Q42") (pin "C") (pinfunction "C_C") (pintype "passive"))
      (node (ref "Q44") (pin "B") (pinfunction "B_B") (pintype "passive"))
      (node (ref "R69") (pin "1") (pinfunction "1_1") (pintype "passive"))
    )
    (net (code "140") (name "Net-(Q42-PadE)") (class "Default")
      (node (ref "Q42") (pin "E") (pinfunction "E_E") (pintype "passive"))
      (node (ref "R70") (pin "2") (pinfunction "2_2") (pintype "passive"))
    )
    (net (code "141") (name "Net-(Q43-PadE)") (class "Default")
      (node (ref "Q43") (pin "E") (pinfunction "E_E") (pintype "passive"))
      (node (ref "R71") (pin "1") (pinfunction "1_1") (pintype "passive"))
    )
    (net (code "142") (name "Net-(Q44-PadE)") (class "Default")
      (node (ref "Q44") (pin "E") (pinfunction "E_E") (pintype "passive"))
      (node (ref "R72") (pin "2") (pinfunction "2_2") (pintype "passive"))
    )
    (net (code "143") (name "Net-(Q46-PadE)") (class "Default")
      (node (ref "Q46") (pin "E") (pinfunction "E_E") (pintype "passive"))
      (node (ref "Q48") (pin "B") (pinfunction "B_B") (pintype "passive"))
      (node (ref "R77") (pin "2") (pinfunction "2_2") (pintype "passive"))
    )
    (net (code "144") (name "Net-(Q47-PadE)") (class "Default")
      (node (ref "Q47") (pin "E") (pinfunction "E_E") (pintype "passive"))
      (node (ref "Q49") (pin "B") (pinfunction "B_B") (pintype "passive"))
      (node (ref "R77") (pin "1") (pinfunction "1_1") (pintype "passive"))
    )
    (net (code "145") (name "Net-(Q48-PadE)") (class "Default")
      (node (ref "Q48") (pin "E") (pinfunction "E_E") (pintype "passive"))
      (node (ref "Q50") (pin "B") (pinfunction "B_B") (pintype "passive"))
      (node (ref "R78") (pin "2") (pinfunction "2_2") (pintype "passive"))
    )
    (net (code "146") (name "Net-(Q49-PadE)") (class "Default")
      (node (ref "Q49") (pin "E") (pinfunction "E_E") (pintype "passive"))
      (node (ref "Q51") (pin "B") (pinfunction "B_B") (pintype "passive"))
      (node (ref "R78") (pin "1") (pinfunction "1_1") (pintype "passive"))
    )
    (net (code "147") (name "Net-(Q50-PadE)") (class "Default")
      (node (ref "Q50") (pin "E") (pinfunction "E_E") (pintype "passive"))
      (node (ref "R80") (pin "2") (pinfunction "2_2") (pintype "passive"))
    )
    (net (code "148") (name "Net-(Q51-PadE)") (class "Default")
      (node (ref "Q51") (pin "E") (pinfunction "E_E") (pintype "passive"))
      (node (ref "R81") (pin "1") (pinfunction "1_1") (pintype "passive"))
    )
    (net (code "149") (name "Net-(Q52-PadE)") (class "Default")
      (node (ref "Q52") (pin "E") (pinfunction "E_E") (pintype "passive"))
      (node (ref "R86") (pin "1") (pinfunction "1_1") (pintype "passive"))
    )
    (net (code "150") (name "Net-(Q53-PadC)") (class "Default")
      (node (ref "Q53") (pin "C") (pinfunction "C_C") (pintype "passive"))
      (node (ref "Q58") (pin "E") (pinfunction "E_E") (pintype "passive"))
      (node (ref "R92") (pin "1") (pinfunction "1_1") (pintype "passive"))
    )
    (net (code "151") (name "Net-(Q53-PadE)") (class "Default")
      (node (ref "Q53") (pin "E") (pinfunction "E_E") (pintype "passive"))
      (node (ref "R87") (pin "1") (pinfunction "1_1") (pintype "passive"))
    )
    (net (code "152") (name "Net-(Q54-PadC)") (class "Default")
      (node (ref "Q54") (pin "C") (pinfunction "C_C") (pintype "passive"))
      (node (ref "Q57") (pin "E") (pinfunction "E_E") (pintype "passive"))
      (node (ref "R91") (pin "2") (pinfunction "2_2") (pintype "passive"))
    )
    (net (code "153") (name "Net-(Q54-PadE)") (class "Default")
      (node (ref "Q54") (pin "E") (pinfunction "E_E") (pintype "passive"))
      (node (ref "R88") (pin "2") (pinfunction "2_2") (pintype "passive"))
    )
    (net (code "154") (name "Net-(Q55-PadE)") (class "Default")
      (node (ref "Q55") (pin "E") (pinfunction "E_E") (pintype "passive"))
      (node (ref "R89") (pin "2") (pinfunction "2_2") (pintype "passive"))
    )
    (net (code "155") (name "Net-(Q56-PadC)") (class "Default")
      (node (ref "Q56") (pin "C") (pinfunction "C_C") (pintype "passive"))
      (node (ref "Q60") (pin "C") (pinfunction "C_C") (pintype "passive"))
      (node (ref "Q63") (pin "B") (pinfunction "B_B") (pintype "passive"))
    )
    (net (code "156") (name "Net-(Q56-PadE)") (class "Default")
      (node (ref "Q56") (pin "E") (pinfunction "E_E") (pintype "passive"))
      (node (ref "Q57") (pin "C") (pinfunction "C_C") (pintype "passive"))
    )
    (net (code "157") (name "Net-(Q58-PadC)") (class "Default")
      (node (ref "Q58") (pin "C") (pinfunction "C_C") (pintype "passive"))
      (node (ref "Q59") (pin "E") (pinfunction "E_E") (pintype "passive"))
    )
    (net (code "158") (name "Net-(Q59-PadC)") (class "Default")
      (node (ref "Q59") (pin "C") (pinfunction "C_C") (pintype "passive"))
      (node (ref "Q61") (pin "C") (pinfunction "C_C") (pintype "passive"))
      (node (ref "Q64") (pin "B") (pinfunction "B_B") (pintype "passive"))
    )
    (net (code "159") (name "Net-(Q60-PadB)") (class "Default")
      (node (ref "Q60") (pin "B") (pinfunction "B_B") (pintype "passive"))
      (node (ref "Q62") (pin "B") (pinfunction "B_B") (pintype "passive"))
      (node (ref "Q62") (pin "C") (pinfunction "C_C") (pintype "passive"))
      (node (ref "Q63") (pin "E") (pinfunction "E_E") (pintype "passive"))
    )
    (net (code "160") (name "Net-(Q60-PadE)") (class "Default")
      (node (ref "Q60") (pin "E") (pinfunction "E_E") (pintype "passive"))
      (node (ref "R90") (pin "1") (pinfunction "1_1") (pintype "passive"))
    )
    (net (code "161") (name "Net-(Q61-PadB)") (class "Default")
      (node (ref "Q61") (pin "B") (pinfunction "B_B") (pintype "passive"))
      (node (ref "Q64") (pin "E") (pinfunction "E_E") (pintype "passive"))
      (node (ref "Q65") (pin "B") (pinfunction "B_B") (pintype "passive"))
      (node (ref "Q65") (pin "C") (pinfunction "C_C") (pintype "passive"))
    )
    (net (code "162") (name "Net-(Q61-PadE)") (class "Default")
      (node (ref "Q61") (pin "E") (pinfunction "E_E") (pintype "passive"))
      (node (ref "R93") (pin "2") (pinfunction "2_2") (pintype "passive"))
    )
    (net (code "163") (name "Net-(Q63-PadC)") (class "Default")
      (node (ref "Q63") (pin "C") (pinfunction "C_C") (pintype "passive"))
      (node (ref "Q66") (pin "E") (pinfunction "E_E") (pintype "passive"))
    )
    (net (code "164") (name "Net-(Q64-PadC)") (class "Default")
      (node (ref "Q64") (pin "C") (pinfunction "C_C") (pintype "passive"))
      (node (ref "Q67") (pin "E") (pinfunction "E_E") (pintype "passive"))
    )
    (net (code "165") (name "Net-(Q68-PadB)") (class "Default")
      (node (ref "Q68") (pin "B") (pinfunction "B_B") (pintype "passive"))
      (node (ref "Q68") (pin "C") (pinfunction "C_C") (pintype "passive"))
      (node (ref "Q70") (pin "B") (pinfunction "B_B") (pintype "passive"))
      (node (ref "R100") (pin "2") (pinfunction "2_2") (pintype "passive"))
    )
    (net (code "166") (name "Net-(Q68-PadE)") (class "Default")
      (node (ref "Q68") (pin "E") (pinfunction "E_E") (pintype "passive"))
      (node (ref "R99") (pin "1") (pinfunction "1_1") (pintype "passive"))
    )
    (net (code "167") (name "Net-(Q69-PadB)") (class "Default")
      (node (ref "Q69") (pin "B") (pinfunction "B_B") (pintype "passive"))
      (node (ref "Q69") (pin "C") (pinfunction "C_C") (pintype "passive"))
      (node (ref "Q71") (pin "B") (pinfunction "B_B") (pintype "passive"))
      (node (ref "R101") (pin "1") (pinfunction "1_1") (pintype "passive"))
    )
    (net (code "168") (name "Net-(Q69-PadE)") (class "Default")
      (node (ref "Q69") (pin "E") (pinfunction "E_E") (pintype "passive"))
      (node (ref "R102") (pin "2") (pinfunction "2_2") (pintype "passive"))
    )
    (net (code "169") (name "Net-(Q70-PadE)") (class "Default")
      (node (ref "Q70") (pin "E") (pinfunction "E_E") (pintype "passive"))
      (node (ref "R103") (pin "1") (pinfunction "1_1") (pintype "passive"))
    )
    (net (code "170") (name "Net-(Q71-PadE)") (class "Default")
      (node (ref "Q71") (pin "E") (pinfunction "E_E") (pintype "passive"))
      (node (ref "R104") (pin "2") (pinfunction "2_2") (pintype "passive"))
    )
    (net (code "171") (name "Net-(Q73-PadE)") (class "Default")
      (node (ref "Q73") (pin "E") (pinfunction "E_E") (pintype "passive"))
      (node (ref "Q75") (pin "B") (pinfunction "B_B") (pintype "passive"))
      (node (ref "R109") (pin "2") (pinfunction "2_2") (pintype "passive"))
    )
    (net (code "172") (name "Net-(Q74-PadE)") (class "Default")
      (node (ref "Q74") (pin "E") (pinfunction "E_E") (pintype "passive"))
      (node (ref "Q76") (pin "B") (pinfunction "B_B") (pintype "passive"))
      (node (ref "R109") (pin "1") (pinfunction "1_1") (pintype "passive"))
    )
    (net (code "173") (name "Net-(Q75-PadE)") (class "Default")
      (node (ref "Q75") (pin "E") (pinfunction "E_E") (pintype "passive"))
      (node (ref "Q77") (pin "B") (pinfunction "B_B") (pintype "passive"))
      (node (ref "R110") (pin "2") (pinfunction "2_2") (pintype "passive"))
    )
    (net (code "174") (name "Net-(Q76-PadE)") (class "Default")
      (node (ref "Q76") (pin "E") (pinfunction "E_E") (pintype "passive"))
      (node (ref "Q78") (pin "B") (pinfunction "B_B") (pintype "passive"))
      (node (ref "R110") (pin "1") (pinfunction "1_1") (pintype "passive"))
    )
    (net (code "175") (name "Net-(Q77-PadE)") (class "Default")
      (node (ref "Q77") (pin "E") (pinfunction "E_E") (pintype "passive"))
      (node (ref "R112") (pin "2") (pinfunction "2_2") (pintype "passive"))
    )
    (net (code "176") (name "Net-(Q78-PadE)") (class "Default")
      (node (ref "Q78") (pin "E") (pinfunction "E_E") (pintype "passive"))
      (node (ref "R113") (pin "1") (pinfunction "1_1") (pintype "passive"))
    )
    (net (code "177") (name "Net-(Q79-PadC)") (class "Default")
      (node (ref "Q79") (pin "C") (pinfunction "C_C") (pintype "passive"))
      (node (ref "Q81") (pin "B") (pinfunction "B_B") (pintype "passive"))
      (node (ref "Q81") (pin "C") (pinfunction "C_C") (pintype "passive"))
      (node (ref "Q83") (pin "B") (pinfunction "B_B") (pintype "passive"))
    )
    (net (code "178") (name "Net-(Q79-PadE)") (class "Default")
      (node (ref "Q79") (pin "E") (pinfunction "E_E") (pintype "passive"))
      (node (ref "R117") (pin "1") (pinfunction "1_1") (pintype "passive"))
    )
    (net (code "179") (name "Net-(Q80-PadC)") (class "Default")
      (node (ref "Q80") (pin "C") (pinfunction "C_C") (pintype "passive"))
      (node (ref "Q82") (pin "B") (pinfunction "B_B") (pintype "passive"))
      (node (ref "Q82") (pin "C") (pinfunction "C_C") (pintype "passive"))
      (node (ref "Q84") (pin "B") (pinfunction "B_B") (pintype "passive"))
    )
    (net (code "180") (name "Net-(Q80-PadE)") (class "Default")
      (node (ref "Q80") (pin "E") (pinfunction "E_E") (pintype "passive"))
      (node (ref "R118") (pin "2") (pinfunction "2_2") (pintype "passive"))
    )
    (net (code "181") (name "Net-(Q83-PadE)") (class "Default")
      (node (ref "Q83") (pin "E") (pinfunction "E_E") (pintype "passive"))
      (node (ref "R119") (pin "2") (pinfunction "2_2") (pintype "passive"))
    )
    (net (code "182") (name "Net-(Q84-PadE)") (class "Default")
      (node (ref "Q84") (pin "E") (pinfunction "E_E") (pintype "passive"))
      (node (ref "R122") (pin "1") (pinfunction "1_1") (pintype "passive"))
    )
    (net (code "183") (name "Net-(Q85-PadB)") (class "Default")
      (node (ref "Q85") (pin "B") (pinfunction "B_B") (pintype "passive"))
      (node (ref "R123") (pin "2") (pinfunction "2_2") (pintype "passive"))
    )
    (net (code "184") (name "Net-(Q85-PadE)") (class "Default")
      (node (ref "Q85") (pin "E") (pinfunction "E_E") (pintype "passive"))
      (node (ref "R120") (pin "2") (pinfunction "2_2") (pintype "passive"))
    )
    (net (code "185") (name "Net-(Q86-PadB)") (class "Default")
      (node (ref "Q86") (pin "B") (pinfunction "B_B") (pintype "passive"))
      (node (ref "R124") (pin "2") (pinfunction "2_2") (pintype "passive"))
    )
    (net (code "186") (name "Net-(Q86-PadE)") (class "Default")
      (node (ref "Q86") (pin "E") (pinfunction "E_E") (pintype "passive"))
      (node (ref "R121") (pin "1") (pinfunction "1_1") (pintype "passive"))
    )
    (net (code "187") (name "Net-(Q87-PadE)") (class "Default")
      (node (ref "Q87") (pin "E") (pinfunction "E_E") (pintype "passive"))
      (node (ref "Q89") (pin "B") (pinfunction "B_B") (pintype "passive"))
    )
    (net (code "188") (name "Net-(Q88-PadE)") (class "Default")
      (node (ref "Q88") (pin "E") (pinfunction "E_E") (pintype "passive"))
      (node (ref "Q90") (pin "B") (pinfunction "B_B") (pintype "passive"))
    )
    (net (code "189") (name "Net-(Q91-PadS)") (class "Default")
      (node (ref "Q91") (pin "S") (pinfunction "S_S") (pintype "passive"))
      (node (ref "R125") (pin "2") (pinfunction "2_2") (pintype "passive"))
    )
    (net (code "190") (name "Net-(Q92-PadS)") (class "Default")
      (node (ref "Q92") (pin "S") (pinfunction "S_S") (pintype "passive"))
      (node (ref "R126") (pin "2") (pinfunction "2_2") (pintype "passive"))
    )
    (net (code "191") (name "Net-(Q97-G)") (class "Default")
      (node (ref "Q97") (pin "4") (pinfunction "G_4") (pintype "passive"))
      (node (ref "U$2") (pin "2") (pinfunction "2_TG2_2") (pintype "bidirectional"))
    )
    (net (code "192") (name "Net-(Q98-G)") (class "Default")
      (node (ref "Q98") (pin "4") (pinfunction "G_4") (pintype "passive"))
      (node (ref "U$2") (pin "11") (pinfunction "7_TG1_11") (pintype "bidirectional"))
    )
    (net (code "193") (name "Net-(Q99-G)") (class "Default")
      (node (ref "Q99") (pin "4") (pinfunction "G_4") (pintype "passive"))
      (node (ref "U$2") (pin "5") (pinfunction "3_BG2_5") (pintype "bidirectional"))
    )
    (net (code "194") (name "Net-(Q100-G)") (class "Default")
      (node (ref "Q100") (pin "4") (pinfunction "G_4") (pintype "passive"))
      (node (ref "U$2") (pin "6") (pinfunction "4_BG1_6") (pintype "bidirectional"))
    )
    (net (code "195") (name "Net-(Q105-G)") (class "Default")
      (node (ref "Q105") (pin "4") (pinfunction "G_4") (pintype "passive"))
      (node (ref "U$4") (pin "2") (pinfunction "2_TG2_2") (pintype "bidirectional"))
    )
    (net (code "196") (name "Net-(Q106-G)") (class "Default")
      (node (ref "Q106") (pin "4") (pinfunction "G_4") (pintype "passive"))
      (node (ref "U$4") (pin "11") (pinfunction "7_TG1_11") (pintype "bidirectional"))
    )
    (net (code "197") (name "Net-(Q107-G)") (class "Default")
      (node (ref "Q107") (pin "4") (pinfunction "G_4") (pintype "passive"))
      (node (ref "U$4") (pin "5") (pinfunction "3_BG2_5") (pintype "bidirectional"))
    )
    (net (code "198") (name "Net-(Q108-G)") (class "Default")
      (node (ref "Q108") (pin "4") (pinfunction "G_4") (pintype "passive"))
      (node (ref "U$4") (pin "6") (pinfunction "4_BG1_6") (pintype "bidirectional"))
    )
    (net (code "199") (name "Net-(R59-Pad1)") (class "Default")
      (node (ref "R59") (pin "1") (pinfunction "1_1") (pintype "passive"))
      (node (ref "R60") (pin "2") (pinfunction "2_2") (pintype "passive"))
      (node (ref "R63") (pin "2") (pinfunction "2_2") (pintype "passive"))
      (node (ref "R66") (pin "1") (pinfunction "1_1") (pintype "passive"))
    )
    (net (code "200") (name "Net-(R74-A)") (class "Default")
      (node (ref "C18") (pin "2") (pinfunction "2_2") (pintype "passive"))
      (node (ref "C20") (pin "1") (pinfunction "1_1") (pintype "passive"))
      (node (ref "Q40") (pin "C") (pinfunction "C_C") (pintype "passive"))
      (node (ref "Q44") (pin "C") (pinfunction "C_C") (pintype "passive"))
      (node (ref "Q45") (pin "E") (pinfunction "E_E") (pintype "passive"))
      (node (ref "Q47") (pin "B") (pinfunction "B_B") (pintype "passive"))
      (node (ref "R74") (pin "1") (pinfunction "A_1") (pintype "passive"))
      (node (ref "R74") (pin "2") (pinfunction "S_2") (pintype "passive"))
      (node (ref "R76") (pin "2") (pinfunction "2_2") (pintype "passive"))
    )
    (net (code "201") (name "Net-(R74-E)") (class "Default")
      (node (ref "Q45") (pin "B") (pinfunction "B_B") (pintype "passive"))
      (node (ref "R73") (pin "1") (pinfunction "1_1") (pintype "passive"))
      (node (ref "R74") (pin "3") (pinfunction "E_3") (pintype "passive"))
    )
    (net (code "202") (name "Net-(R91-Pad1)") (class "Default")
      (node (ref "R91") (pin "1") (pinfunction "1_1") (pintype "passive"))
      (node (ref "R92") (pin "2") (pinfunction "2_2") (pintype "passive"))
      (node (ref "R95") (pin "2") (pinfunction "2_2") (pintype "passive"))
      (node (ref "R98") (pin "1") (pinfunction "1_1") (pintype "passive"))
    )
    (net (code "203") (name "Net-(R106-A)") (class "Default")
      (node (ref "C28") (pin "2") (pinfunction "2_2") (pintype "passive"))
      (node (ref "C30") (pin "1") (pinfunction "1_1") (pintype "passive"))
      (node (ref "Q67") (pin "C") (pinfunction "C_C") (pintype "passive"))
      (node (ref "Q71") (pin "C") (pinfunction "C_C") (pintype "passive"))
      (node (ref "Q72") (pin "E") (pinfunction "E_E") (pintype "passive"))
      (node (ref "Q74") (pin "B") (pinfunction "B_B") (pintype "passive"))
      (node (ref "R106") (pin "1") (pinfunction "A_1") (pintype "passive"))
      (node (ref "R106") (pin "2") (pinfunction "S_2") (pintype "passive"))
      (node (ref "R108") (pin "2") (pinfunction "2_2") (pintype "passive"))
    )
    (net (code "204") (name "Net-(R106-E)") (class "Default")
      (node (ref "Q72") (pin "B") (pinfunction "B_B") (pintype "passive"))
      (node (ref "R105") (pin "1") (pinfunction "1_1") (pintype "passive"))
      (node (ref "R106") (pin "3") (pinfunction "E_3") (pintype "passive"))
    )
    (net (code "205") (name "Net-(U$5-BUF)") (class "Default")
      (node (ref "R138") (pin "2") (pinfunction "2_2") (pintype "passive"))
      (node (ref "U$5") (pin "8") (pinfunction "BUF_8") (pintype "bidirectional"))
    )
    (net (code "206") (name "Net-(U$5-EN)") (class "Default")
      (node (ref "SJ1") (pin "1") (pinfunction "1_1") (pintype "passive"))
      (node (ref "U$5") (pin "2") (pinfunction "EN_2") (pintype "bidirectional"))
    )
    (net (code "207") (name "Net-(U$5-FB+)") (class "Default")
      (node (ref "C71") (pin "2") (pinfunction "2_2") (pintype "passive"))
      (node (ref "R136") (pin "1") (pinfunction "1_1") (pintype "passive"))
      (node (ref "R137") (pin "2") (pinfunction "2_2") (pintype "passive"))
      (node (ref "U$5") (pin "9") (pinfunction "FB+_9") (pintype "bidirectional"))
    )
    (net (code "208") (name "Net-(U$5-FB-)") (class "Default")
      (node (ref "C72") (pin "1") (pinfunction "1_1") (pintype "passive"))
      (node (ref "R138") (pin "1") (pinfunction "1_1") (pintype "passive"))
      (node (ref "R139") (pin "2") (pinfunction "2_2") (pintype "passive"))
      (node (ref "U$5") (pin "7") (pinfunction "FB-_7") (pintype "bidirectional"))
    )
    (net (code "209") (name "Net-(U$5-NR{slash}SS)") (class "Default")
      (node (ref "C2") (pin "1") (pinfunction "1_1") (pintype "passive"))
      (node (ref "U$5") (pin "3") (pinfunction "NR/SS_3") (pintype "bidirectional"))
    )
    (net (code "210") (name "OUT+") (class "Default")
      (node (ref "C1") (pin "1") (pinfunction "1_1") (pintype "passive"))
      (node (ref "PAD1") (pin "P$1") (pinfunction "P$1_P$1") (pintype "bidirectional"))
      (node (ref "R66") (pin "2") (pinfunction "2_2") (pintype "passive"))
      (node (ref "R80") (pin "1") (pinfunction "1_1") (pintype "passive"))
      (node (ref "R81") (pin "2") (pinfunction "2_2") (pintype "passive"))
      (node (ref "R82") (pin "1") (pinfunction "1_1") (pintype "passive"))
    )
    (net (code "211") (name "OUT-") (class "Default")
      (node (ref "PAD2") (pin "P$1") (pinfunction "P$1_P$1") (pintype "bidirectional"))
      (node (ref "R112") (pin "1") (pinfunction "1_1") (pintype "passive"))
      (node (ref "R113") (pin "2") (pinfunction "2_2") (pintype "passive"))
      (node (ref "R114") (pin "1") (pinfunction "1_1") (pintype "passive"))
      (node (ref "R133") (pin "2") (pinfunction "2_2") (pintype "passive"))
      (node (ref "R98") (pin "2") (pinfunction "2_2") (pintype "passive"))
    )
    (net (code "212") (name "UOUT+") (class "Default")
      (node (ref "Q10") (pin "B") (pinfunction "B_B") (pintype "passive"))
      (node (ref "Q5") (pin "6") (pinfunction "C_6") (pintype "passive"))
      (node (ref "Q6") (pin "6") (pinfunction "C_6") (pintype "passive"))
      (node (ref "Q9") (pin "B") (pinfunction "B_B") (pintype "passive"))
      (node (ref "R11") (pin "2") (pinfunction "2_2") (pintype "passive"))
      (node (ref "R21") (pin "2") (pinfunction "2_2") (pintype "passive"))
    )
    (net (code "213") (name "UOUT-") (class "Default")
      (node (ref "Q17") (pin "B") (pinfunction "B_B") (pintype "passive"))
      (node (ref "Q18") (pin "B") (pinfunction "B_B") (pintype "passive"))
      (node (ref "Q5") (pin "4") (pinfunction "C_4") (pintype "passive"))
      (node (ref "Q6") (pin "4") (pinfunction "C_4") (pintype "passive"))
      (node (ref "R20") (pin "2") (pinfunction "2_2") (pintype "passive"))
      (node (ref "R36") (pin "2") (pinfunction "2_2") (pintype "passive"))
    )
    (net (code "214") (name "UV+") (class "Default")
      (node (ref "C37") (pin "+") (pinfunction "+_+") (pintype "passive"))
      (node (ref "C42") (pin "2") (pinfunction "2_2") (pintype "passive"))
      (node (ref "C57") (pin "1") (pinfunction "1_1") (pintype "passive"))
      (node (ref "C58") (pin "2") (pinfunction "2_2") (pintype "passive"))
      (node (ref "D15") (pin "C") (pinfunction "C_C") (pintype "passive"))
      (node (ref "LED15") (pin "A") (pinfunction "A_A") (pintype "passive"))
      (node (ref "Q87") (pin "C") (pinfunction "C_C") (pintype "passive"))
      (node (ref "Q89") (pin "C") (pinfunction "C_C") (pintype "passive"))
      (node (ref "Q97") (pin "5") (pinfunction "D_5") (pintype "passive"))
      (node (ref "Q97") (pin "6") (pinfunction "D_6") (pintype "passive"))
      (node (ref "Q97") (pin "7") (pinfunction "D_7") (pintype "passive"))
      (node (ref "Q97") (pin "8") (pinfunction "D_8") (pintype "passive"))
      (node (ref "Q97") (pin "TH") (pinfunction "D_TH") (pintype "passive"))
      (node (ref "Q98") (pin "5") (pinfunction "D_5") (pintype "passive"))
      (node (ref "Q98") (pin "6") (pinfunction "D_6") (pintype "passive"))
      (node (ref "Q98") (pin "7") (pinfunction "D_7") (pintype "passive"))
      (node (ref "Q98") (pin "8") (pinfunction "D_8") (pintype "passive"))
      (node (ref "Q98") (pin "TH") (pinfunction "D_TH") (pintype "passive"))
      (node (ref "R115") (pin "1") (pinfunction "1_1") (pintype "passive"))
      (node (ref "R119") (pin "1") (pinfunction "1_1") (pintype "passive"))
      (node (ref "U$2") (pin "9") (pinfunction "6_OUTP_9") (pintype "bidirectional"))
    )
    (net (code "215") (name "UV-") (class "Default")
      (node (ref "C38") (pin "-") (pinfunction "-_-") (pintype "passive"))
      (node (ref "C39") (pin "1") (pinfunction "1_1") (pintype "passive"))
      (node (ref "C59") (pin "2") (pinfunction "2_2") (pintype "passive"))
      (node (ref "C60") (pin "1") (pinfunction "1_1") (pintype "passive"))
      (node (ref "D16") (pin "A") (pinfunction "A_A") (pintype "passive"))
      (node (ref "LED16") (pin "C") (pinfunction "C_C") (pintype "passive"))
      (node (ref "Q107") (pin "1") (pinfunction "S_1") (pintype "passive"))
      (node (ref "Q107") (pin "2") (pinfunction "S_2") (pintype "passive"))
      (node (ref "Q107") (pin "3") (pinfunction "S_3") (pintype "passive"))
      (node (ref "Q108") (pin "1") (pinfunction "S_1") (pintype "passive"))
      (node (ref "Q108") (pin "2") (pinfunction "S_2") (pintype "passive"))
      (node (ref "Q108") (pin "3") (pinfunction "S_3") (pintype "passive"))
      (node (ref "Q88") (pin "C") (pinfunction "C_C") (pintype "passive"))
      (node (ref "Q90") (pin "C") (pinfunction "C_C") (pintype "passive"))
      (node (ref "R116") (pin "2") (pinfunction "2_2") (pintype "passive"))
      (node (ref "R122") (pin "2") (pinfunction "2_2") (pintype "passive"))
      (node (ref "U$4") (pin "7") (pinfunction "5_OUTN_7") (pintype "bidirectional"))
      (node (ref "U$4") (pin "EXP") (pinfunction "5_OUTN_EXP") (pintype "bidirectional"))
    )
    (net (code "216") (name "V+") (class "Default")
      (node (ref "C11") (pin "1") (pinfunction "1_1") (pintype "passive"))
      (node (ref "C25") (pin "+") (pinfunction "+_+") (pintype "passive"))
      (node (ref "C35") (pin "+") (pinfunction "+_+") (pintype "passive"))
      (node (ref "C45") (pin "2") (pinfunction "2_2") (pintype "passive"))
      (node (ref "C5") (pin "+") (pinfunction "+_+") (pintype "passive"))
      (node (ref "C53") (pin "1") (pinfunction "1_1") (pintype "passive"))
      (node (ref "C55") (pin "2") (pinfunction "2_2") (pintype "passive"))
      (node (ref "C66") (pin "1") (pinfunction "1_1") (pintype "passive"))
      (node (ref "C68") (pin "1") (pinfunction "1_1") (pintype "passive"))
      (node (ref "C7") (pin "+") (pinfunction "+_+") (pintype "passive"))
      (node (ref "C74") (pin "1") (pinfunction "1_1") (pintype "passive"))
      (node (ref "C9") (pin "1") (pinfunction "1_1") (pintype "passive"))
      (node (ref "D1") (pin "A") (pinfunction "A_A") (pintype "passive"))
      (node (ref "D15") (pin "A") (pinfunction "A_A") (pintype "passive"))
      (node (ref "D7") (pin "A") (pinfunction "A_A") (pintype "passive"))
      (node (ref "IC6") (pin "7") (pinfunction "V+_7") (pintype "power_in"))
      (node (ref "LED1") (pin "A") (pinfunction "A_A") (pintype "passive"))
      (node (ref "LED3") (pin "A") (pinfunction "A_A") (pintype "passive"))
      (node (ref "LED5") (pin "A") (pinfunction "A_A") (pintype "passive"))
      (node (ref "LED7") (pin "A") (pinfunction "A_A") (pintype "passive"))
      (node (ref "Q13") (pin "C") (pinfunction "C_C") (pintype "passive"))
      (node (ref "Q15") (pin "C") (pinfunction "C_C") (pintype "passive"))
      (node (ref "Q17") (pin "C") (pinfunction "C_C") (pintype "passive"))
      (node (ref "Q21") (pin "C") (pinfunction "C_C") (pintype "passive"))
      (node (ref "Q23") (pin "C") (pinfunction "C_C") (pintype "passive"))
      (node (ref "Q46") (pin "C") (pinfunction "C_C") (pintype "passive"))
      (node (ref "Q48") (pin "C") (pinfunction "C_C") (pintype "passive"))
      (node (ref "Q50") (pin "C") (pinfunction "C_C") (pintype "passive"))
      (node (ref "Q73") (pin "C") (pinfunction "C_C") (pintype "passive"))
      (node (ref "Q75") (pin "C") (pinfunction "C_C") (pintype "passive"))
      (node (ref "Q77") (pin "C") (pinfunction "C_C") (pintype "passive"))
      (node (ref "Q89") (pin "E") (pinfunction "E_E") (pintype "passive"))
      (node (ref "Q9") (pin "C") (pinfunction "C_C") (pintype "passive"))
      (node (ref "Q91") (pin "D") (pinfunction "D_D") (pintype "passive"))
      (node (ref "R103") (pin "2") (pinfunction "2_2") (pintype "passive"))
      (node (ref "R12") (pin "2") (pinfunction "2_2") (pintype "passive"))
      (node (ref "R127") (pin "2") (pinfunction "2_2") (pintype "passive"))
      (node (ref "R131") (pin "2") (pinfunction "2_2") (pintype "passive"))
      (node (ref "R141") (pin "2") (pinfunction "2_2") (pintype "passive"))
      (node (ref "R18") (pin "2") (pinfunction "2_2") (pintype "passive"))
      (node (ref "R23") (pin "2") (pinfunction "2_2") (pintype "passive"))
      (node (ref "R38") (pin "2") (pinfunction "2_2") (pintype "passive"))
      (node (ref "R5") (pin "2") (pinfunction "2_2") (pintype "passive"))
      (node (ref "R54") (pin "2") (pinfunction "2_2") (pintype "passive"))
      (node (ref "R58") (pin "2") (pinfunction "2_2") (pintype "passive"))
      (node (ref "R62") (pin "2") (pinfunction "2_2") (pintype "passive"))
      (node (ref "R67") (pin "2") (pinfunction "2_2") (pintype "passive"))
      (node (ref "R71") (pin "2") (pinfunction "2_2") (pintype "passive"))
      (node (ref "R86") (pin "2") (pinfunction "2_2") (pintype "passive"))
      (node (ref "R90") (pin "2") (pinfunction "2_2") (pintype "passive"))
      (node (ref "R94") (pin "2") (pinfunction "2_2") (pintype "passive"))
      (node (ref "R99") (pin "2") (pinfunction "2_2") (pintype "passive"))
      (node (ref "SJ1") (pin "2") (pinfunction "2_2") (pintype "passive"))
      (node (ref "U$5") (pin "1") (pinfunction "IN+_1") (pintype "bidirectional"))
    )
    (net (code "217") (name "V-") (class "Default")
      (node (ref "C10") (pin "2") (pinfunction "2_2") (pintype "passive"))
      (node (ref "C12") (pin "2") (pinfunction "2_2") (pintype "passive"))
      (node (ref "C26") (pin "-") (pinfunction "-_-") (pintype "passive"))
      (node (ref "C36") (pin "-") (pinfunction "-_-") (pintype "passive"))
      (node (ref "C46") (pin "1") (pinfunction "1_1") (pintype "passive"))
      (node (ref "C54") (pin "2") (pinfunction "2_2") (pintype "passive"))
      (node (ref "C56") (pin "1") (pinfunction "1_1") (pintype "passive"))
      (node (ref "C6") (pin "-") (pinfunction "-_-") (pintype "passive"))
      (node (ref "C65") (pin "1") (pinfunction "1_1") (pintype "passive"))
      (node (ref "C67") (pin "1") (pinfunction "1_1") (pintype "passive"))
      (node (ref "C75") (pin "2") (pinfunction "2_2") (pintype "passive"))
      (node (ref "C8") (pin "-") (pinfunction "-_-") (pintype "passive"))
      (node (ref "D10") (pin "C") (pinfunction "C_C") (pintype "passive"))
      (node (ref "D16") (pin "C") (pinfunction "C_C") (pintype "passive"))
      (node (ref "D4") (pin "C") (pinfunction "C_C") (pintype "passive"))
      (node (ref "IC5") (pin "4") (pinfunction "V-_4") (pintype "power_in"))
      (node (ref "LED2") (pin "C") (pinfunction "C_C") (pintype "passive"))
      (node (ref "LED4") (pin "C") (pinfunction "C_C") (pintype "passive"))
      (node (ref "LED6") (pin "C") (pinfunction "C_C") (pintype "passive"))
      (node (ref "LED8") (pin "C") (pinfunction "C_C") (pintype "passive"))
      (node (ref "Q10") (pin "C") (pinfunction "C_C") (pintype "passive"))
      (node (ref "Q14") (pin "C") (pinfunction "C_C") (pintype "passive"))
      (node (ref "Q16") (pin "C") (pinfunction "C_C") (pintype "passive"))
      (node (ref "Q18") (pin "C") (pinfunction "C_C") (pintype "passive"))
      (node (ref "Q22") (pin "C") (pinfunction "C_C") (pintype "passive"))
      (node (ref "Q24") (pin "C") (pinfunction "C_C") (pintype "passive"))
      (node (ref "Q47") (pin "C") (pinfunction "C_C") (pintype "passive"))
      (node (ref "Q49") (pin "C") (pinfunction "C_C") (pintype "passive"))
      (node (ref "Q51") (pin "C") (pinfunction "C_C") (pintype "passive"))
      (node (ref "Q74") (pin "C") (pinfunction "C_C") (pintype "passive"))
      (node (ref "Q76") (pin "C") (pinfunction "C_C") (pintype "passive"))
      (node (ref "Q78") (pin "C") (pinfunction "C_C") (pintype "passive"))
      (node (ref "Q90") (pin "E") (pinfunction "E_E") (pintype "passive"))
      (node (ref "Q92") (pin "G") (pinfunction "G_G") (pintype "passive"))
      (node (ref "R102") (pin "1") (pinfunction "1_1") (pintype "passive"))
      (node (ref "R104") (pin "1") (pinfunction "1_1") (pintype "passive"))
      (node (ref "R126") (pin "1") (pinfunction "1_1") (pintype "passive"))
      (node (ref "R13") (pin "1") (pinfunction "1_1") (pintype "passive"))
      (node (ref "R130") (pin "1") (pinfunction "1_1") (pintype "passive"))
      (node (ref "R132") (pin "1") (pinfunction "1_1") (pintype "passive"))
      (node (ref "R140") (pin "2") (pinfunction "2_2") (pintype "passive"))
      (node (ref "R19") (pin "1") (pinfunction "1_1") (pintype "passive"))
      (node (ref "R26") (pin "1") (pinfunction "1_1") (pintype "passive"))
      (node (ref "R41") (pin "1") (pinfunction "1_1") (pintype "passive"))
      (node (ref "R57") (pin "1") (pinfunction "1_1") (pintype "passive"))
      (node (ref "R61") (pin "1") (pinfunction "1_1") (pintype "passive"))
      (node (ref "R64") (pin "1") (pinfunction "1_1") (pintype "passive"))
      (node (ref "R7") (pin "1") (pinfunction "1_1") (pintype "passive"))
      (node (ref "R70") (pin "1") (pinfunction "1_1") (pintype "passive"))
      (node (ref "R72") (pin "1") (pinfunction "1_1") (pintype "passive"))
      (node (ref "R89") (pin "1") (pinfunction "1_1") (pintype "passive"))
      (node (ref "R93") (pin "1") (pinfunction "1_1") (pintype "passive"))
      (node (ref "R96") (pin "1") (pinfunction "1_1") (pintype "passive"))
      (node (ref "U$5") (pin "5") (pinfunction "IN-_5") (pintype "bidirectional"))
    )
    (net (code "218") (name "unconnected-(H1-PadP$1)") (class "Default")
      (node (ref "H1") (pin "P$1") (pinfunction "P$1_P$1") (pintype "bidirectional"))
    )
    (net (code "219") (name "unconnected-(H2-PadP$1)") (class "Default")
      (node (ref "H2") (pin "P$1") (pinfunction "P$1_P$1") (pintype "bidirectional"))
    )
    (net (code "220") (name "unconnected-(H3-PadP$1)") (class "Default")
      (node (ref "H3") (pin "P$1") (pinfunction "P$1_P$1") (pintype "bidirectional"))
    )
    (net (code "221") (name "unconnected-(H4-PadP$1)") (class "Default")
      (node (ref "H4") (pin "P$1") (pinfunction "P$1_P$1") (pintype "bidirectional"))
    )
    (net (code "222") (name "unconnected-(H5-PadP$1)") (class "Default")
      (node (ref "H5") (pin "P$1") (pinfunction "P$1_P$1") (pintype "bidirectional"))
    )
    (net (code "223") (name "unconnected-(H6-PadP$1)") (class "Default")
      (node (ref "H6") (pin "P$1") (pinfunction "P$1_P$1") (pintype "bidirectional"))
    )
    (net (code "224") (name "unconnected-(H7-PadP$1)") (class "Default")
      (node (ref "H7") (pin "P$1") (pinfunction "P$1_P$1") (pintype "bidirectional"))
    )
    (net (code "225") (name "unconnected-(H8-PadP$1)") (class "Default")
      (node (ref "H8") (pin "P$1") (pinfunction "P$1_P$1") (pintype "bidirectional"))
    )
    (net (code "226") (name "unconnected-(IC1-CMP1-Pad1)") (class "Default")
      (node (ref "IC1") (pin "1") (pinfunction "CMP1_1") (pintype "passive"))
    )
    (net (code "227") (name "unconnected-(IC2-CMP1-Pad1)") (class "Default")
      (node (ref "IC2") (pin "1") (pinfunction "CMP1_1") (pintype "passive"))
    )
    (net (code "228") (name "unconnected-(IC3-CMP1-Pad1)") (class "Default")
      (node (ref "IC3") (pin "1") (pinfunction "CMP1_1") (pintype "passive"))
    )
    (net (code "229") (name "unconnected-(IC3-CMP2-Pad8)") (class "Default")
      (node (ref "IC3") (pin "8") (pinfunction "CMP2_8") (pintype "passive"))
    )
    (net (code "230") (name "unconnected-(IC4-CMP1-Pad1)") (class "Default")
      (node (ref "IC4") (pin "1") (pinfunction "CMP1_1") (pintype "passive"))
    )
    (net (code "231") (name "unconnected-(IC4-CMP2-Pad8)") (class "Default")
      (node (ref "IC4") (pin "8") (pinfunction "CMP2_8") (pintype "passive"))
    )
    (net (code "232") (name "unconnected-(IC5-CMP1-Pad1)") (class "Default")
      (node (ref "IC5") (pin "1") (pinfunction "CMP1_1") (pintype "passive"))
    )
    (net (code "233") (name "unconnected-(IC5-CMP2-Pad8)") (class "Default")
      (node (ref "IC5") (pin "8") (pinfunction "CMP2_8") (pintype "passive"))
    )
    (net (code "234") (name "unconnected-(IC6-CMP1-Pad1)") (class "Default")
      (node (ref "IC6") (pin "1") (pinfunction "CMP1_1") (pintype "passive"))
    )
    (net (code "235") (name "unconnected-(IC6-CMP2-Pad8)") (class "Default")
      (node (ref "IC6") (pin "8") (pinfunction "CMP2_8") (pintype "passive"))
    )
  )
)
